# power-board.net
KiCad netlist of a schematic drawn in EAGLE
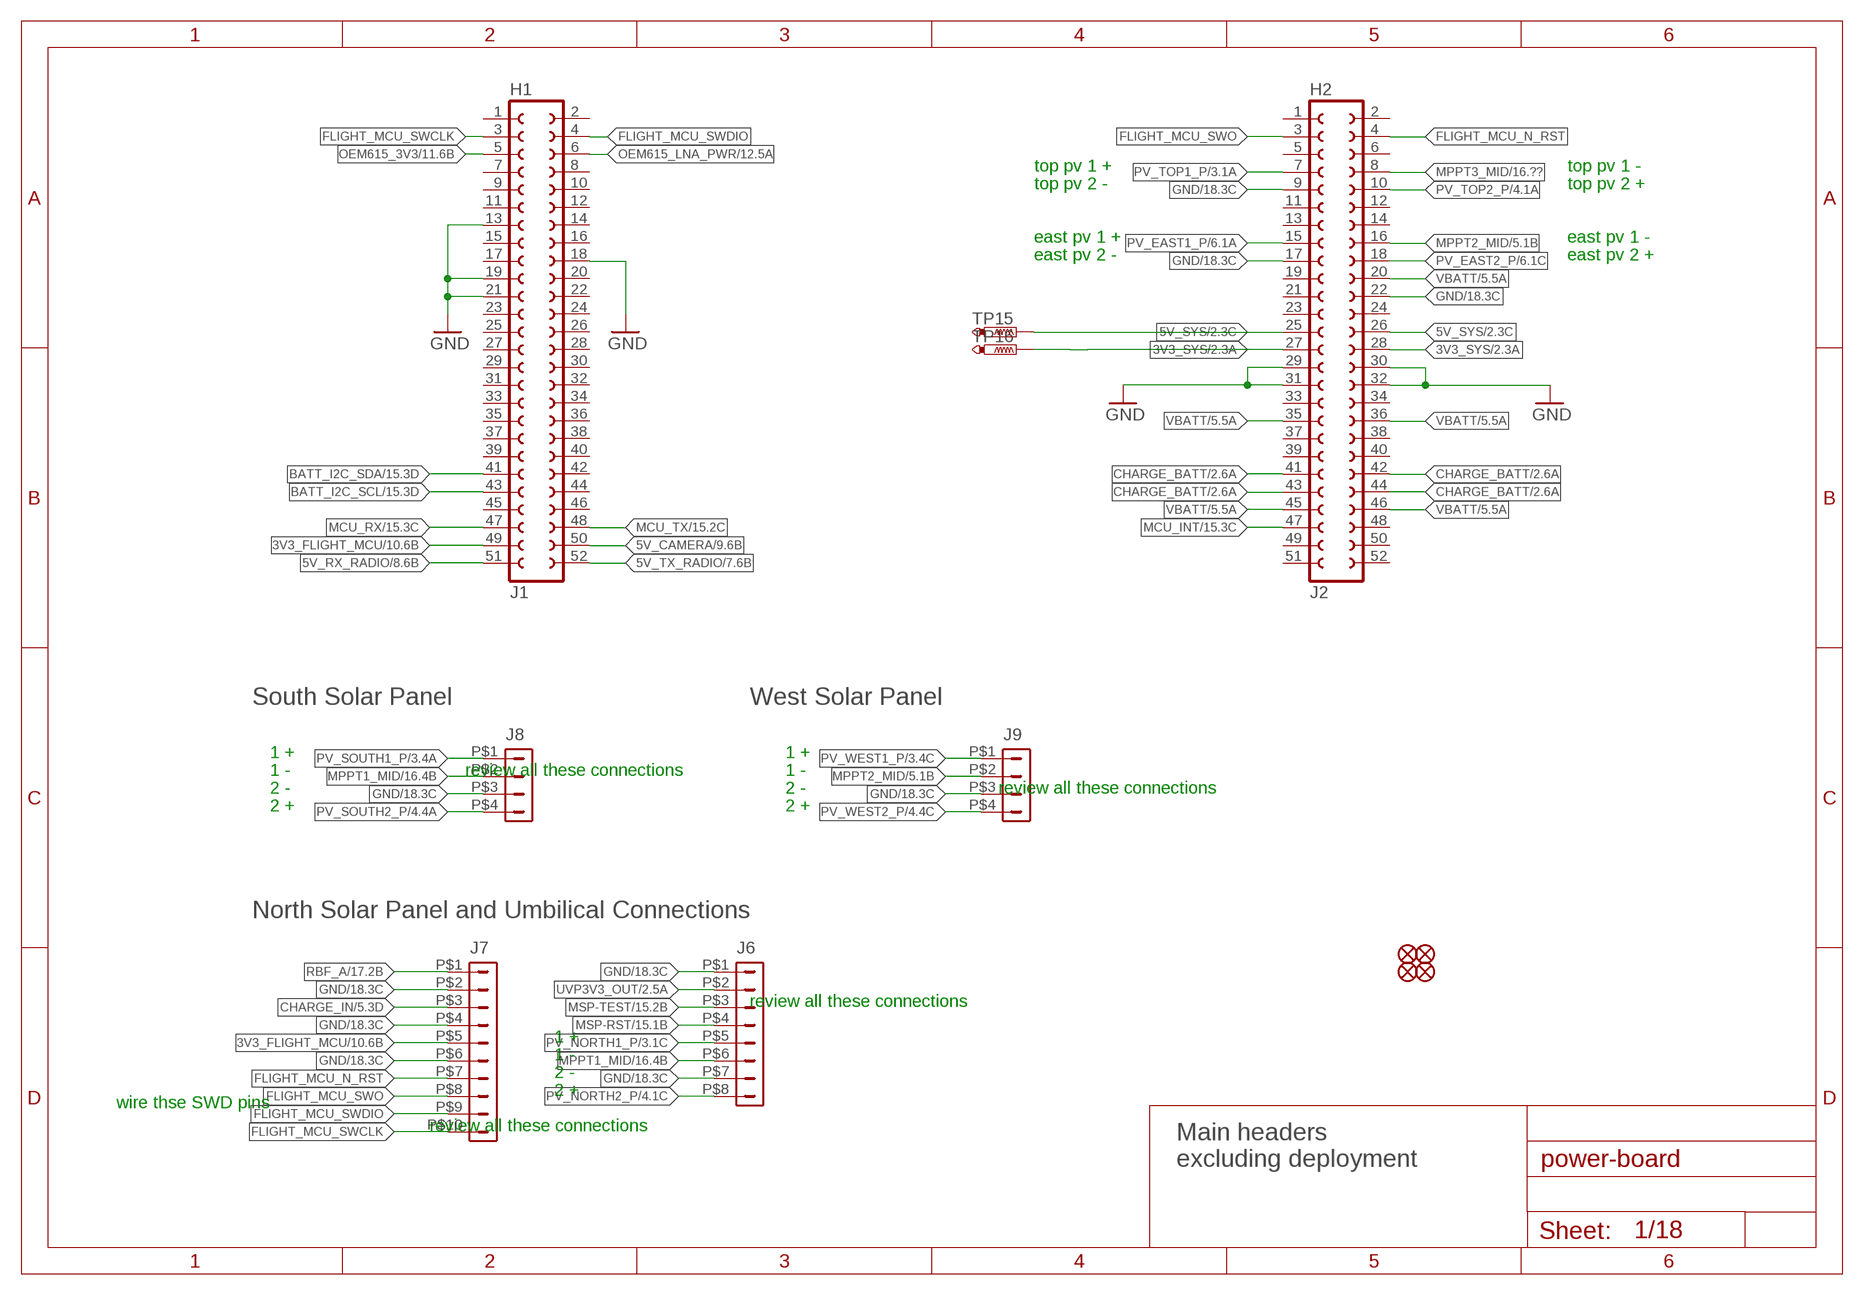
[diagram p0: schematic, sheet 1]
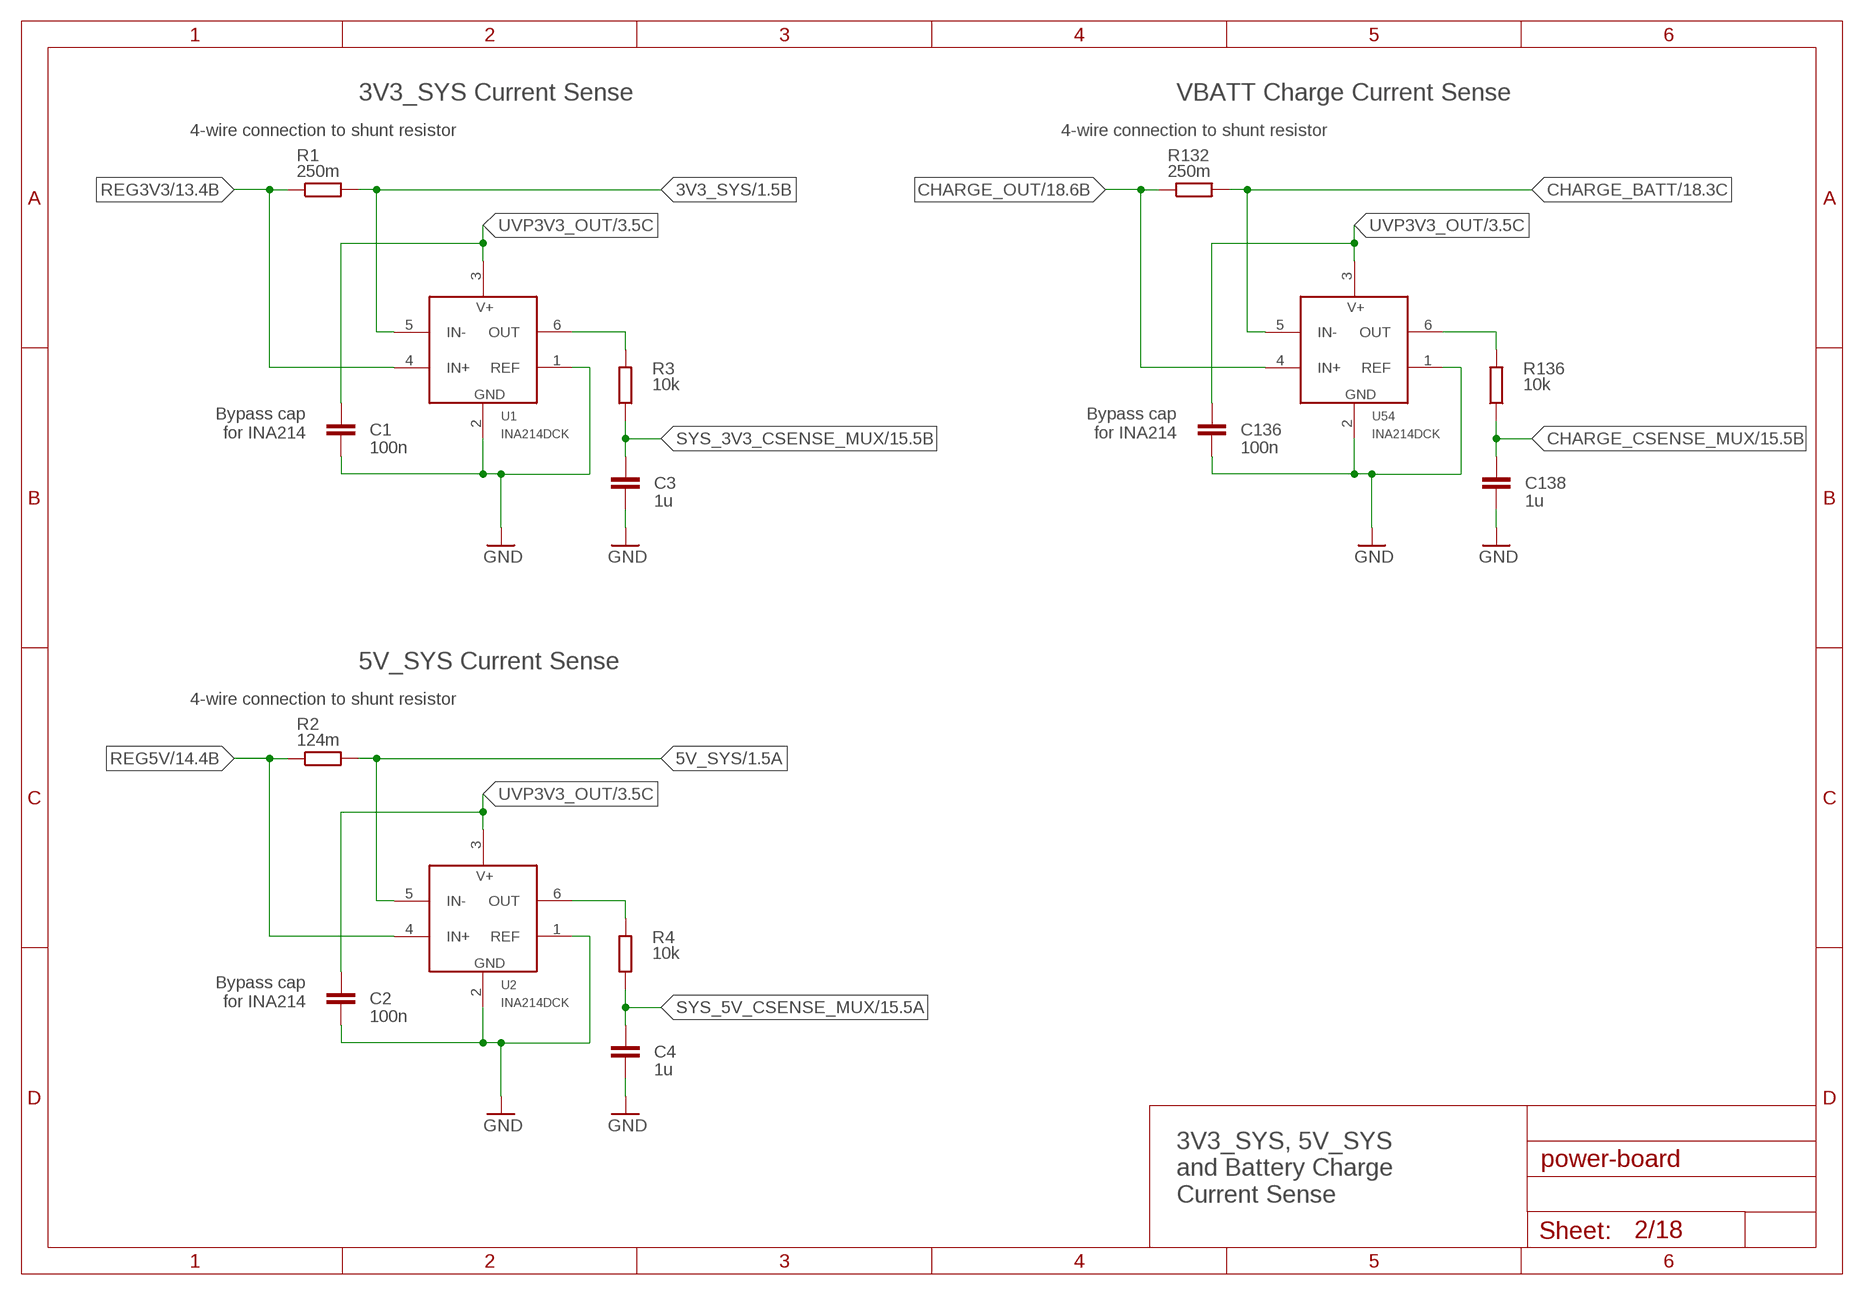
[diagram p1: schematic, sheet 2]
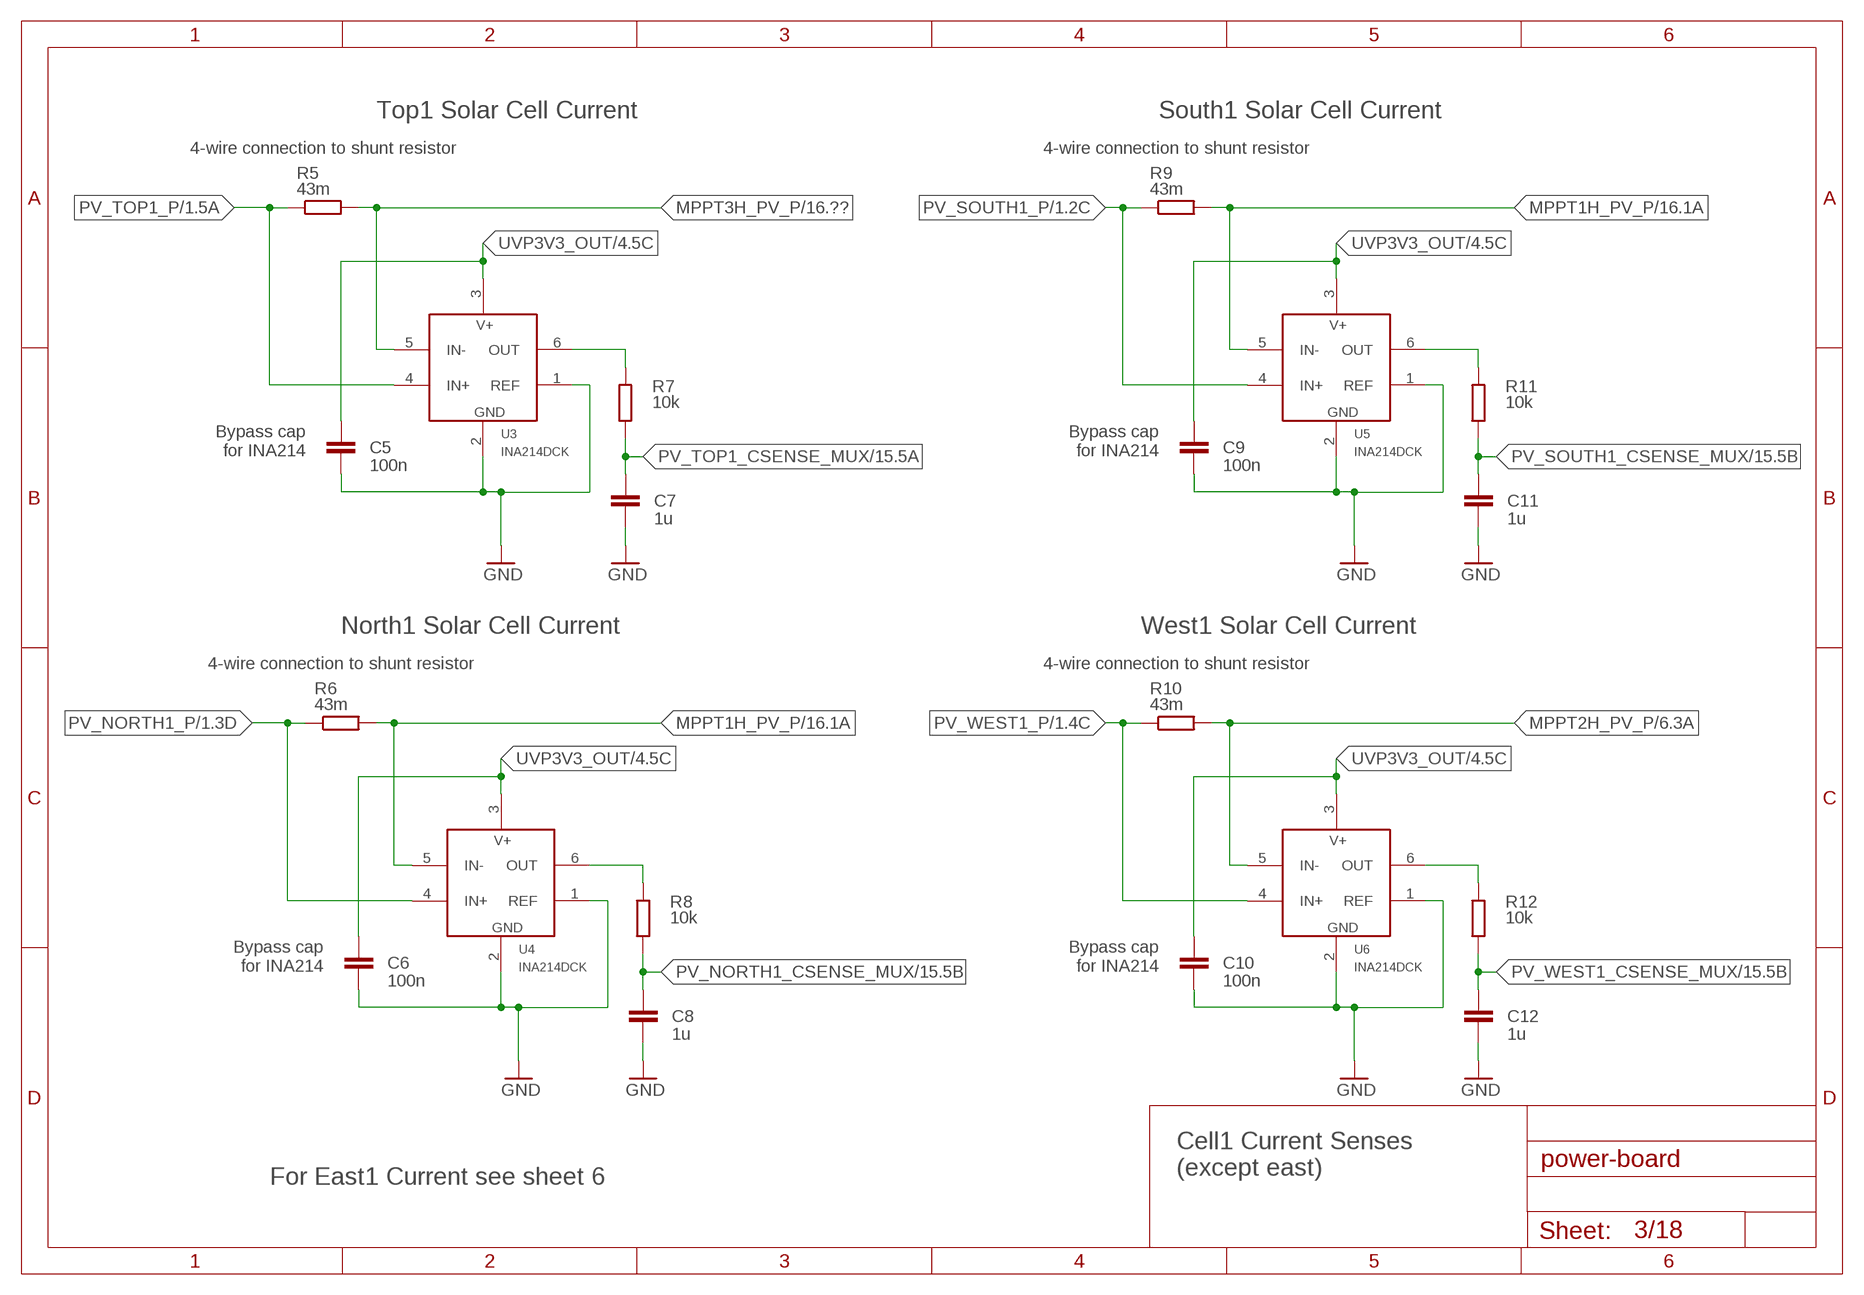
[diagram p2: schematic, sheet 3]
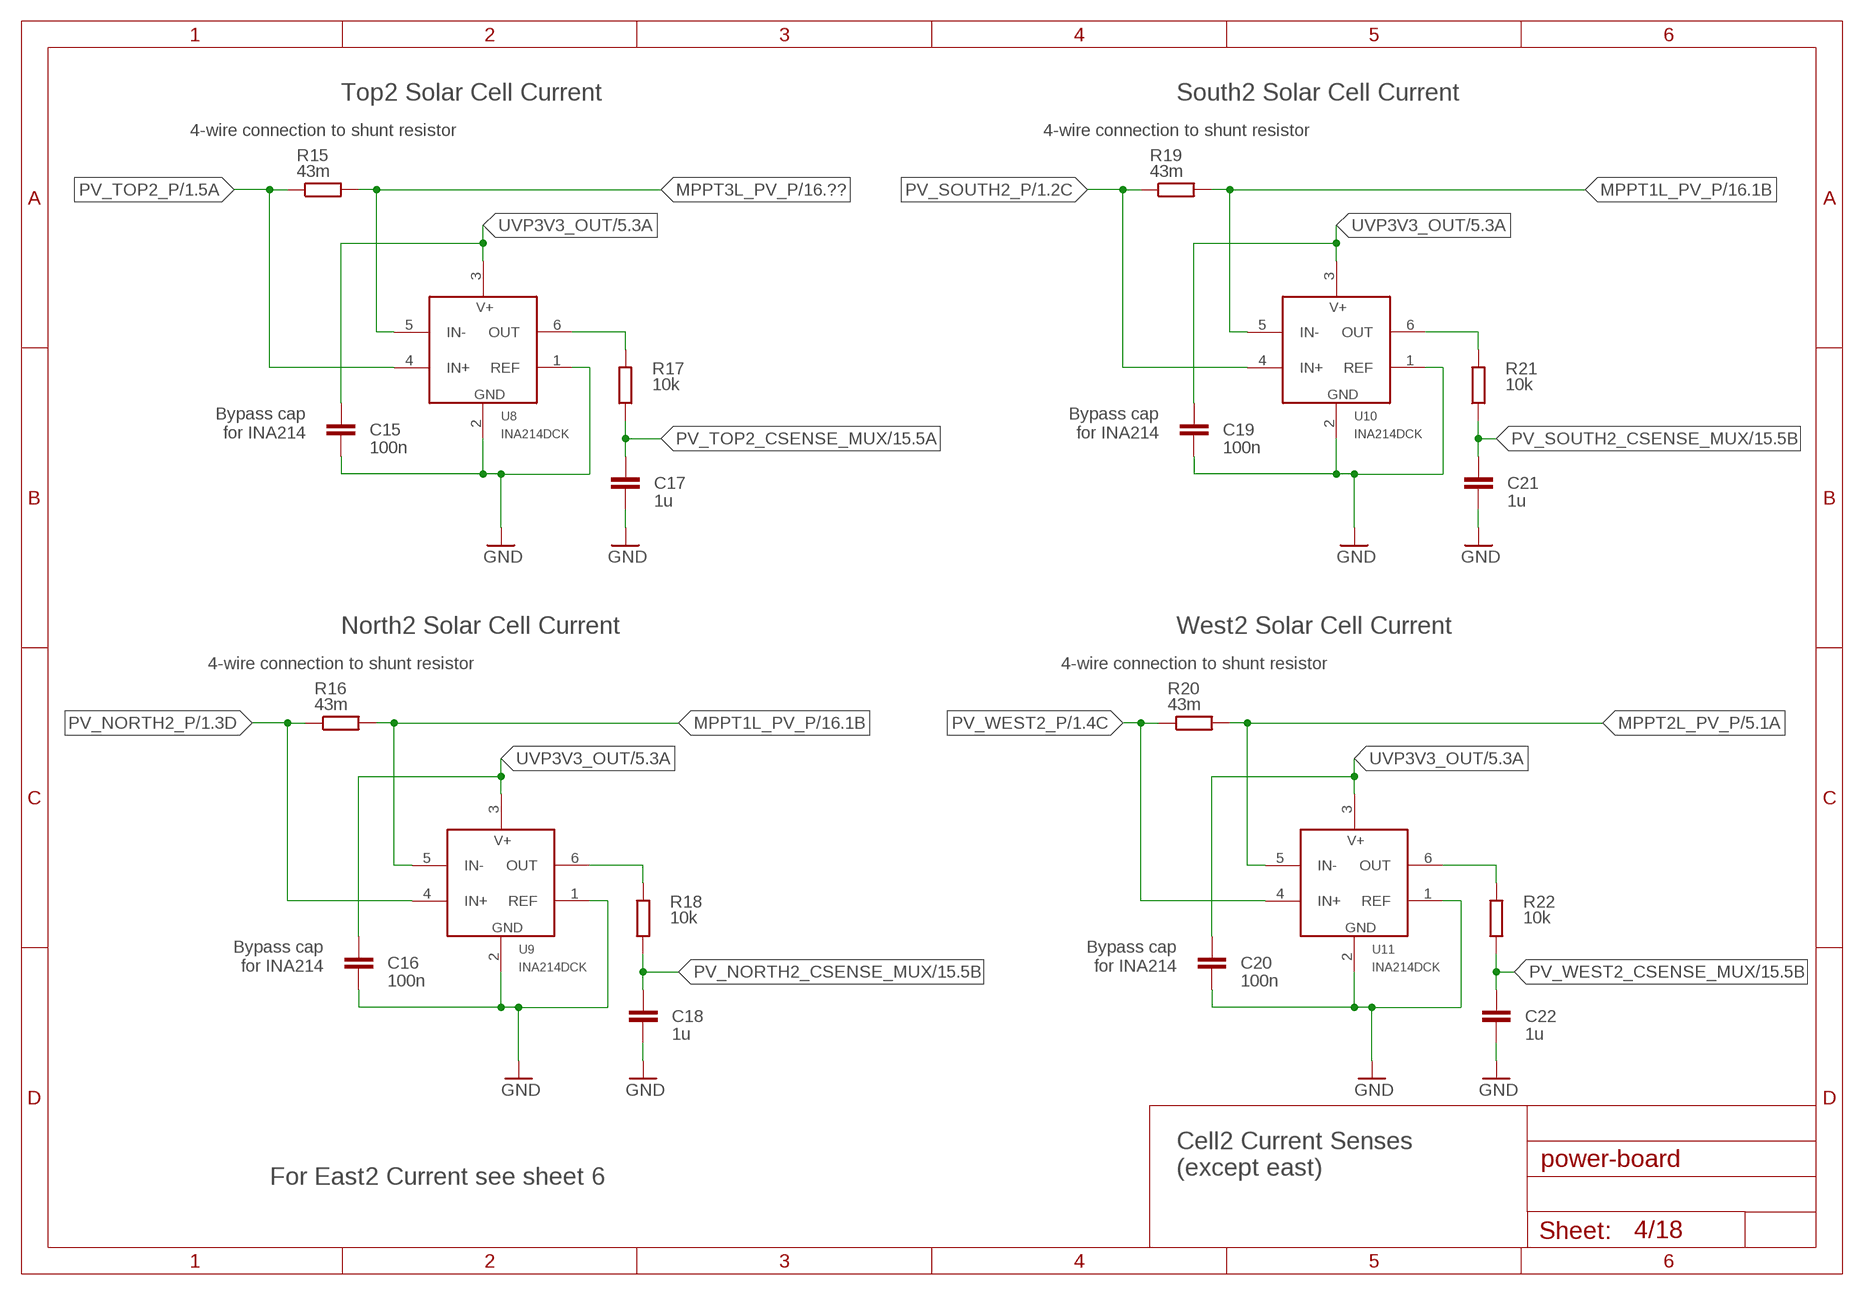
[diagram p3: schematic, sheet 4]
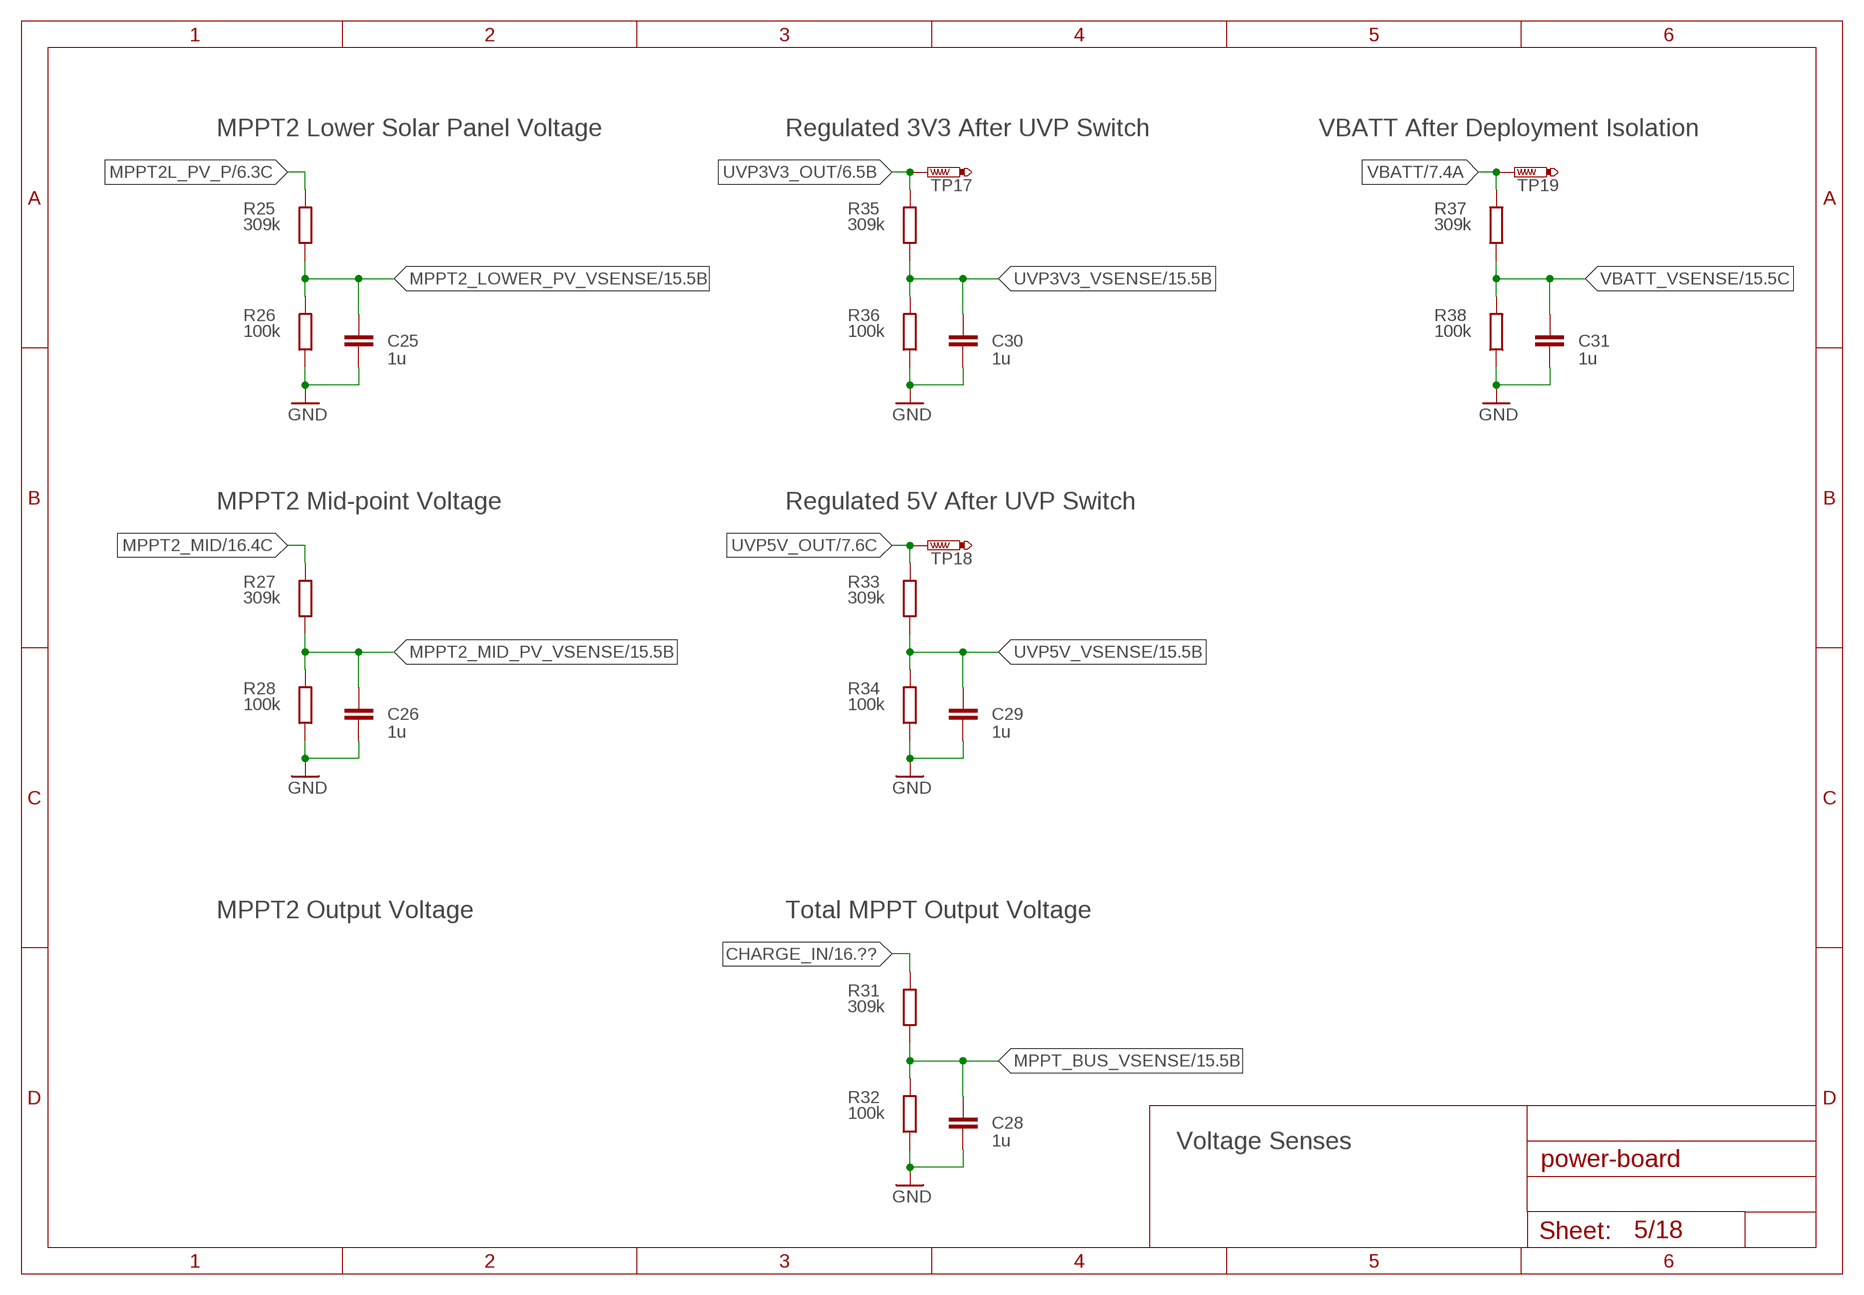
[diagram p4: schematic, sheet 5]
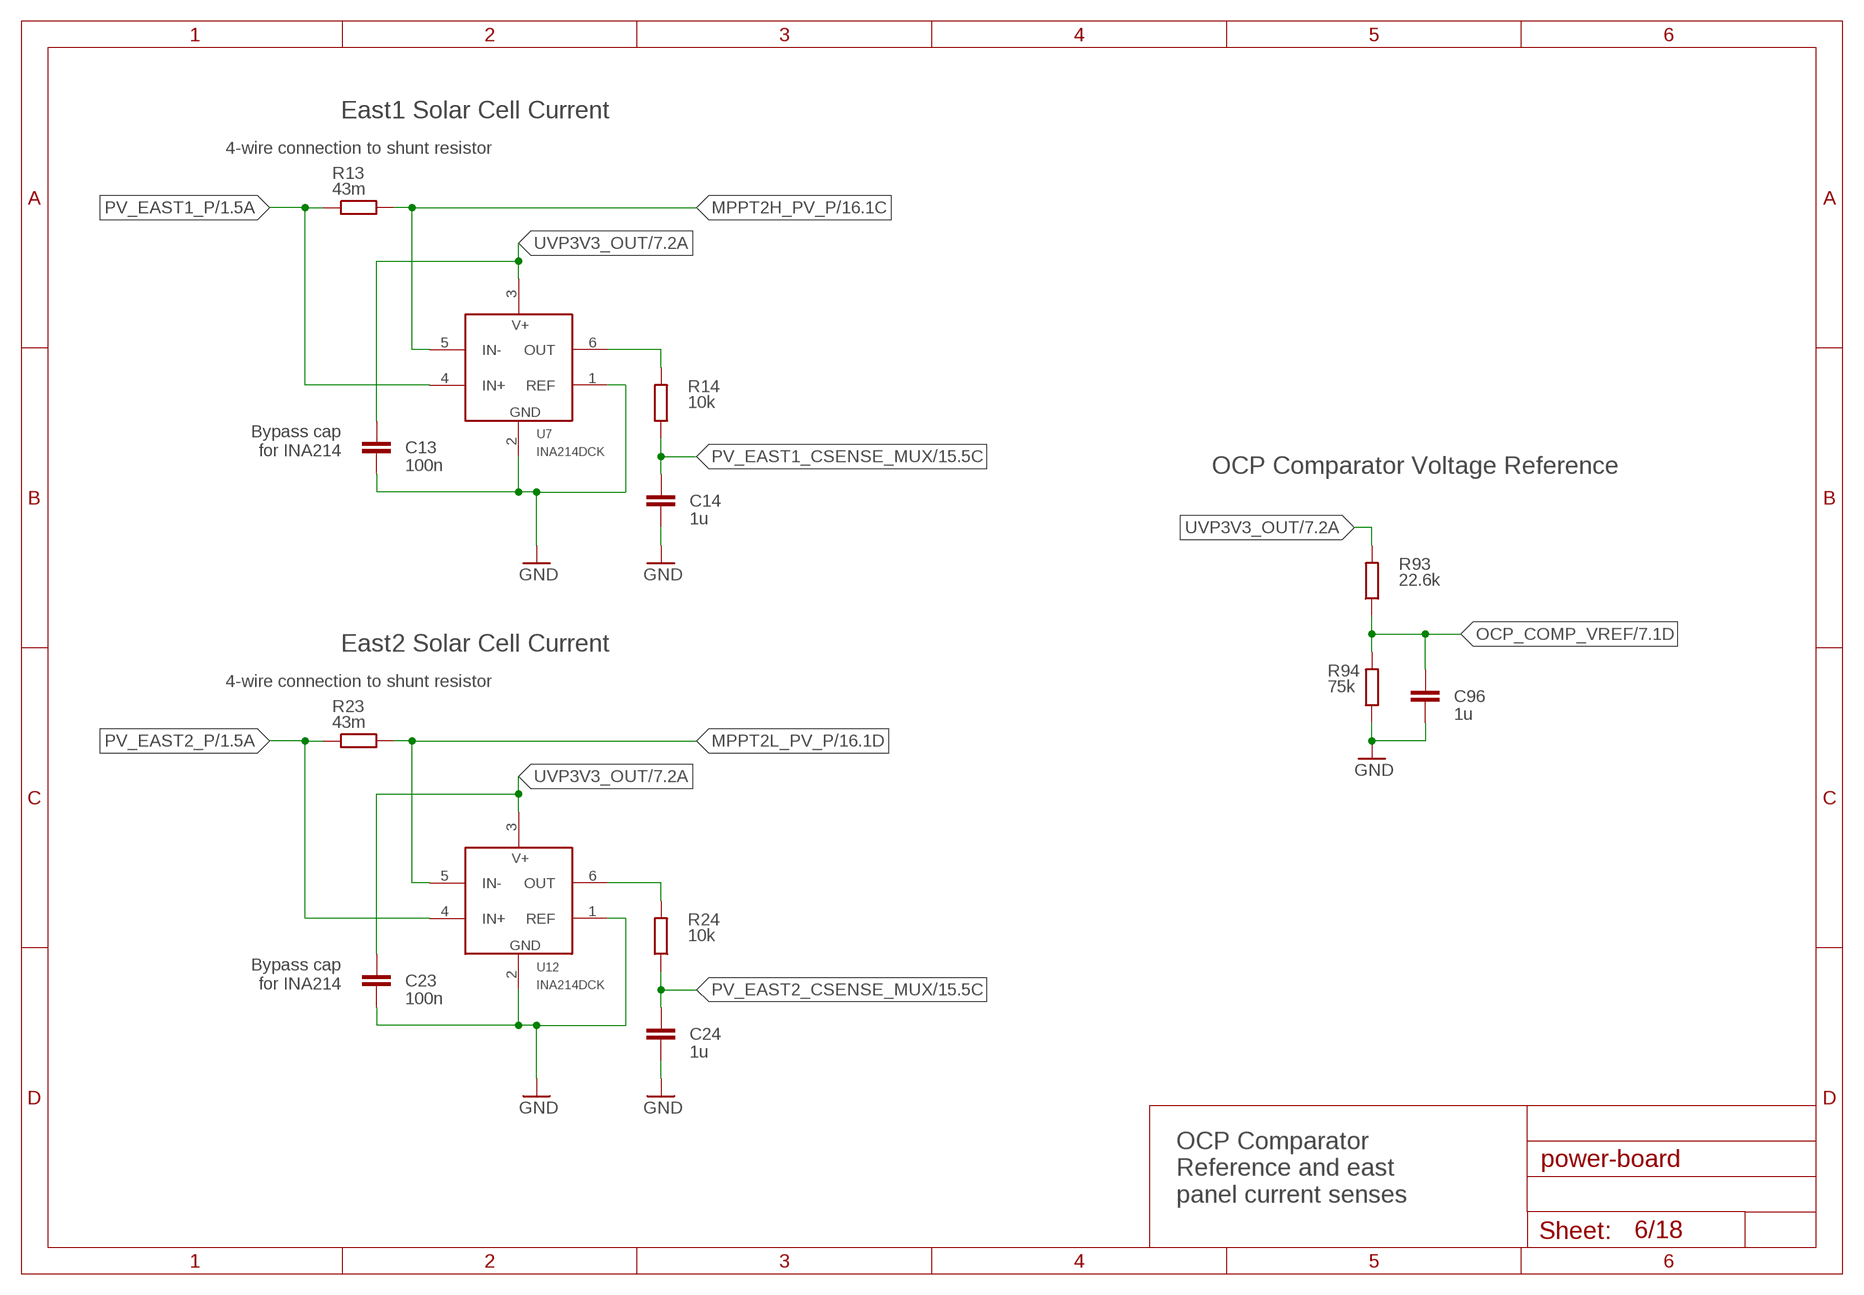
[diagram p5: schematic, sheet 6]
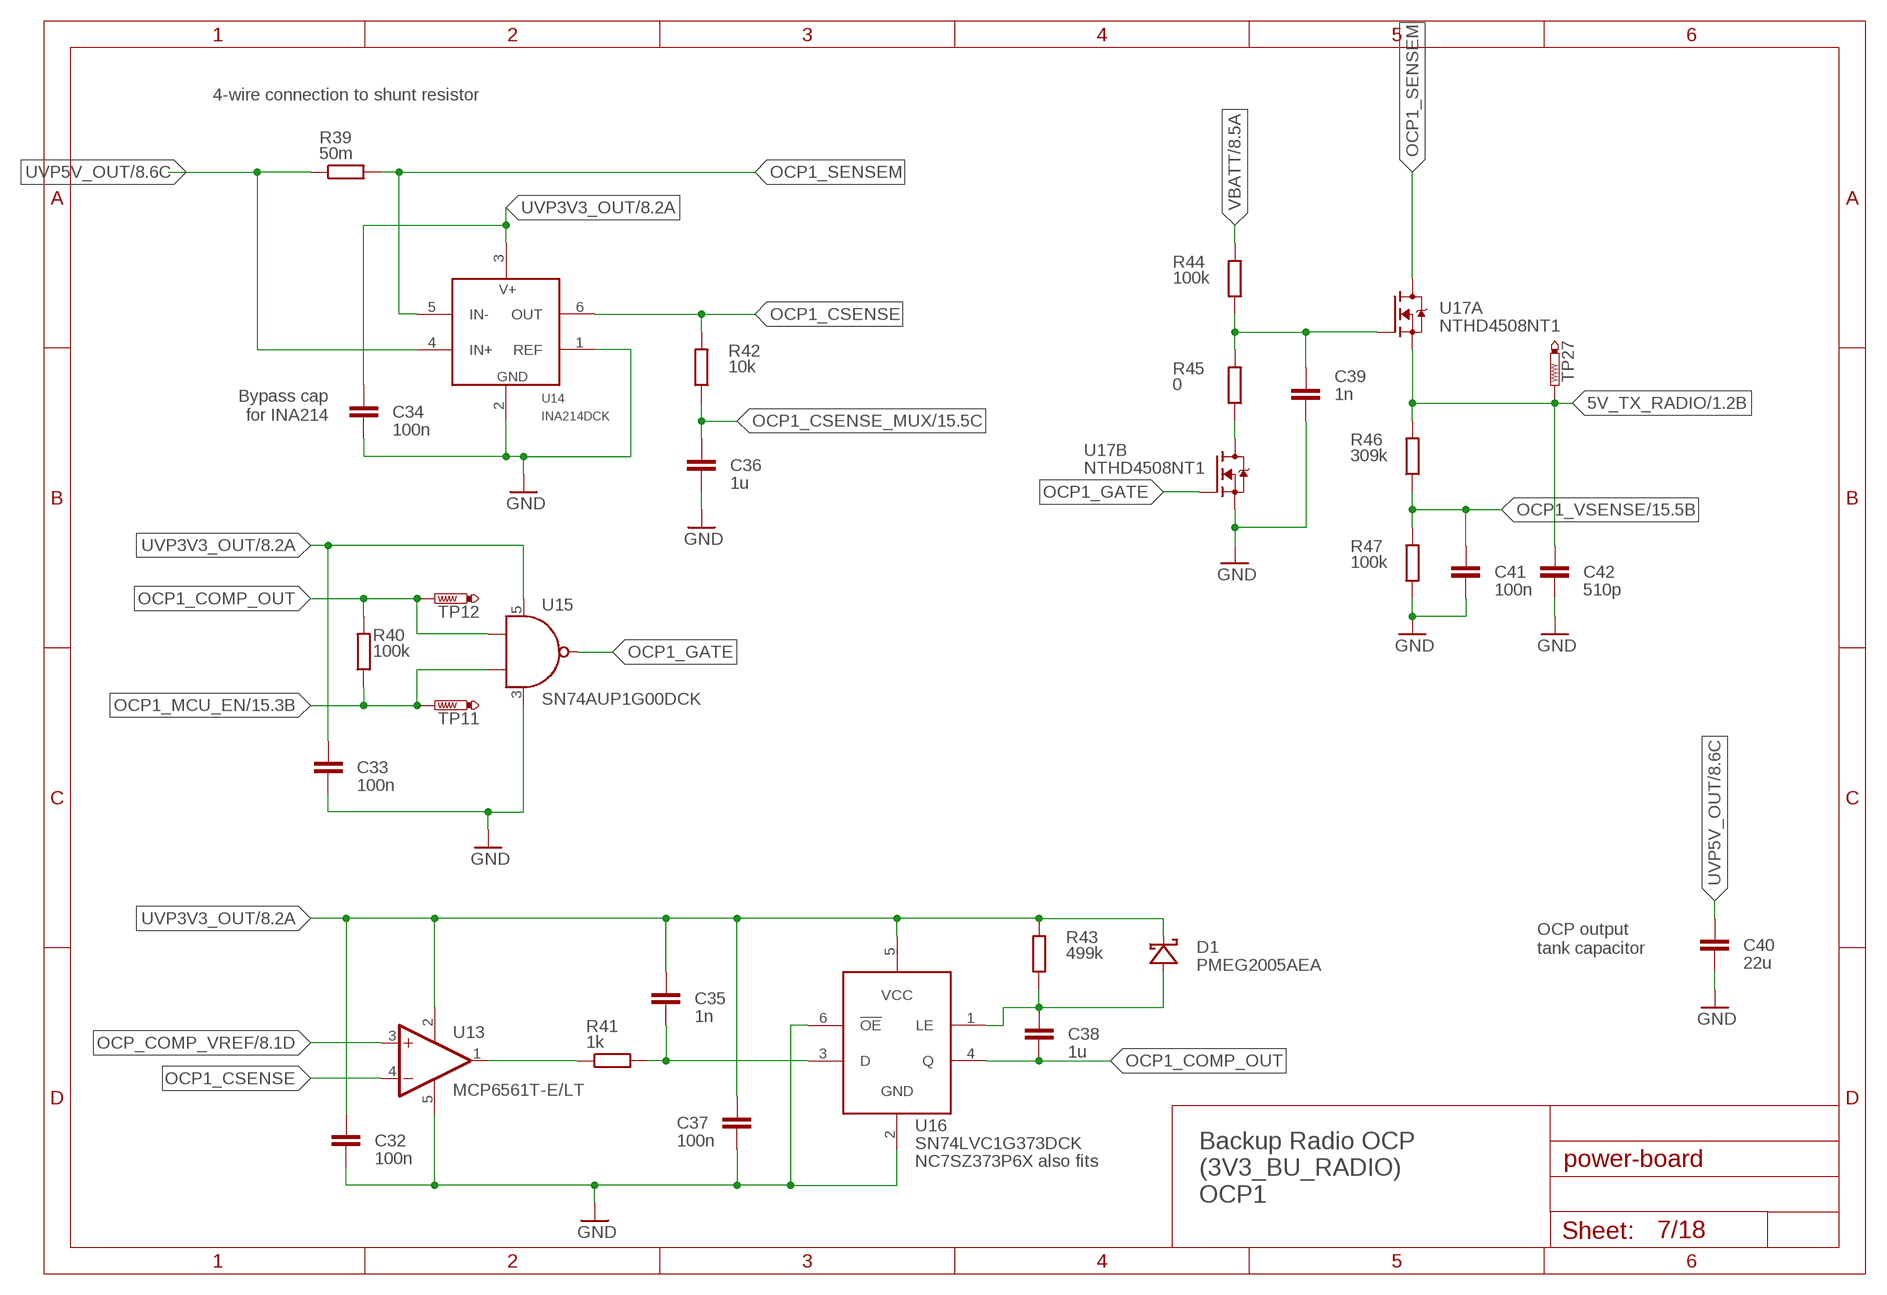
[diagram p6: schematic, sheet 7]
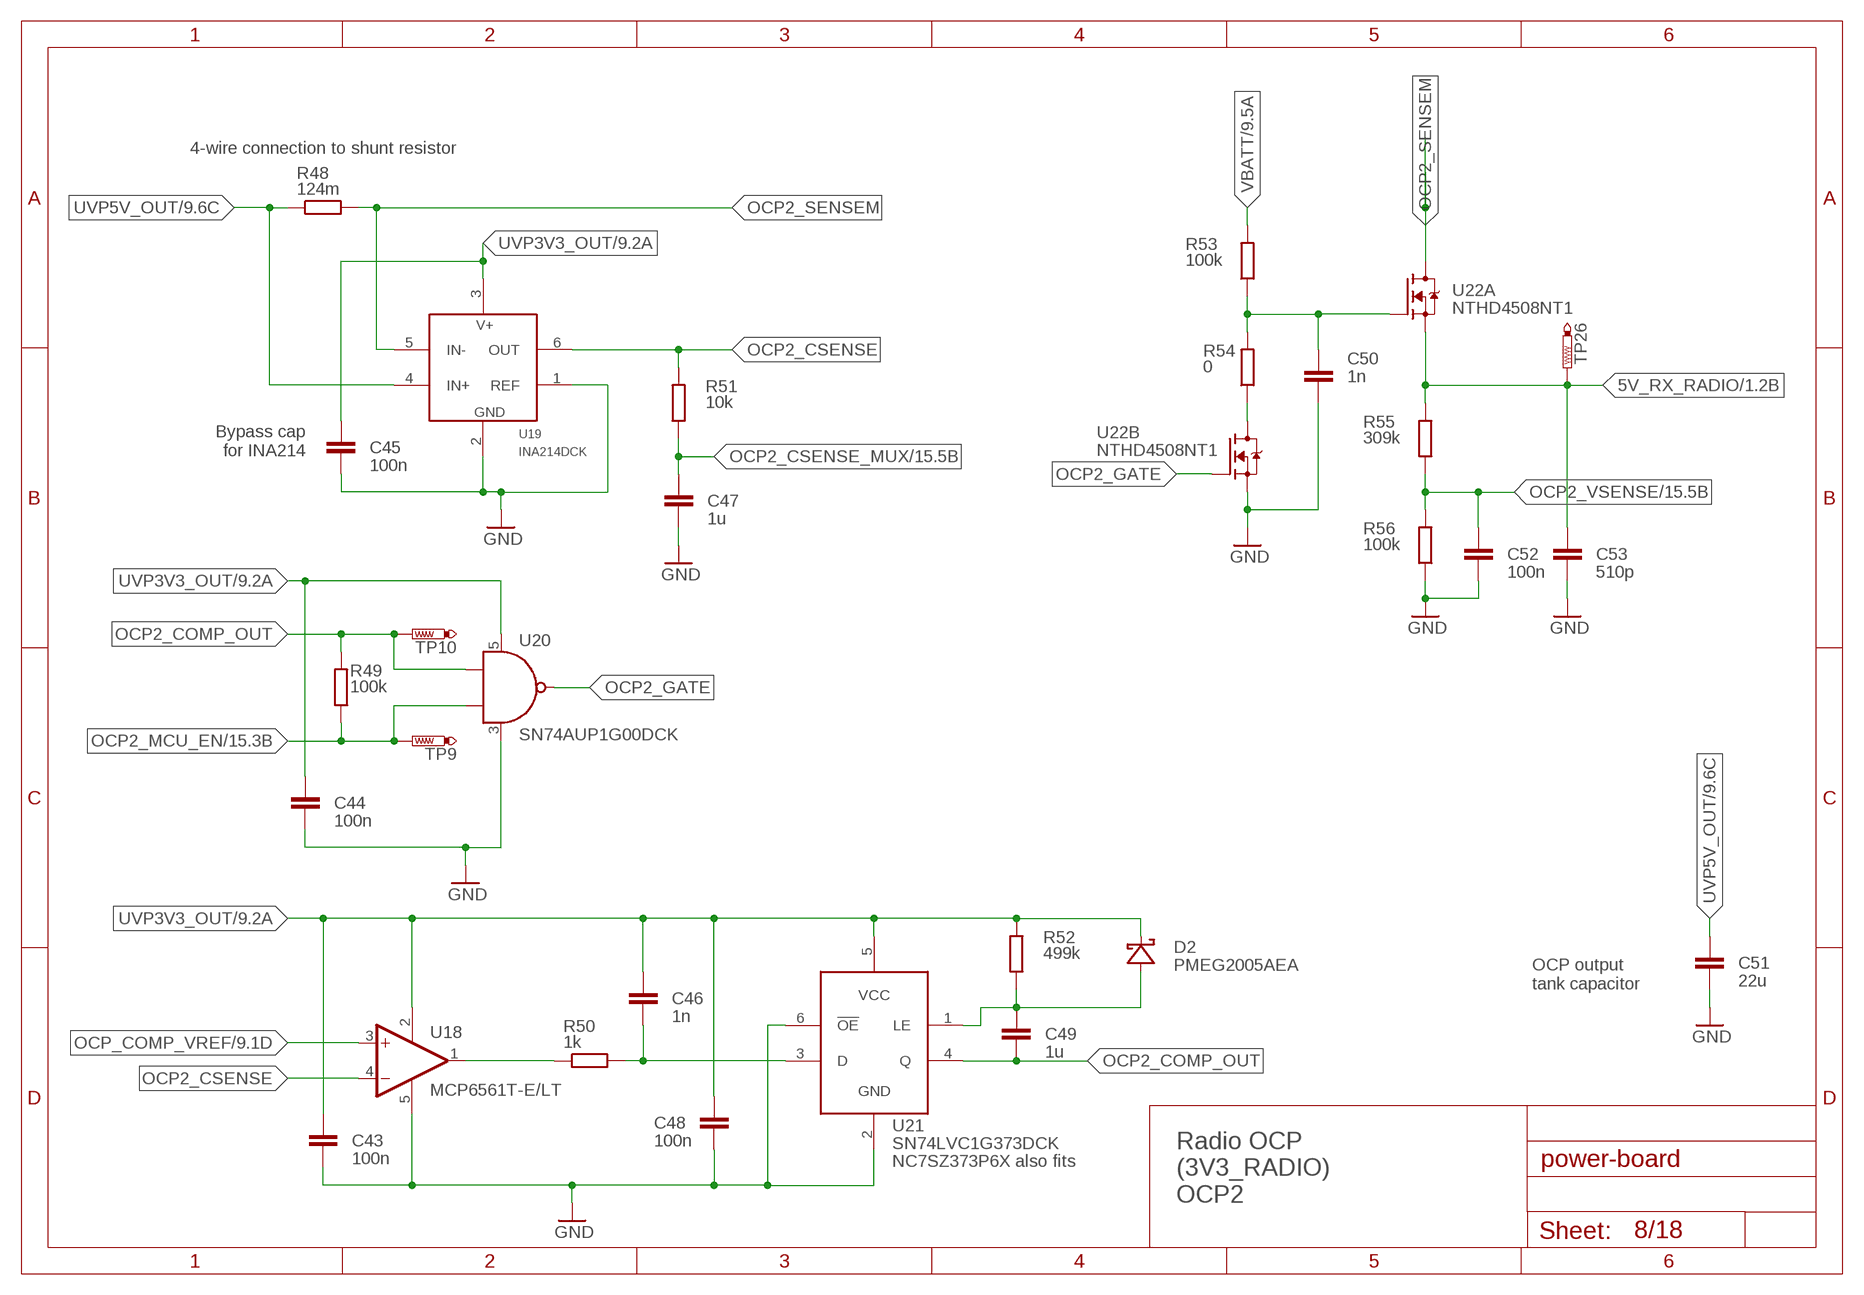
[diagram p7: schematic, sheet 8]
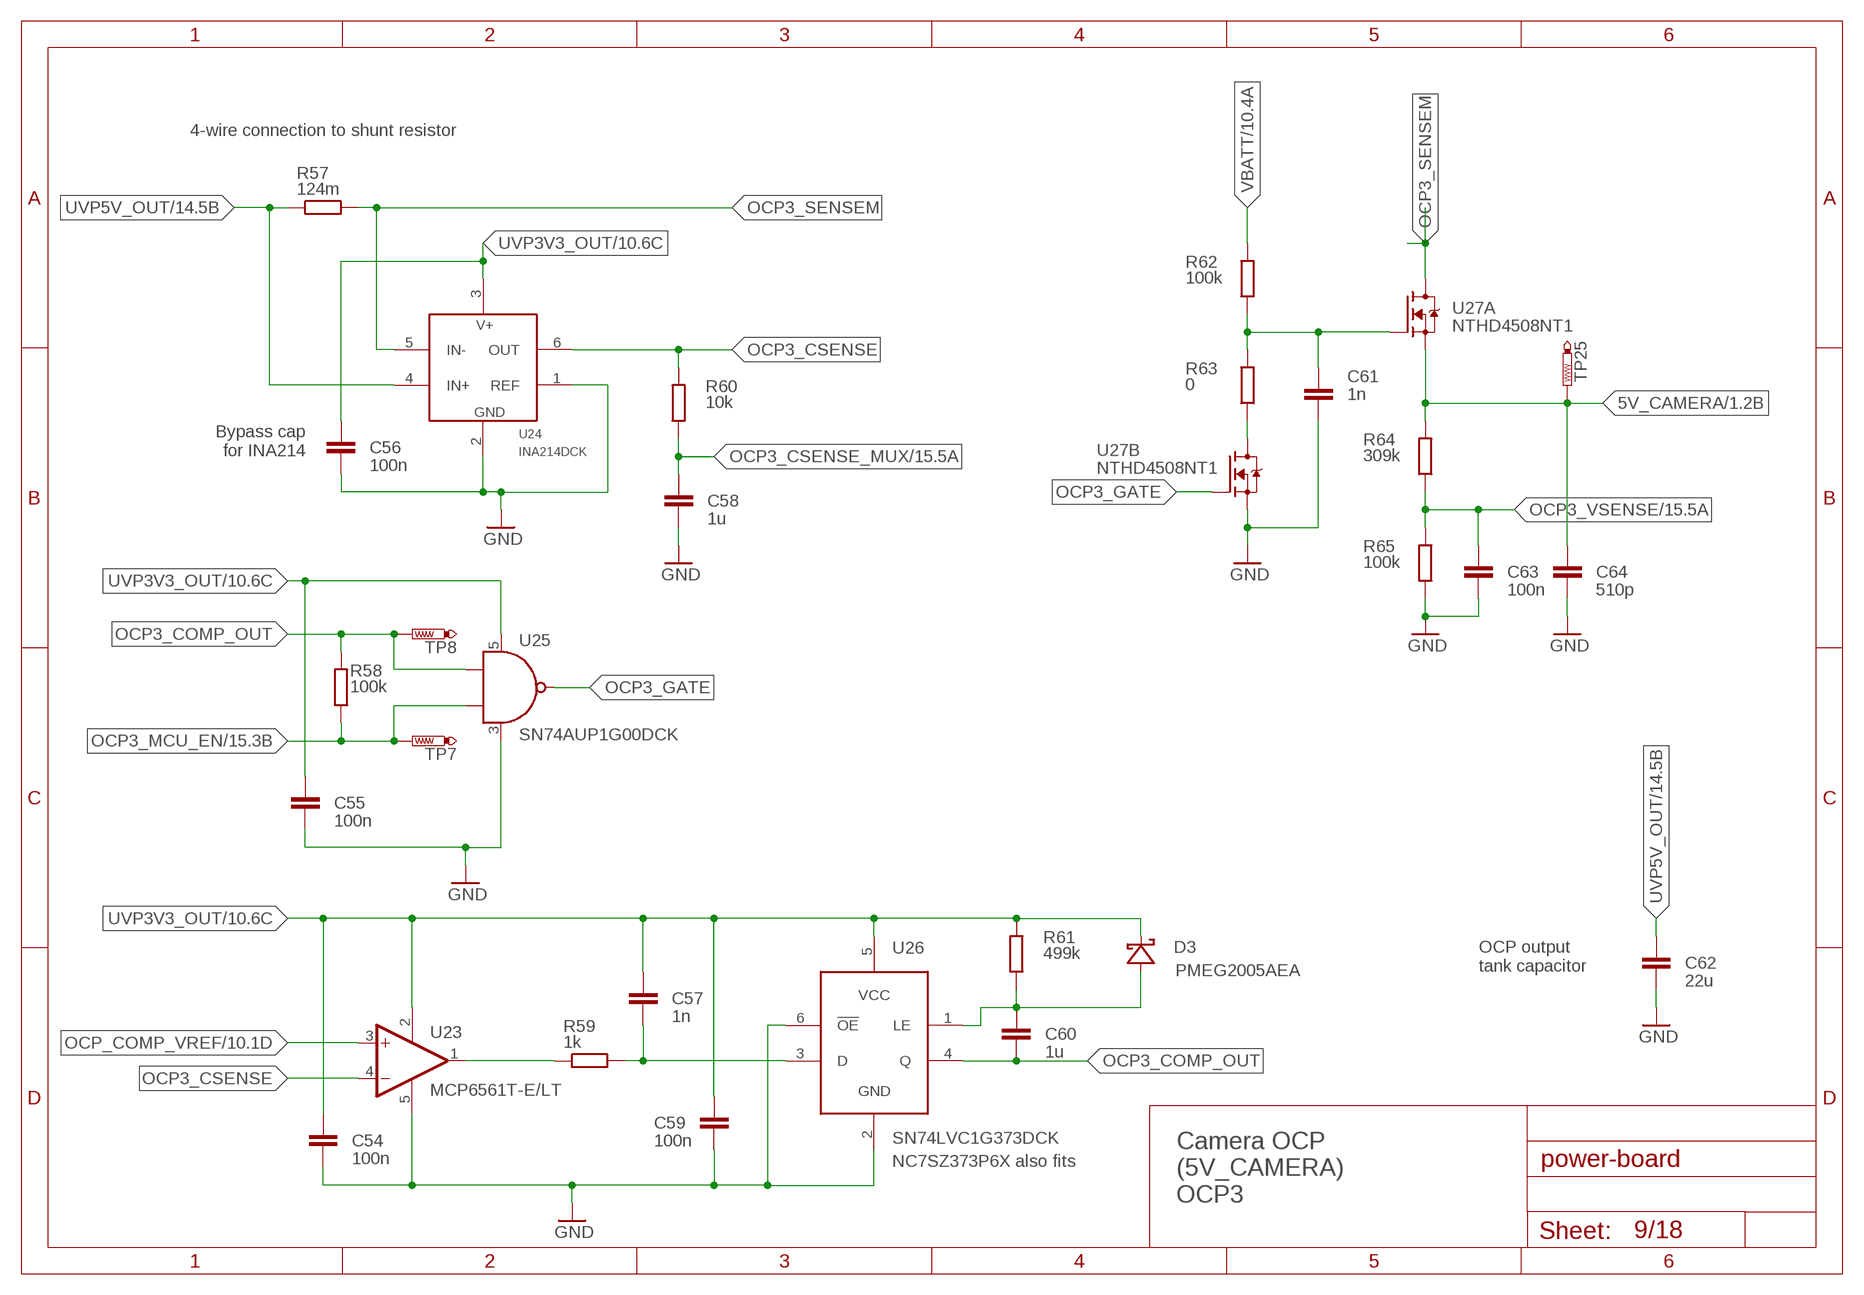
[diagram p8: schematic, sheet 9]
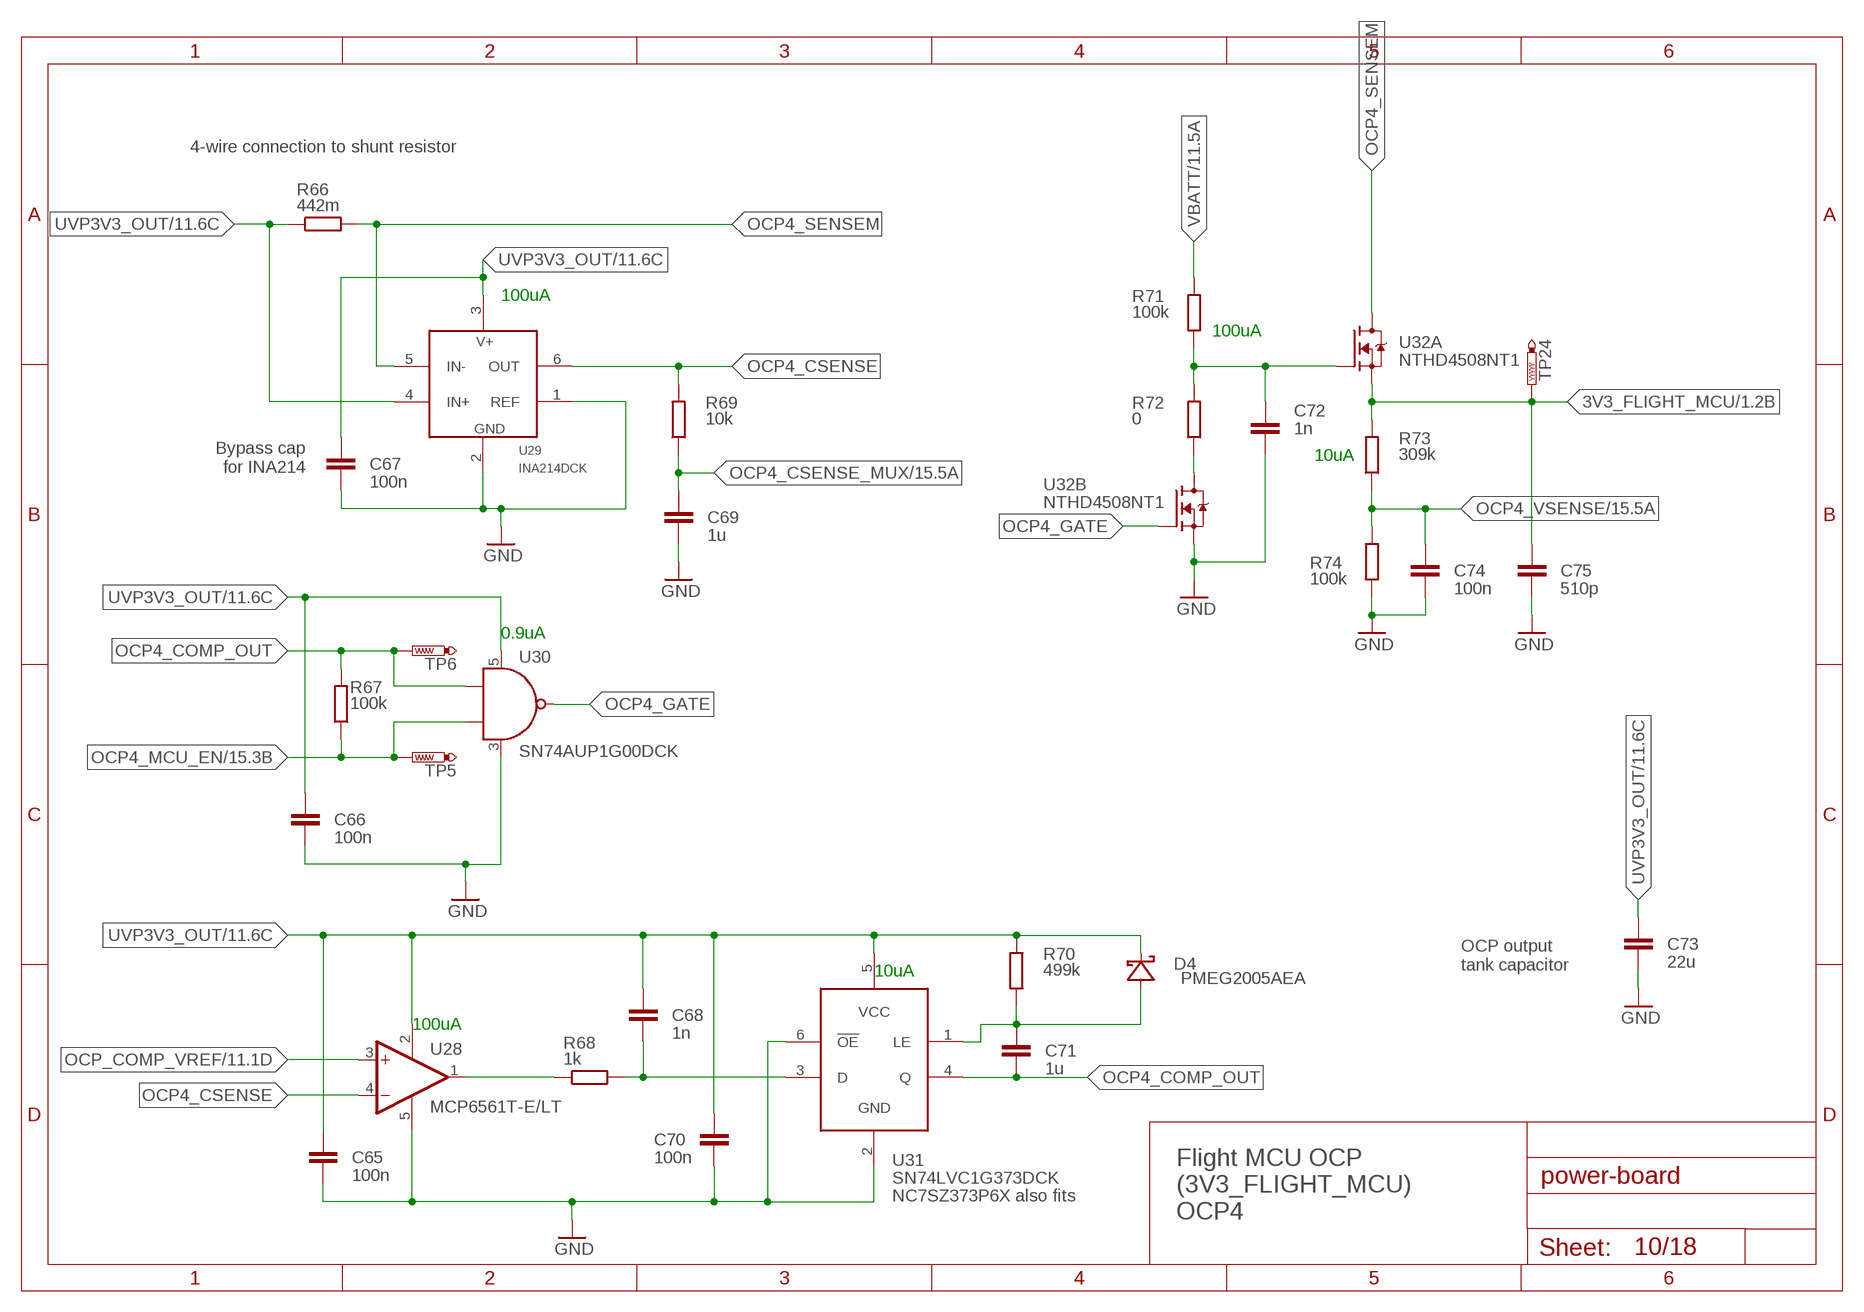
[diagram p9: schematic, sheet 10]
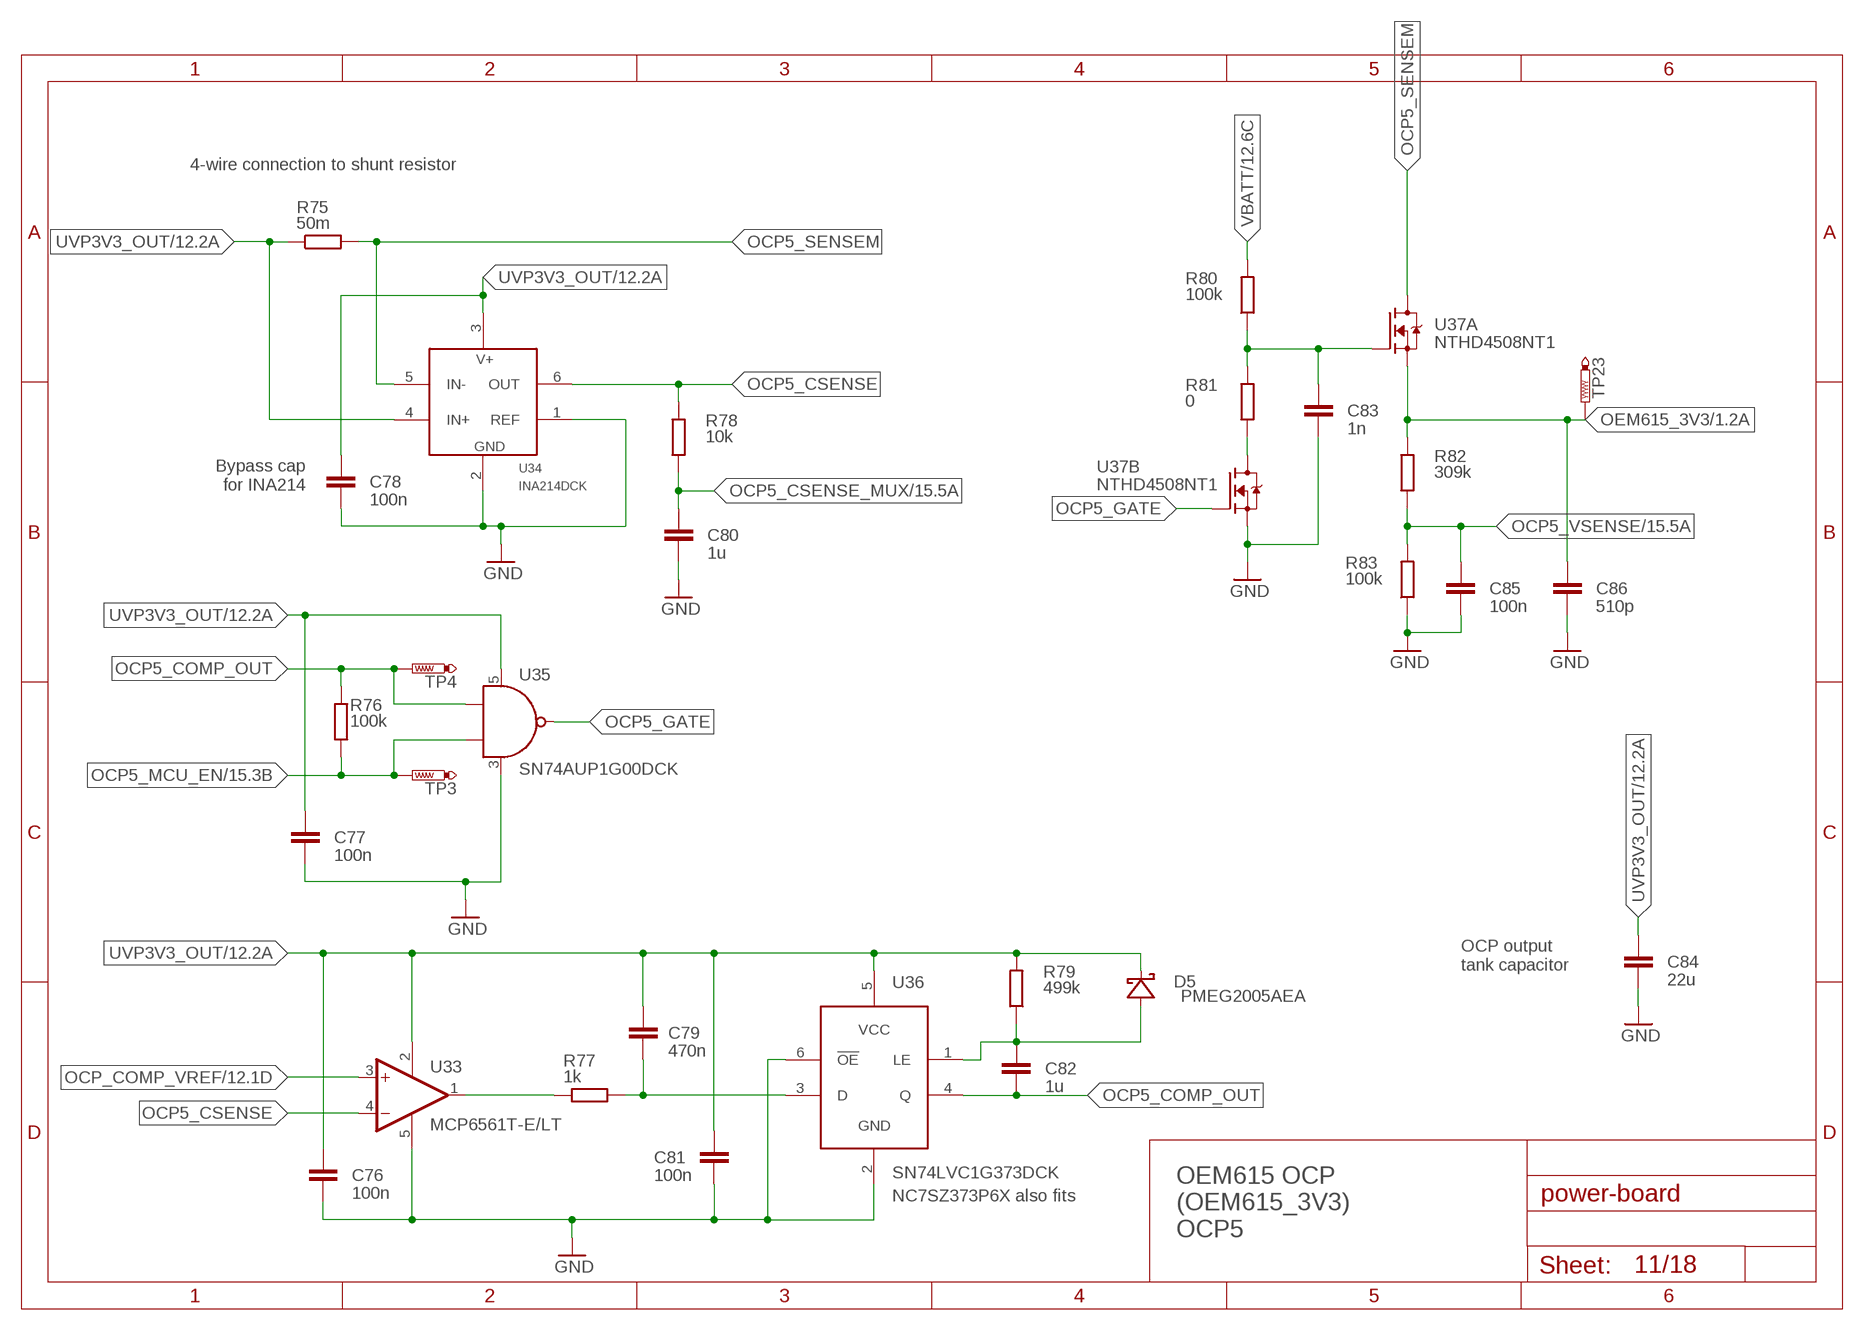
[diagram p10: schematic, sheet 11]
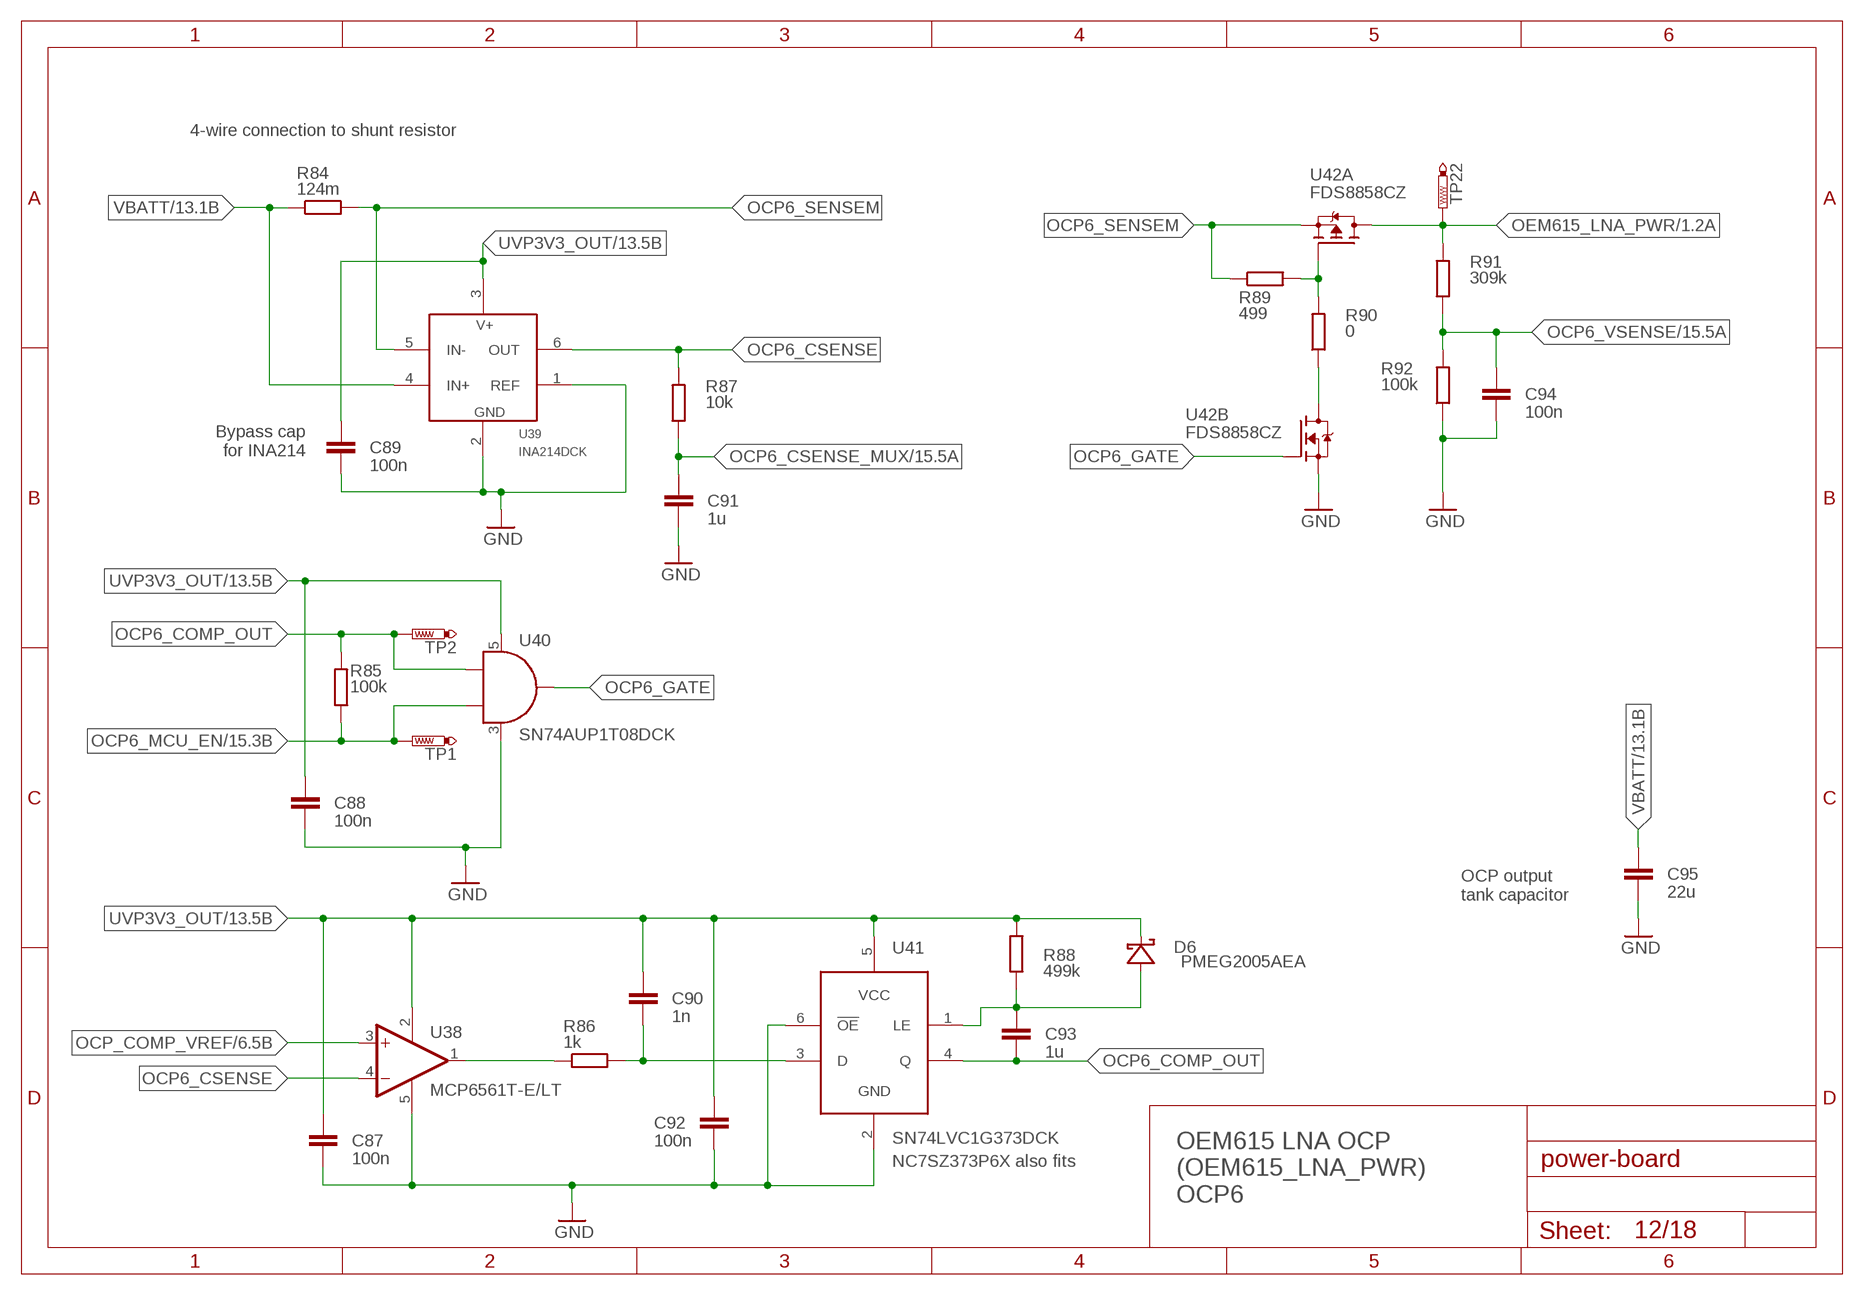
[diagram p11: schematic, sheet 12]
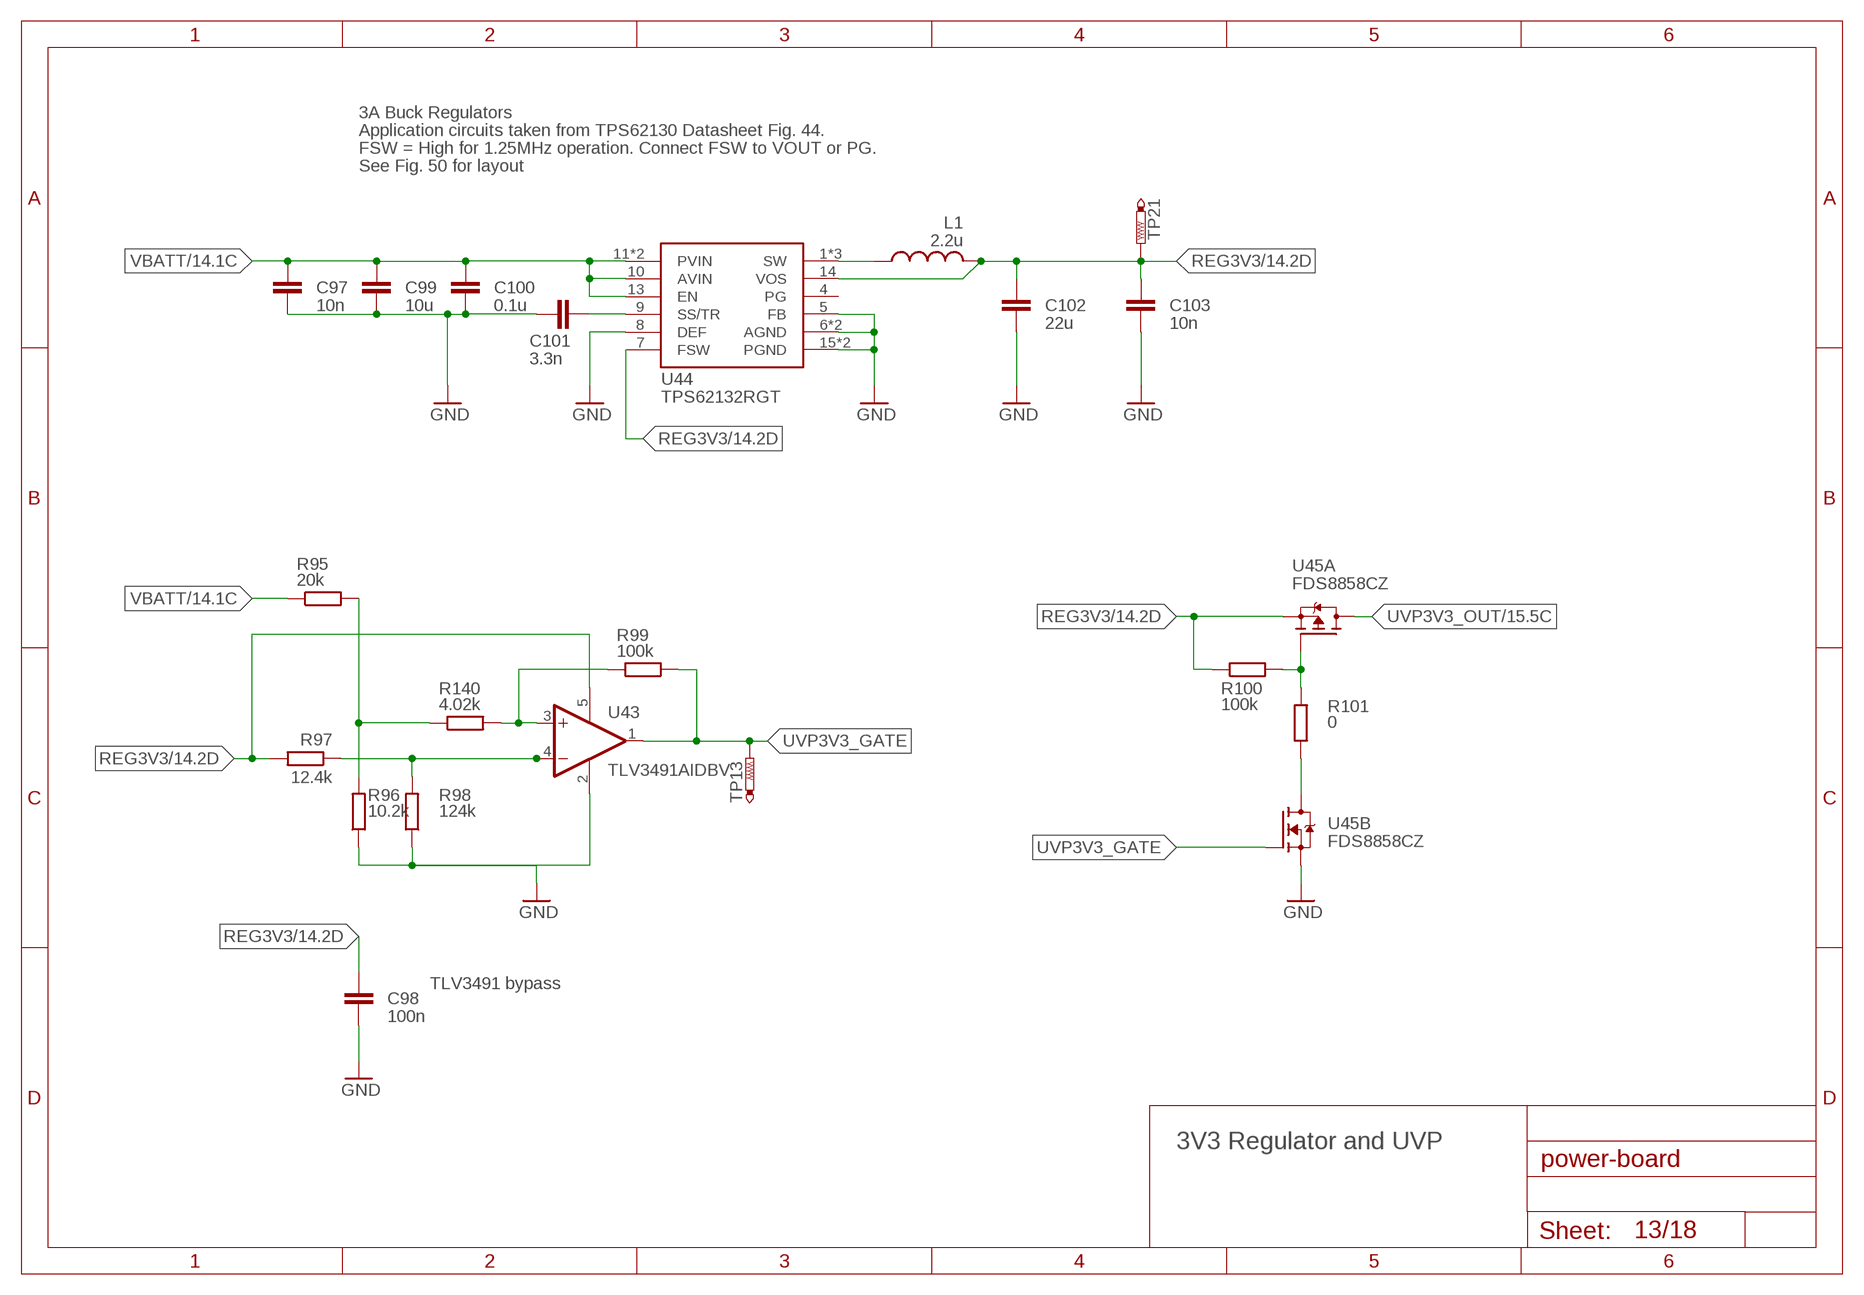
[diagram p12: schematic, sheet 13]
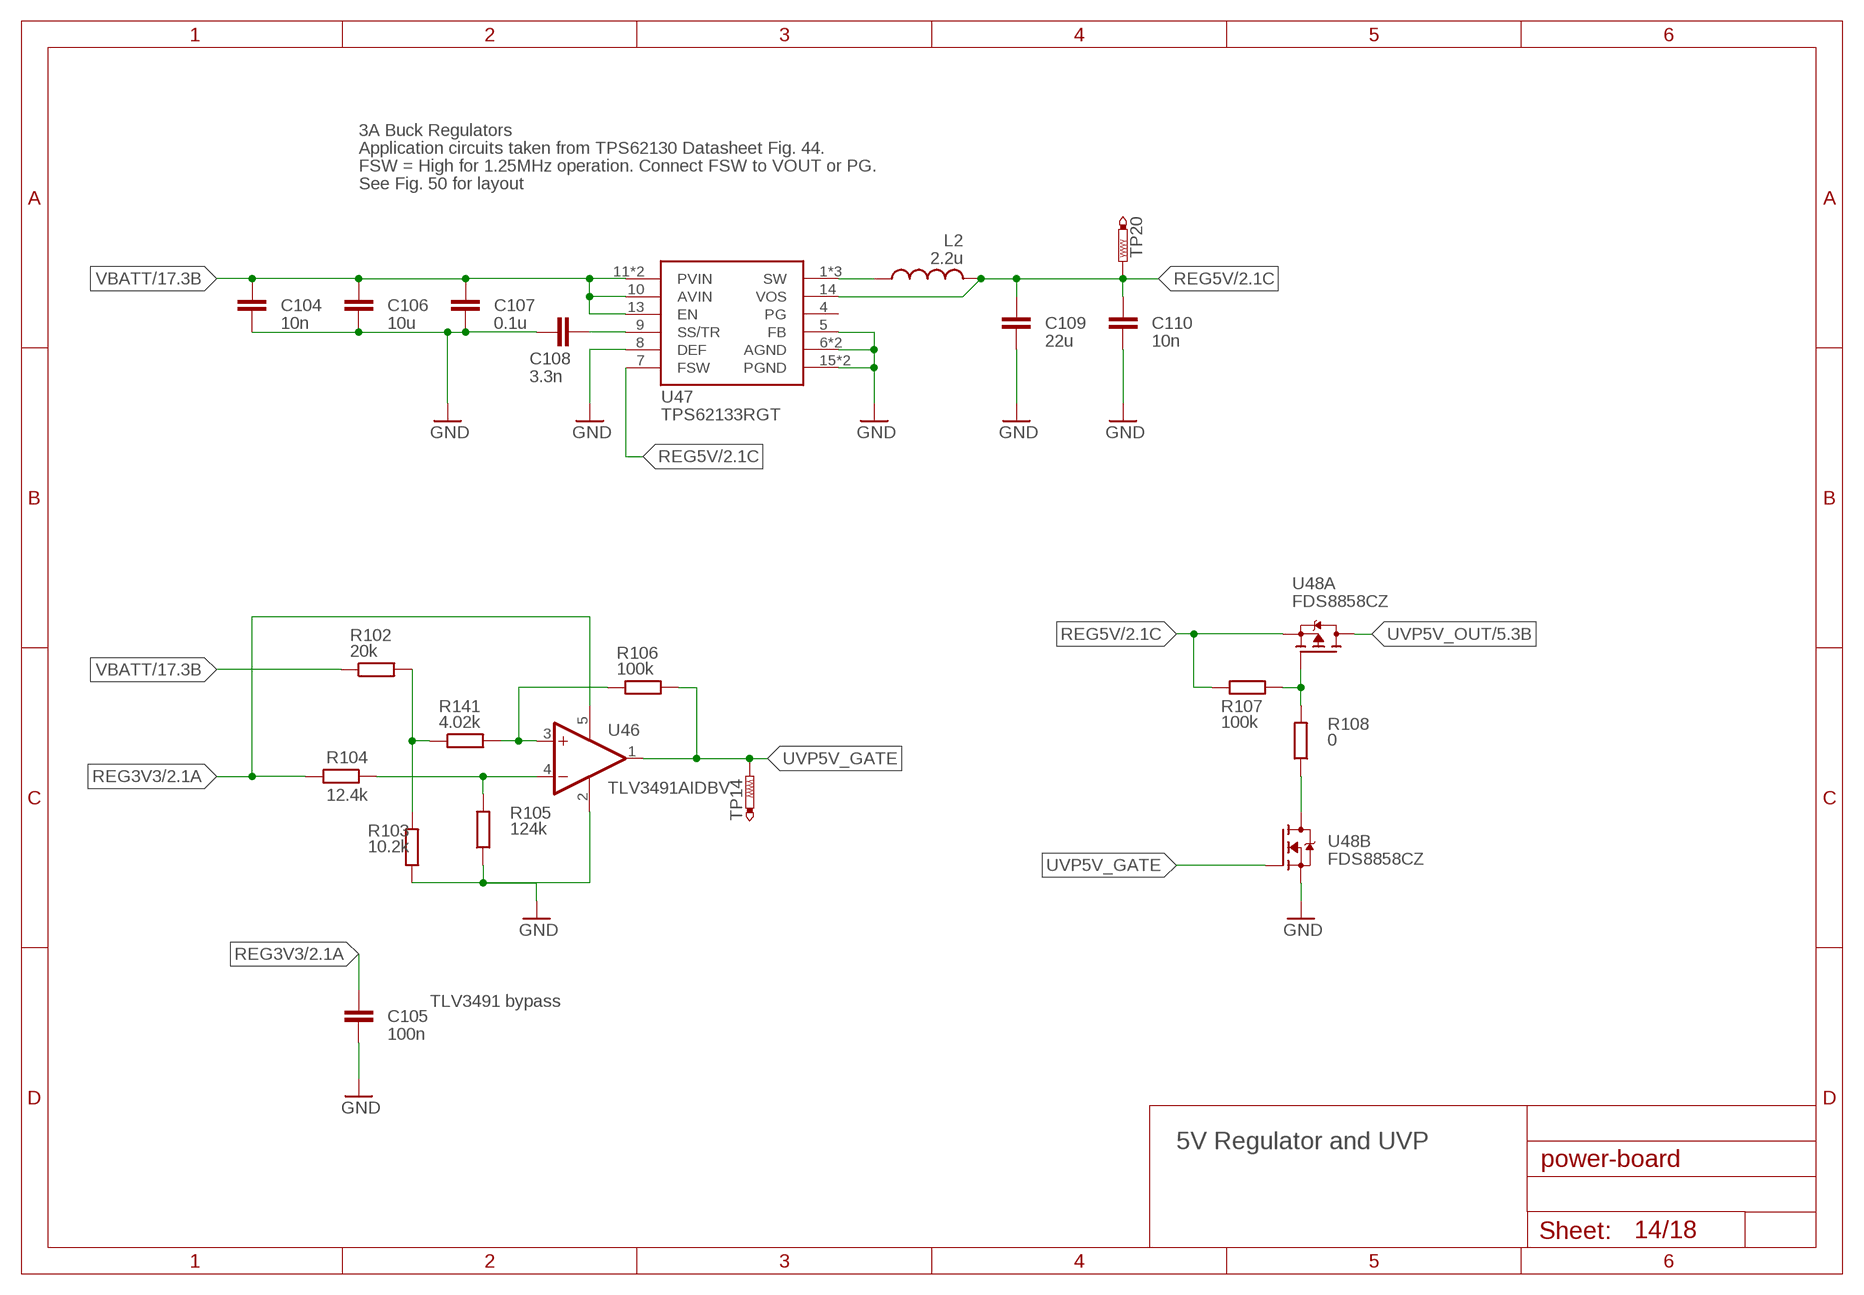
[diagram p13: schematic, sheet 14]
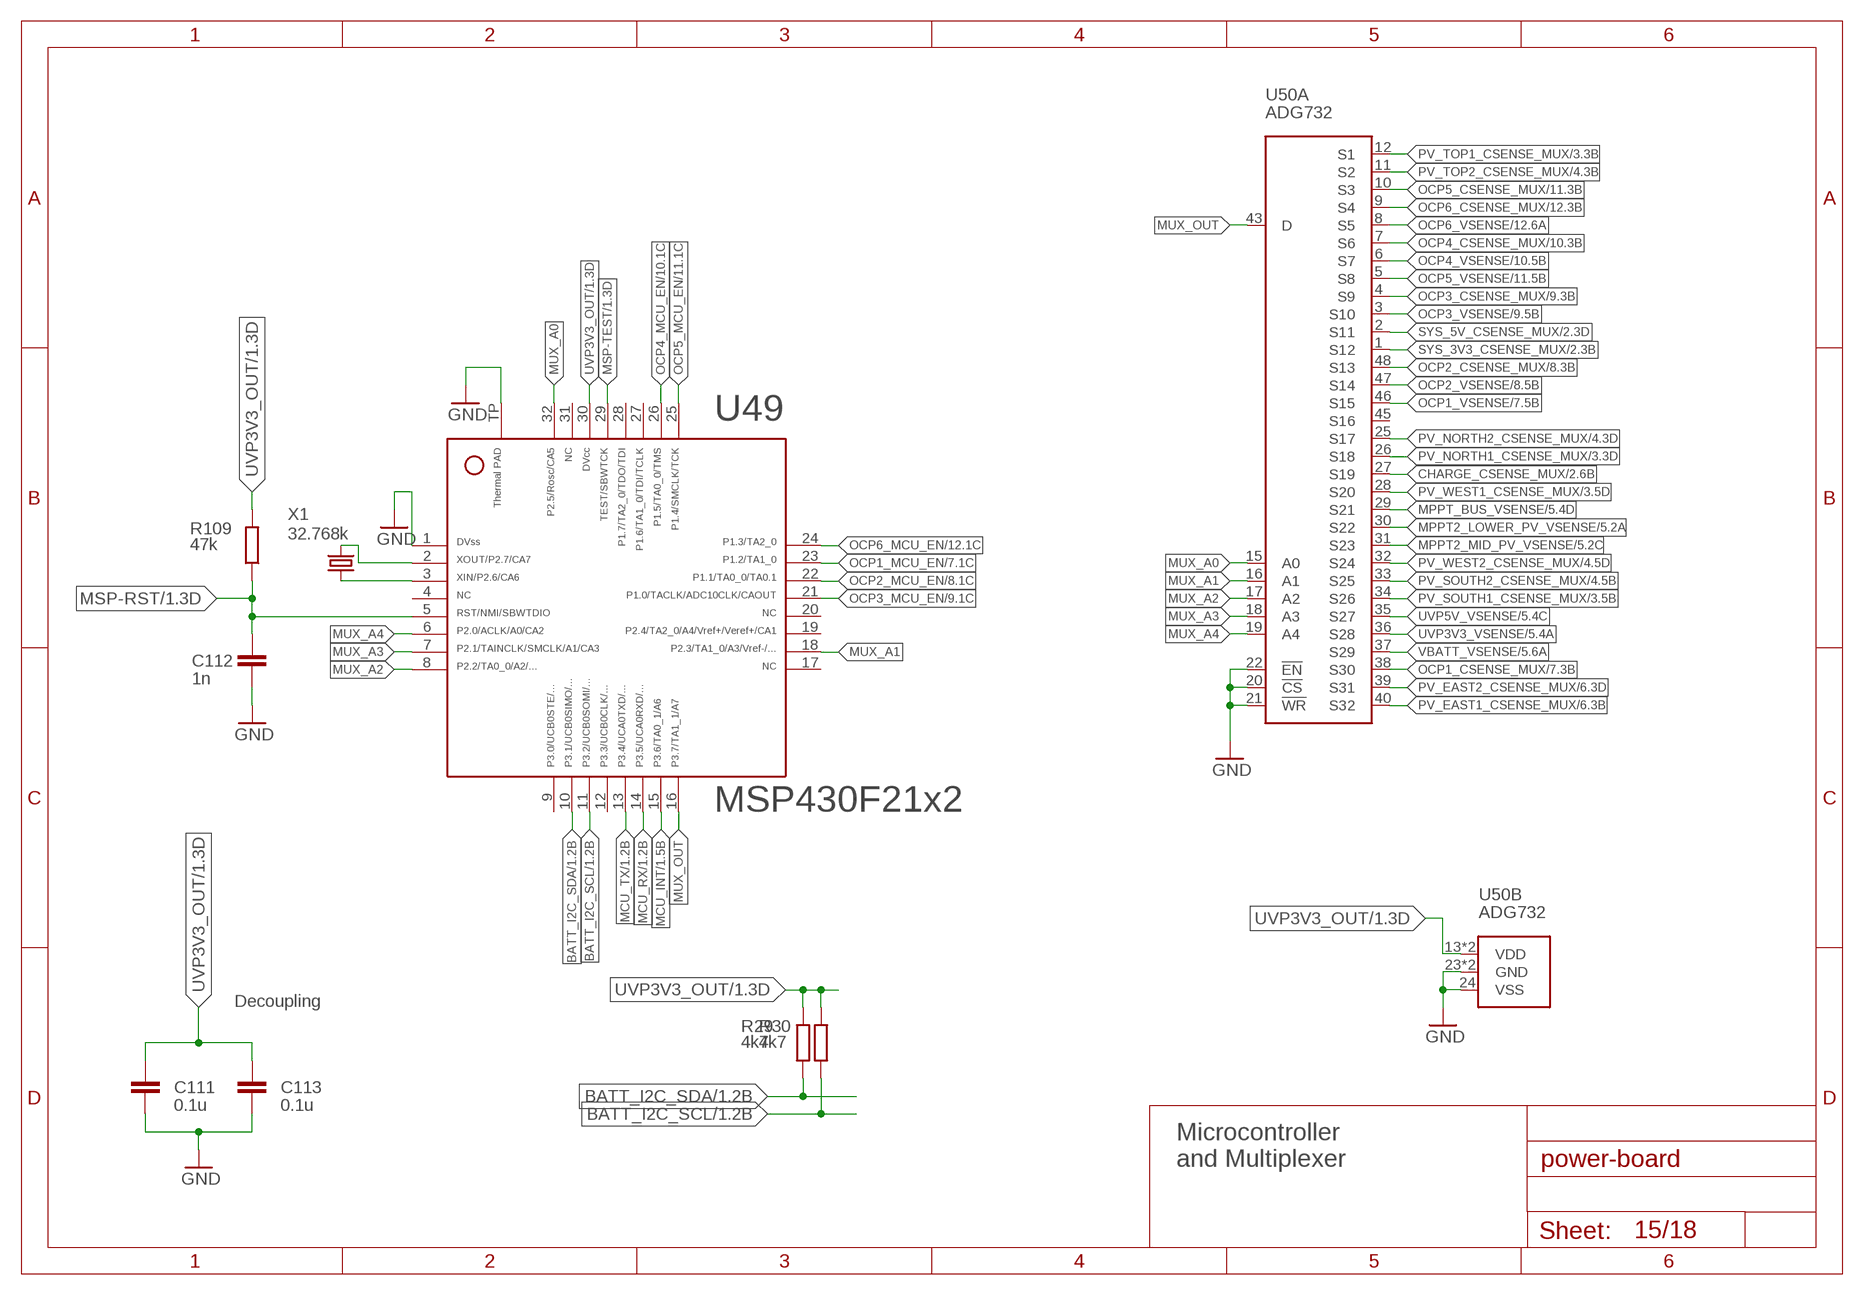
[diagram p14: schematic, sheet 15]
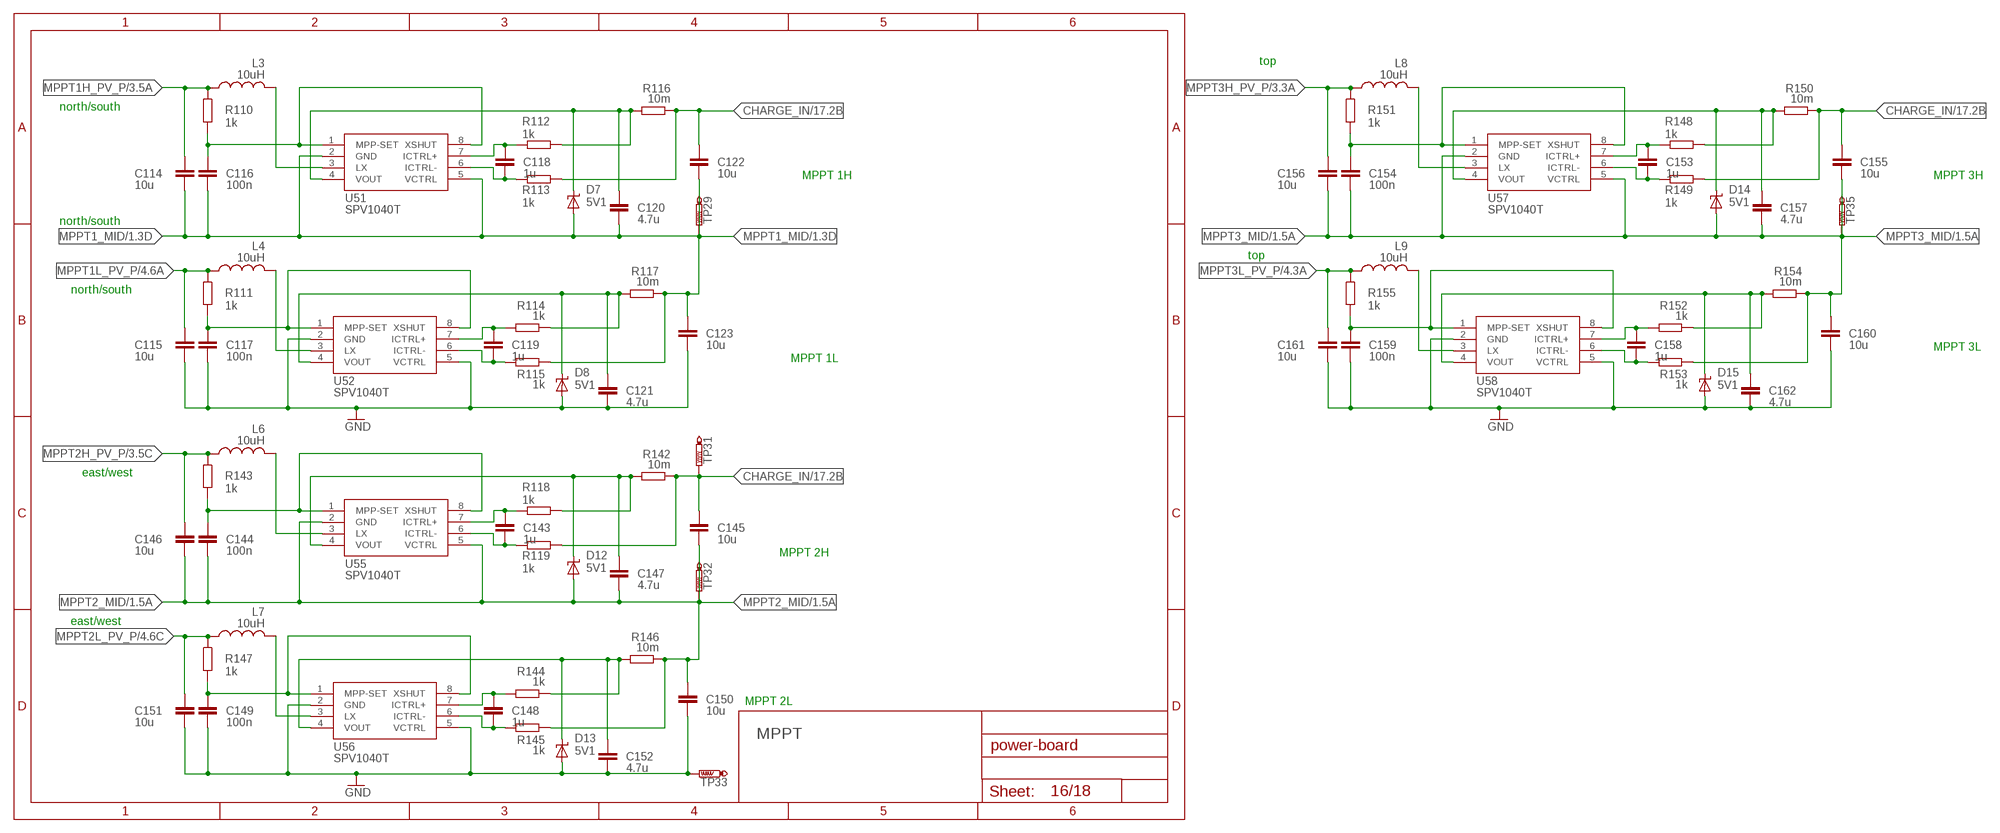
[diagram p15: schematic, sheet 16]
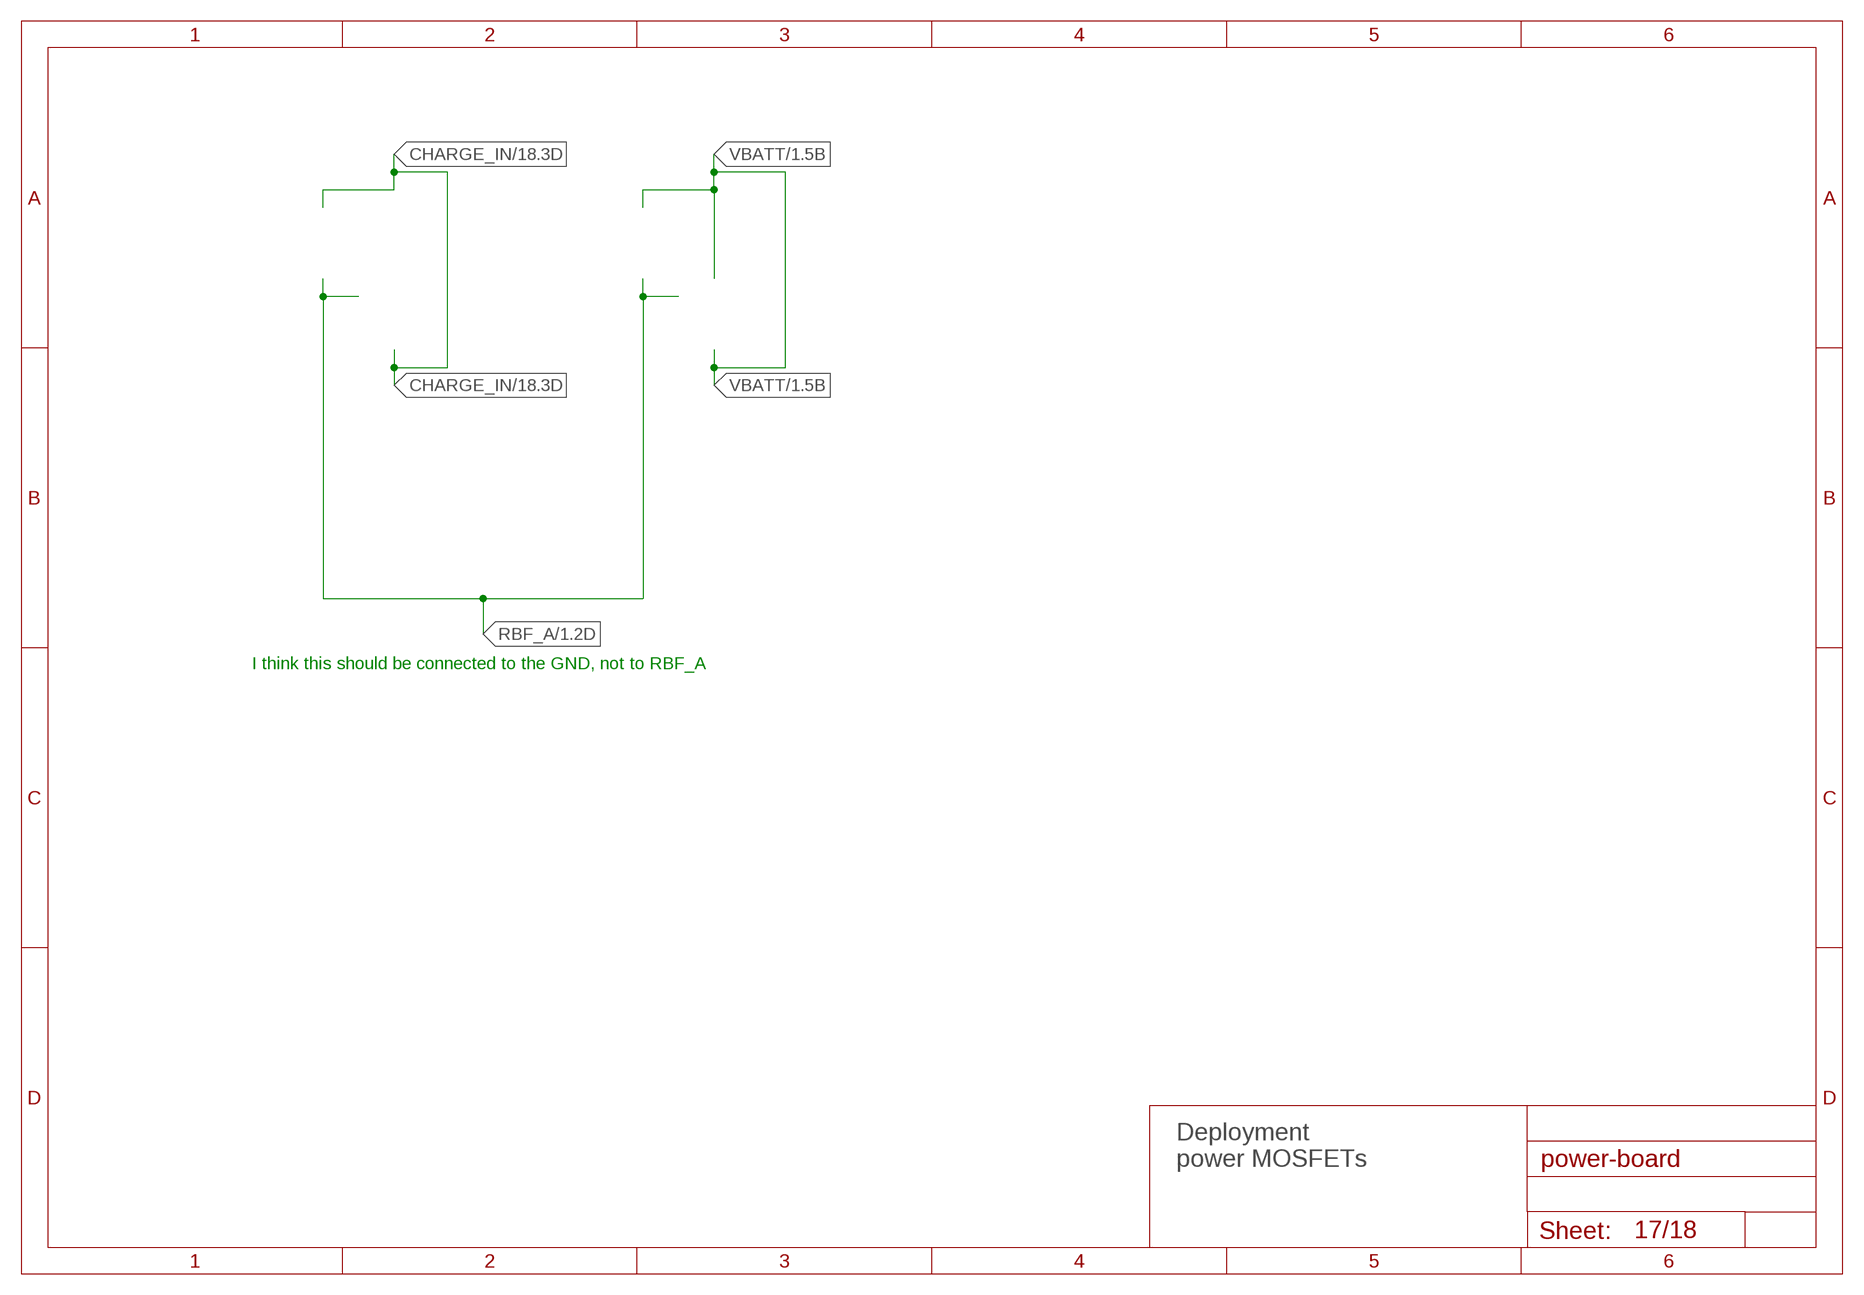
[diagram p16: schematic, sheet 17]
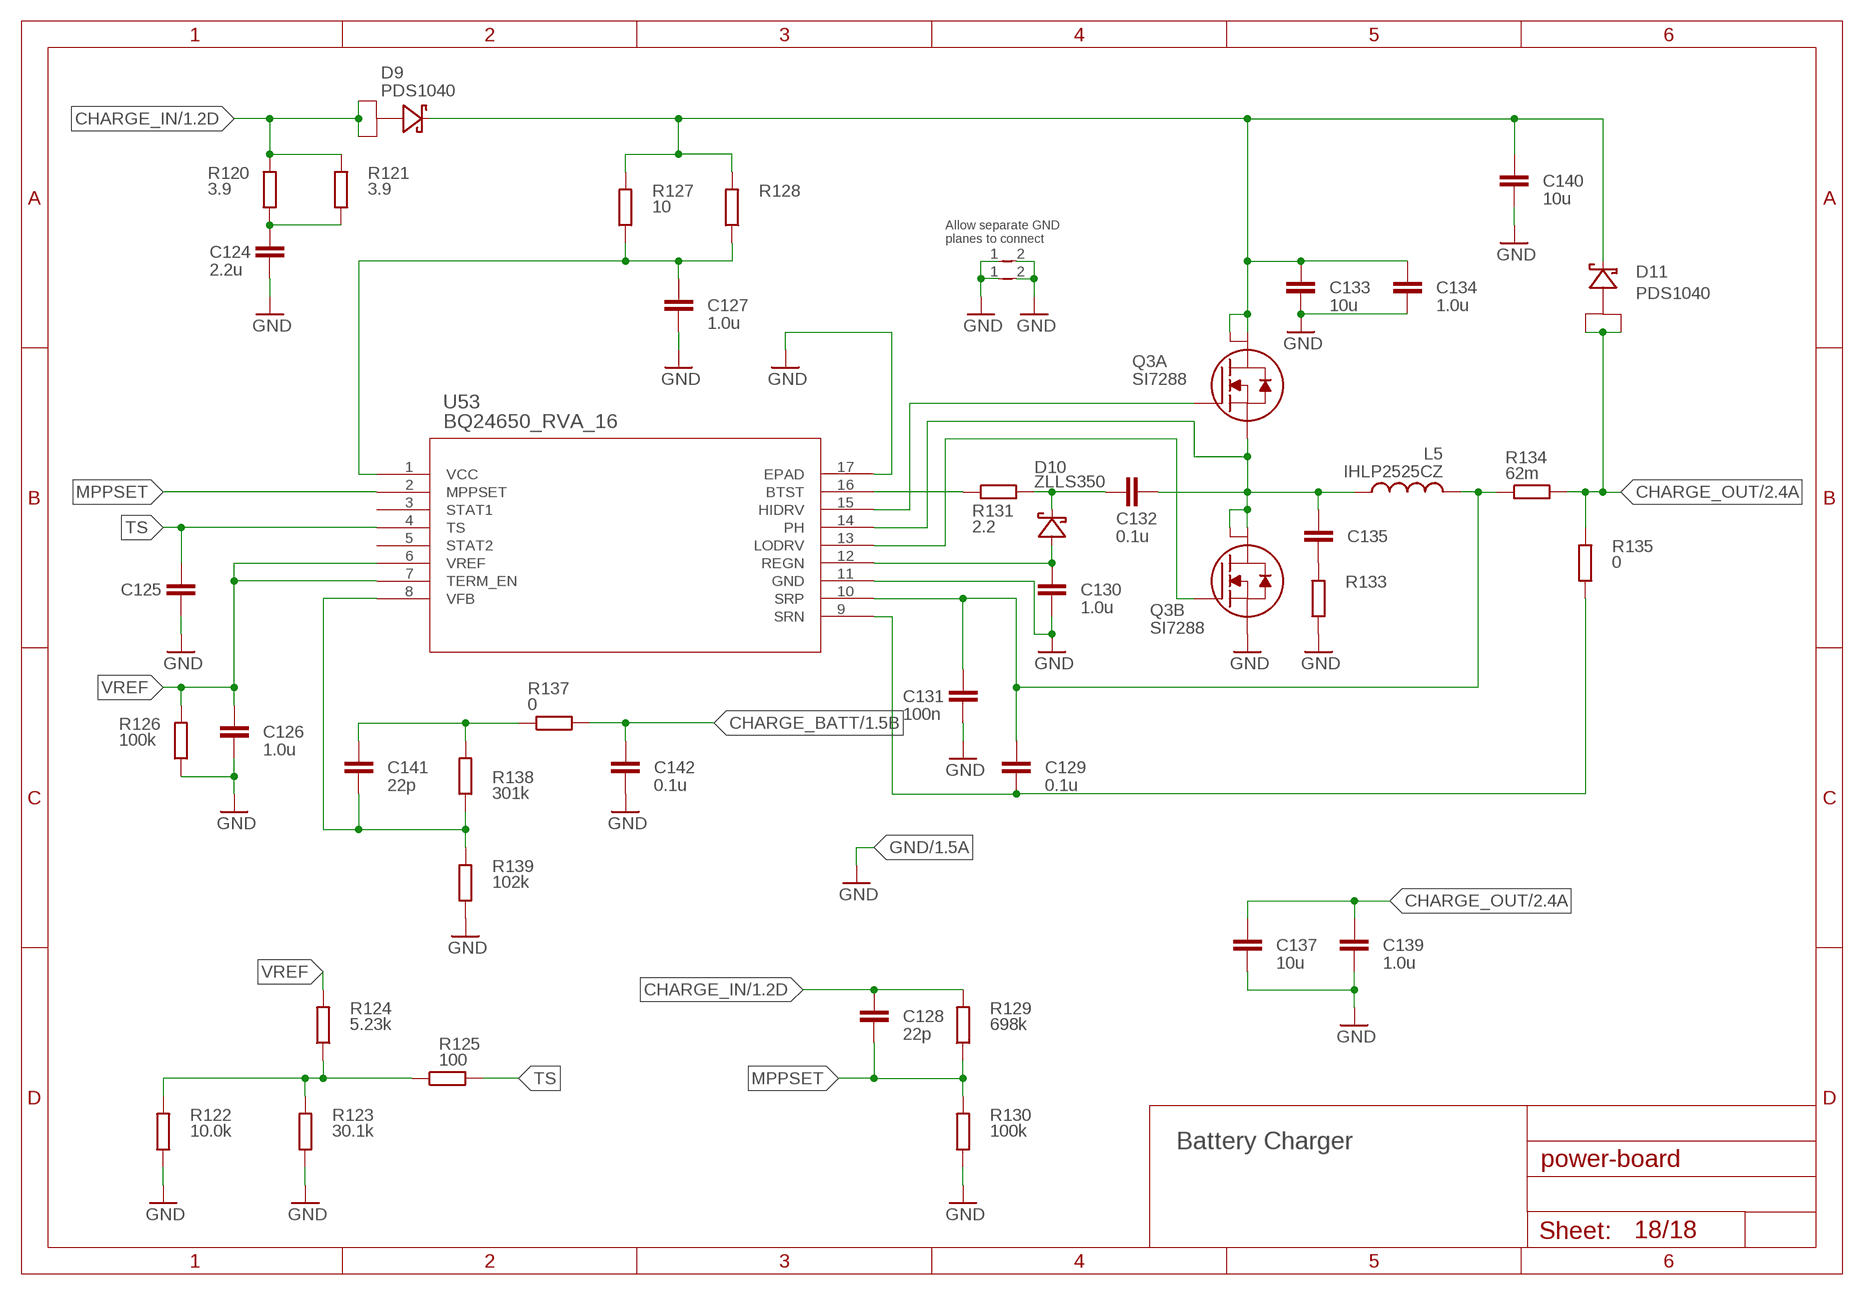
[diagram p17: schematic, sheet 18]

(export (version "E")
  (design (tool "Eeschema 10.0.6"))
  (components
    (comp (ref "C114")
      (value "10u")
      (footprint "eagle-import:C0805K")
      (libsource (lib "eagle-import") (part "C-EUC0805K"))
    )
    (comp (ref "C115")
      (value "10u")
      (footprint "eagle-import:C0805K")
      (libsource (lib "eagle-import") (part "C-EUC0805K"))
    )
    (comp (ref "C116")
      (value "100n")
      (footprint "eagle-import:C0603K")
      (libsource (lib "eagle-import") (part "C-EUC0603K"))
    )
    (comp (ref "C117")
      (value "100n")
      (footprint "eagle-import:C0603K")
      (libsource (lib "eagle-import") (part "C-EUC0603K"))
    )
    (comp (ref "C118")
      (value "1u")
      (footprint "eagle-import:C0603K")
      (libsource (lib "eagle-import") (part "C-EUC0603K"))
    )
    (comp (ref "C119")
      (value "1u")
      (footprint "eagle-import:C0603K")
      (libsource (lib "eagle-import") (part "C-EUC0603K"))
    )
    (comp (ref "C120")
      (value "4.7u")
      (footprint "eagle-import:C0805K")
      (libsource (lib "eagle-import") (part "C-EUC0805K"))
    )
    (comp (ref "C121")
      (value "4.7u")
      (footprint "eagle-import:C0805K")
      (libsource (lib "eagle-import") (part "C-EUC0805K"))
    )
    (comp (ref "C122")
      (value "10u")
      (footprint "eagle-import:C0805K")
      (libsource (lib "eagle-import") (part "C-EUC0805K"))
    )
    (comp (ref "C123")
      (value "10u")
      (footprint "eagle-import:C0805K")
      (libsource (lib "eagle-import") (part "C-EUC0805K"))
    )
    (comp (ref "C143")
      (value "1u")
      (footprint "eagle-import:C0603K")
      (libsource (lib "eagle-import") (part "C-EUC0603K"))
    )
    (comp (ref "C144")
      (value "100n")
      (footprint "eagle-import:C0603K")
      (libsource (lib "eagle-import") (part "C-EUC0603K"))
    )
    (comp (ref "C145")
      (value "10u")
      (footprint "eagle-import:C0805K")
      (libsource (lib "eagle-import") (part "C-EUC0805K"))
    )
    (comp (ref "C146")
      (value "10u")
      (footprint "eagle-import:C0805K")
      (libsource (lib "eagle-import") (part "C-EUC0805K"))
    )
    (comp (ref "C147")
      (value "4.7u")
      (footprint "eagle-import:C0805K")
      (libsource (lib "eagle-import") (part "C-EUC0805K"))
    )
    (comp (ref "C148")
      (value "1u")
      (footprint "eagle-import:C0603K")
      (libsource (lib "eagle-import") (part "C-EUC0603K"))
    )
    (comp (ref "C149")
      (value "100n")
      (footprint "eagle-import:C0603K")
      (libsource (lib "eagle-import") (part "C-EUC0603K"))
    )
    (comp (ref "C150")
      (value "10u")
      (footprint "eagle-import:C0805K")
      (libsource (lib "eagle-import") (part "C-EUC0805K"))
    )
    (comp (ref "C151")
      (value "10u")
      (footprint "eagle-import:C0805K")
      (libsource (lib "eagle-import") (part "C-EUC0805K"))
    )
    (comp (ref "C152")
      (value "4.7u")
      (footprint "eagle-import:C0805K")
      (libsource (lib "eagle-import") (part "C-EUC0805K"))
    )
    (comp (ref "C153")
      (value "1u")
      (footprint "eagle-import:C0603K")
      (libsource (lib "eagle-import") (part "C-EUC0603K"))
    )
    (comp (ref "C154")
      (value "100n")
      (footprint "eagle-import:C0603K")
      (libsource (lib "eagle-import") (part "C-EUC0603K"))
    )
    (comp (ref "C155")
      (value "10u")
      (footprint "eagle-import:C0805K")
      (libsource (lib "eagle-import") (part "C-EUC0805K"))
    )
    (comp (ref "C156")
      (value "10u")
      (footprint "eagle-import:C0805K")
      (libsource (lib "eagle-import") (part "C-EUC0805K"))
    )
    (comp (ref "C157")
      (value "4.7u")
      (footprint "eagle-import:C0805K")
      (libsource (lib "eagle-import") (part "C-EUC0805K"))
    )
    (comp (ref "C158")
      (value "1u")
      (footprint "eagle-import:C0603K")
      (libsource (lib "eagle-import") (part "C-EUC0603K"))
    )
    (comp (ref "C159")
      (value "100n")
      (footprint "eagle-import:C0603K")
      (libsource (lib "eagle-import") (part "C-EUC0603K"))
    )
    (comp (ref "C160")
      (value "10u")
      (footprint "eagle-import:C0805K")
      (libsource (lib "eagle-import") (part "C-EUC0805K"))
    )
    (comp (ref "C161")
      (value "10u")
      (footprint "eagle-import:C0805K")
      (libsource (lib "eagle-import") (part "C-EUC0805K"))
    )
    (comp (ref "C162")
      (value "4.7u")
      (footprint "eagle-import:C0805K")
      (libsource (lib "eagle-import") (part "C-EUC0805K"))
    )
    (comp (ref "D7")
      (value "5V1")
      (footprint "eagle-import:SMBJ")
      (libsource (lib "eagle-import") (part "SUPPRESSOR-SMBJ"))
    )
    (comp (ref "D8")
      (value "5V1")
      (footprint "eagle-import:SMBJ")
      (libsource (lib "eagle-import") (part "SUPPRESSOR-SMBJ"))
    )
    (comp (ref "D12")
      (value "5V1")
      (footprint "eagle-import:SMBJ")
      (libsource (lib "eagle-import") (part "SUPPRESSOR-SMBJ"))
    )
    (comp (ref "D13")
      (value "5V1")
      (footprint "eagle-import:SMBJ")
      (libsource (lib "eagle-import") (part "SUPPRESSOR-SMBJ"))
    )
    (comp (ref "D14")
      (value "5V1")
      (footprint "eagle-import:SMBJ")
      (libsource (lib "eagle-import") (part "SUPPRESSOR-SMBJ"))
    )
    (comp (ref "D15")
      (value "5V1")
      (footprint "eagle-import:SMBJ")
      (libsource (lib "eagle-import") (part "SUPPRESSOR-SMBJ"))
    )
    (comp (ref "L3")
      (value "10uH")
      (footprint "eagle-import:MSS7341")
      (libsource (lib "eagle-import") (part "MSS7341"))
    )
    (comp (ref "L4")
      (value "10uH")
      (footprint "eagle-import:MSS7341")
      (libsource (lib "eagle-import") (part "MSS7341"))
    )
    (comp (ref "L6")
      (value "10uH")
      (footprint "eagle-import:MSS7341")
      (libsource (lib "eagle-import") (part "MSS7341"))
    )
    (comp (ref "L7")
      (value "10uH")
      (footprint "eagle-import:MSS7341")
      (libsource (lib "eagle-import") (part "MSS7341"))
    )
    (comp (ref "L8")
      (value "10uH")
      (footprint "eagle-import:MSS7341")
      (libsource (lib "eagle-import") (part "MSS7341"))
    )
    (comp (ref "L9")
      (value "10uH")
      (footprint "eagle-import:MSS7341")
      (libsource (lib "eagle-import") (part "MSS7341"))
    )
    (comp (ref "R110")
      (value "1k")
      (footprint "eagle-import:R0603")
      (libsource (lib "eagle-import") (part "R-EU_R0603"))
    )
    (comp (ref "R111")
      (value "1k")
      (footprint "eagle-import:R0603")
      (libsource (lib "eagle-import") (part "R-EU_R0603"))
    )
    (comp (ref "R112")
      (value "1k")
      (footprint "eagle-import:R0603")
      (libsource (lib "eagle-import") (part "R-EU_R0603"))
    )
    (comp (ref "R113")
      (value "1k")
      (footprint "eagle-import:R0603")
      (libsource (lib "eagle-import") (part "R-EU_R0603"))
    )
    (comp (ref "R114")
      (value "1k")
      (footprint "eagle-import:R0603")
      (libsource (lib "eagle-import") (part "R-EU_R0603"))
    )
    (comp (ref "R115")
      (value "1k")
      (footprint "eagle-import:R0603")
      (libsource (lib "eagle-import") (part "R-EU_R0603"))
    )
    (comp (ref "R116")
      (value "10m")
      (footprint "eagle-import:R1206")
      (libsource (lib "eagle-import") (part "R-EU_R1206"))
    )
    (comp (ref "R117")
      (value "10m")
      (footprint "eagle-import:R1206")
      (libsource (lib "eagle-import") (part "R-EU_R1206"))
    )
    (comp (ref "R118")
      (value "1k")
      (footprint "eagle-import:R0603")
      (libsource (lib "eagle-import") (part "R-EU_R0603"))
    )
    (comp (ref "R119")
      (value "1k")
      (footprint "eagle-import:R0603")
      (libsource (lib "eagle-import") (part "R-EU_R0603"))
    )
    (comp (ref "R142")
      (value "10m")
      (footprint "eagle-import:R1206")
      (libsource (lib "eagle-import") (part "R-EU_R1206"))
    )
    (comp (ref "R143")
      (value "1k")
      (footprint "eagle-import:R0603")
      (libsource (lib "eagle-import") (part "R-EU_R0603"))
    )
    (comp (ref "R144")
      (value "1k")
      (footprint "eagle-import:R0603")
      (libsource (lib "eagle-import") (part "R-EU_R0603"))
    )
    (comp (ref "R145")
      (value "1k")
      (footprint "eagle-import:R0603")
      (libsource (lib "eagle-import") (part "R-EU_R0603"))
    )
    (comp (ref "R146")
      (value "10m")
      (footprint "eagle-import:R1206")
      (libsource (lib "eagle-import") (part "R-EU_R1206"))
    )
    (comp (ref "R147")
      (value "1k")
      (footprint "eagle-import:R0603")
      (libsource (lib "eagle-import") (part "R-EU_R0603"))
    )
    (comp (ref "R148")
      (value "1k")
      (footprint "eagle-import:R0603")
      (libsource (lib "eagle-import") (part "R-EU_R0603"))
    )
    (comp (ref "R149")
      (value "1k")
      (footprint "eagle-import:R0603")
      (libsource (lib "eagle-import") (part "R-EU_R0603"))
    )
    (comp (ref "R150")
      (value "10m")
      (footprint "eagle-import:R1206")
      (libsource (lib "eagle-import") (part "R-EU_R1206"))
    )
    (comp (ref "R151")
      (value "1k")
      (footprint "eagle-import:R0603")
      (libsource (lib "eagle-import") (part "R-EU_R0603"))
    )
    (comp (ref "R152")
      (value "1k")
      (footprint "eagle-import:R0603")
      (libsource (lib "eagle-import") (part "R-EU_R0603"))
    )
    (comp (ref "R153")
      (value "1k")
      (footprint "eagle-import:R0603")
      (libsource (lib "eagle-import") (part "R-EU_R0603"))
    )
    (comp (ref "R154")
      (value "10m")
      (footprint "eagle-import:R1206")
      (libsource (lib "eagle-import") (part "R-EU_R1206"))
    )
    (comp (ref "R155")
      (value "1k")
      (footprint "eagle-import:R0603")
      (libsource (lib "eagle-import") (part "R-EU_R0603"))
    )
    (comp (ref "TP29")
      (value "PTR1TP09R")
      (footprint "eagle-import:TP09R")
      (libsource (lib "eagle-import") (part "PTR1TP09R"))
    )
    (comp (ref "TP31")
      (value "PTR1TP09R")
      (footprint "eagle-import:TP09R")
      (libsource (lib "eagle-import") (part "PTR1TP09R"))
    )
    (comp (ref "TP32")
      (value "PTR1TP09R")
      (footprint "eagle-import:TP09R")
      (libsource (lib "eagle-import") (part "PTR1TP09R"))
    )
    (comp (ref "TP33")
      (value "PTR1TP09R")
      (footprint "eagle-import:TP09R")
      (libsource (lib "eagle-import") (part "PTR1TP09R"))
    )
    (comp (ref "TP35")
      (value "PTR1TP09R")
      (footprint "eagle-import:TP09R")
      (libsource (lib "eagle-import") (part "PTR1TP09R"))
    )
    (comp (ref "U51")
      (value "SPV1040T")
      (footprint "eagle-import:TSSOP8")
      (libsource (lib "eagle-import") (part "SPV1040T"))
    )
    (comp (ref "U52")
      (value "SPV1040T")
      (footprint "eagle-import:TSSOP8")
      (libsource (lib "eagle-import") (part "SPV1040T"))
    )
    (comp (ref "U55")
      (value "SPV1040T")
      (footprint "eagle-import:TSSOP8")
      (libsource (lib "eagle-import") (part "SPV1040T"))
    )
    (comp (ref "U56")
      (value "SPV1040T")
      (footprint "eagle-import:TSSOP8")
      (libsource (lib "eagle-import") (part "SPV1040T"))
    )
    (comp (ref "U57")
      (value "SPV1040T")
      (footprint "eagle-import:TSSOP8")
      (libsource (lib "eagle-import") (part "SPV1040T"))
    )
    (comp (ref "U58")
      (value "SPV1040T")
      (footprint "eagle-import:TSSOP8")
      (libsource (lib "eagle-import") (part "SPV1040T"))
    )
    (comp (ref "C54")
      (value "100n")
      (footprint "eagle-import:C0603")
      (libsource (lib "eagle-import") (part "C-EUC0603"))
    )
    (comp (ref "C55")
      (value "100n")
      (footprint "eagle-import:C0603")
      (libsource (lib "eagle-import") (part "C-EUC0603"))
    )
    (comp (ref "C56")
      (value "100n")
      (footprint "eagle-import:C0603")
      (libsource (lib "eagle-import") (part "C-EUC0603"))
    )
    (comp (ref "C57")
      (value "1n")
      (footprint "eagle-import:C0603")
      (libsource (lib "eagle-import") (part "C-EUC0603"))
    )
    (comp (ref "C58")
      (value "1u")
      (footprint "eagle-import:C0603")
      (libsource (lib "eagle-import") (part "C-EUC0603"))
    )
    (comp (ref "C59")
      (value "100n")
      (footprint "eagle-import:C0603")
      (libsource (lib "eagle-import") (part "C-EUC0603"))
    )
    (comp (ref "C60")
      (value "1u")
      (footprint "eagle-import:C0603")
      (libsource (lib "eagle-import") (part "C-EUC0603"))
    )
    (comp (ref "C61")
      (value "1n")
      (footprint "eagle-import:C0603")
      (libsource (lib "eagle-import") (part "C-EUC0603"))
    )
    (comp (ref "C62")
      (value "22u")
      (footprint "eagle-import:C1210")
      (libsource (lib "eagle-import") (part "C-EUC1210"))
    )
    (comp (ref "C63")
      (value "100n")
      (footprint "eagle-import:C0603")
      (libsource (lib "eagle-import") (part "C-EUC0603"))
    )
    (comp (ref "C64")
      (value "510p")
      (footprint "eagle-import:C0603")
      (libsource (lib "eagle-import") (part "C-EUC0603"))
    )
    (comp (ref "D3")
      (value "PMEG2005AEA")
      (footprint "eagle-import:SOD-323")
      (libsource (lib "eagle-import") (part "PMEG2005AEA"))
    )
    (comp (ref "R57")
      (value "124m")
      (footprint "eagle-import:R1206")
      (libsource (lib "eagle-import") (part "R-EU_R1206"))
    )
    (comp (ref "R58")
      (value "100k")
      (footprint "eagle-import:R0603")
      (libsource (lib "eagle-import") (part "R-EU_R0603"))
    )
    (comp (ref "R59")
      (value "1k")
      (footprint "eagle-import:R0603")
      (libsource (lib "eagle-import") (part "R-EU_R0603"))
    )
    (comp (ref "R60")
      (value "10k")
      (footprint "eagle-import:R0603")
      (libsource (lib "eagle-import") (part "R-EU_R0603"))
    )
    (comp (ref "R61")
      (value "499k")
      (footprint "eagle-import:R0603")
      (libsource (lib "eagle-import") (part "R-EU_R0603"))
    )
    (comp (ref "R62")
      (value "100k")
      (footprint "eagle-import:R0603")
      (libsource (lib "eagle-import") (part "R-EU_R0603"))
    )
    (comp (ref "R63")
      (value "0")
      (footprint "eagle-import:R0603")
      (libsource (lib "eagle-import") (part "R-EU_R0603"))
    )
    (comp (ref "R64")
      (value "309k")
      (footprint "eagle-import:R0603")
      (libsource (lib "eagle-import") (part "R-EU_R0603"))
    )
    (comp (ref "R65")
      (value "100k")
      (footprint "eagle-import:R0603")
      (libsource (lib "eagle-import") (part "R-EU_R0603"))
    )
    (comp (ref "TP7")
      (value "PTR1TP09R")
      (footprint "eagle-import:TP09R")
      (libsource (lib "eagle-import") (part "PTR1TP09R"))
    )
    (comp (ref "TP8")
      (value "PTR1TP09R")
      (footprint "eagle-import:TP09R")
      (libsource (lib "eagle-import") (part "PTR1TP09R"))
    )
    (comp (ref "TP25")
      (value "PTR1TP09R")
      (footprint "eagle-import:TP09R")
      (libsource (lib "eagle-import") (part "PTR1TP09R"))
    )
    (comp (ref "U23")
      (value "MCP6561T-E/LT")
      (footprint "eagle-import:SOT23-5")
      (libsource (lib "eagle-import") (part "MCP6561T-E/LT"))
    )
    (comp (ref "U24")
      (value "INA214DCK")
      (footprint "eagle-import:SC70-6")
      (libsource (lib "eagle-import") (part "INA214DCK"))
    )
    (comp (ref "U25")
      (value "SN74AUP1G00DCK")
      (footprint "eagle-import:SC70-5")
      (libsource (lib "eagle-import") (part "SN74AUP1G00DCK"))
    )
    (comp (ref "U26")
      (value "SN74LVC1G373DCK")
      (footprint "eagle-import:SC70-6")
      (libsource (lib "eagle-import") (part "SN74LVC1G373DCK"))
    )
    (comp (ref "U27")
      (value "NTHD4508NT1")
      (footprint "eagle-import:CHIPFET-1206A-S2")
      (libsource (lib "eagle-import") (part "NTHD4508NT1"))
    )
    (comp (ref "C43")
      (value "100n")
      (footprint "eagle-import:C0603")
      (libsource (lib "eagle-import") (part "C-EUC0603"))
    )
    (comp (ref "C44")
      (value "100n")
      (footprint "eagle-import:C0603")
      (libsource (lib "eagle-import") (part "C-EUC0603"))
    )
    (comp (ref "C45")
      (value "100n")
      (footprint "eagle-import:C0603")
      (libsource (lib "eagle-import") (part "C-EUC0603"))
    )
    (comp (ref "C46")
      (value "1n")
      (footprint "eagle-import:C0603")
      (libsource (lib "eagle-import") (part "C-EUC0603"))
    )
    (comp (ref "C47")
      (value "1u")
      (footprint "eagle-import:C0603")
      (libsource (lib "eagle-import") (part "C-EUC0603"))
    )
    (comp (ref "C48")
      (value "100n")
      (footprint "eagle-import:C0603")
      (libsource (lib "eagle-import") (part "C-EUC0603"))
    )
    (comp (ref "C49")
      (value "1u")
      (footprint "eagle-import:C0603")
      (libsource (lib "eagle-import") (part "C-EUC0603"))
    )
    (comp (ref "C50")
      (value "1n")
      (footprint "eagle-import:C0603")
      (libsource (lib "eagle-import") (part "C-EUC0603"))
    )
    (comp (ref "C51")
      (value "22u")
      (footprint "eagle-import:C1210")
      (libsource (lib "eagle-import") (part "C-EUC1210"))
    )
    (comp (ref "C52")
      (value "100n")
      (footprint "eagle-import:C0603")
      (libsource (lib "eagle-import") (part "C-EUC0603"))
    )
    (comp (ref "C53")
      (value "510p")
      (footprint "eagle-import:C0603")
      (libsource (lib "eagle-import") (part "C-EUC0603"))
    )
    (comp (ref "D2")
      (value "PMEG2005AEA")
      (footprint "eagle-import:SOD-323")
      (libsource (lib "eagle-import") (part "PMEG2005AEA"))
    )
    (comp (ref "R48")
      (value "124m")
      (footprint "eagle-import:R1206")
      (libsource (lib "eagle-import") (part "R-EU_R1206"))
    )
    (comp (ref "R49")
      (value "100k")
      (footprint "eagle-import:R0603")
      (libsource (lib "eagle-import") (part "R-EU_R0603"))
    )
    (comp (ref "R50")
      (value "1k")
      (footprint "eagle-import:R0603")
      (libsource (lib "eagle-import") (part "R-EU_R0603"))
    )
    (comp (ref "R51")
      (value "10k")
      (footprint "eagle-import:R0603")
      (libsource (lib "eagle-import") (part "R-EU_R0603"))
    )
    (comp (ref "R52")
      (value "499k")
      (footprint "eagle-import:R0603")
      (libsource (lib "eagle-import") (part "R-EU_R0603"))
    )
    (comp (ref "R53")
      (value "100k")
      (footprint "eagle-import:R0603")
      (libsource (lib "eagle-import") (part "R-EU_R0603"))
    )
    (comp (ref "R54")
      (value "0")
      (footprint "eagle-import:R0603")
      (libsource (lib "eagle-import") (part "R-EU_R0603"))
    )
    (comp (ref "R55")
      (value "309k")
      (footprint "eagle-import:R0603")
      (libsource (lib "eagle-import") (part "R-EU_R0603"))
    )
    (comp (ref "R56")
      (value "100k")
      (footprint "eagle-import:R0603")
      (libsource (lib "eagle-import") (part "R-EU_R0603"))
    )
    (comp (ref "TP9")
      (value "PTR1TP09R")
      (footprint "eagle-import:TP09R")
      (libsource (lib "eagle-import") (part "PTR1TP09R"))
    )
    (comp (ref "TP10")
      (value "PTR1TP09R")
      (footprint "eagle-import:TP09R")
      (libsource (lib "eagle-import") (part "PTR1TP09R"))
    )
    (comp (ref "TP26")
      (value "PTR1TP09R")
      (footprint "eagle-import:TP09R")
      (libsource (lib "eagle-import") (part "PTR1TP09R"))
    )
    (comp (ref "U18")
      (value "MCP6561T-E/LT")
      (footprint "eagle-import:SOT23-5")
      (libsource (lib "eagle-import") (part "MCP6561T-E/LT"))
    )
    (comp (ref "U19")
      (value "INA214DCK")
      (footprint "eagle-import:SC70-6")
      (libsource (lib "eagle-import") (part "INA214DCK"))
    )
    (comp (ref "U20")
      (value "SN74AUP1G00DCK")
      (footprint "eagle-import:SC70-5")
      (libsource (lib "eagle-import") (part "SN74AUP1G00DCK"))
    )
    (comp (ref "U21")
      (value "SN74LVC1G373DCK")
      (footprint "eagle-import:SC70-6")
      (libsource (lib "eagle-import") (part "SN74LVC1G373DCK"))
    )
    (comp (ref "U22")
      (value "NTHD4508NT1")
      (footprint "eagle-import:CHIPFET-1206A-S2")
      (libsource (lib "eagle-import") (part "NTHD4508NT1"))
    )
    (comp (ref "C32")
      (value "100n")
      (footprint "eagle-import:C0603")
      (libsource (lib "eagle-import") (part "C-EUC0603"))
    )
    (comp (ref "C33")
      (value "100n")
      (footprint "eagle-import:C0603")
      (libsource (lib "eagle-import") (part "C-EUC0603"))
    )
    (comp (ref "C34")
      (value "100n")
      (footprint "eagle-import:C0603")
      (libsource (lib "eagle-import") (part "C-EUC0603"))
    )
    (comp (ref "C35")
      (value "1n")
      (footprint "eagle-import:C0603")
      (libsource (lib "eagle-import") (part "C-EUC0603"))
    )
    (comp (ref "C36")
      (value "1u")
      (footprint "eagle-import:C0603")
      (libsource (lib "eagle-import") (part "C-EUC0603"))
    )
    (comp (ref "C37")
      (value "100n")
      (footprint "eagle-import:C0603")
      (libsource (lib "eagle-import") (part "C-EUC0603"))
    )
    (comp (ref "C38")
      (value "1u")
      (footprint "eagle-import:C0603")
      (libsource (lib "eagle-import") (part "C-EUC0603"))
    )
    (comp (ref "C39")
      (value "1n")
      (footprint "eagle-import:C0603")
      (libsource (lib "eagle-import") (part "C-EUC0603"))
    )
    (comp (ref "C40")
      (value "22u")
      (footprint "eagle-import:C1210")
      (libsource (lib "eagle-import") (part "C-EUC1210"))
    )
    (comp (ref "C41")
      (value "100n")
      (footprint "eagle-import:C0603")
      (libsource (lib "eagle-import") (part "C-EUC0603"))
    )
    (comp (ref "C42")
      (value "510p")
      (footprint "eagle-import:C0603")
      (libsource (lib "eagle-import") (part "C-EUC0603"))
    )
    (comp (ref "D1")
      (value "PMEG2005AEA")
      (footprint "eagle-import:SOD-323")
      (libsource (lib "eagle-import") (part "PMEG2005AEA"))
    )
    (comp (ref "R39")
      (value "50m")
      (footprint "eagle-import:R1206")
      (libsource (lib "eagle-import") (part "R-EU_R1206"))
    )
    (comp (ref "R40")
      (value "100k")
      (footprint "eagle-import:R0603")
      (libsource (lib "eagle-import") (part "R-EU_R0603"))
    )
    (comp (ref "R41")
      (value "1k")
      (footprint "eagle-import:R0603")
      (libsource (lib "eagle-import") (part "R-EU_R0603"))
    )
    (comp (ref "R42")
      (value "10k")
      (footprint "eagle-import:R0603")
      (libsource (lib "eagle-import") (part "R-EU_R0603"))
    )
    (comp (ref "R43")
      (value "499k")
      (footprint "eagle-import:R0603")
      (libsource (lib "eagle-import") (part "R-EU_R0603"))
    )
    (comp (ref "R44")
      (value "100k")
      (footprint "eagle-import:R0603")
      (libsource (lib "eagle-import") (part "R-EU_R0603"))
    )
    (comp (ref "R45")
      (value "0")
      (footprint "eagle-import:R0603")
      (libsource (lib "eagle-import") (part "R-EU_R0603"))
    )
    (comp (ref "R46")
      (value "309k")
      (footprint "eagle-import:R0603")
      (libsource (lib "eagle-import") (part "R-EU_R0603"))
    )
    (comp (ref "R47")
      (value "100k")
      (footprint "eagle-import:R0603")
      (libsource (lib "eagle-import") (part "R-EU_R0603"))
    )
    (comp (ref "TP11")
      (value "PTR1TP09R")
      (footprint "eagle-import:TP09R")
      (libsource (lib "eagle-import") (part "PTR1TP09R"))
    )
    (comp (ref "TP12")
      (value "PTR1TP09R")
      (footprint "eagle-import:TP09R")
      (libsource (lib "eagle-import") (part "PTR1TP09R"))
    )
    (comp (ref "TP27")
      (value "PTR1TP09R")
      (footprint "eagle-import:TP09R")
      (libsource (lib "eagle-import") (part "PTR1TP09R"))
    )
    (comp (ref "U13")
      (value "MCP6561T-E/LT")
      (footprint "eagle-import:SOT23-5")
      (libsource (lib "eagle-import") (part "MCP6561T-E/LT"))
    )
    (comp (ref "U14")
      (value "INA214DCK")
      (footprint "eagle-import:SC70-6")
      (libsource (lib "eagle-import") (part "INA214DCK"))
    )
    (comp (ref "U15")
      (value "SN74AUP1G00DCK")
      (footprint "eagle-import:SC70-5")
      (libsource (lib "eagle-import") (part "SN74AUP1G00DCK"))
    )
    (comp (ref "U16")
      (value "SN74LVC1G373DCK")
      (footprint "eagle-import:SC70-6")
      (libsource (lib "eagle-import") (part "SN74LVC1G373DCK"))
    )
    (comp (ref "U17")
      (value "NTHD4508NT1")
      (footprint "eagle-import:CHIPFET-1206A-S2")
      (libsource (lib "eagle-import") (part "NTHD4508NT1"))
    )
    (comp (ref "C124")
      (value "2.2u")
      (footprint "eagle-import:C1210")
      (libsource (lib "eagle-import") (part "C-EUC1210"))
    )
    (comp (ref "C125")
      (value "C0603")
      (footprint "eagle-import:P0603")
      (libsource (lib "eagle-import") (part "C0603"))
    )
    (comp (ref "C126")
      (value "1.0u")
      (footprint "eagle-import:P0805")
      (libsource (lib "eagle-import") (part "C0805"))
    )
    (comp (ref "C127")
      (value "1.0u")
      (footprint "eagle-import:P0805")
      (libsource (lib "eagle-import") (part "C0805"))
    )
    (comp (ref "C128")
      (value "22p")
      (footprint "eagle-import:P0603")
      (libsource (lib "eagle-import") (part "C0603"))
    )
    (comp (ref "C129")
      (value "0.1u")
      (footprint "eagle-import:P0603")
      (libsource (lib "eagle-import") (part "C0603"))
    )
    (comp (ref "C130")
      (value "1.0u")
      (footprint "eagle-import:P0805")
      (libsource (lib "eagle-import") (part "C0805"))
    )
    (comp (ref "C131")
      (value "100n")
      (footprint "eagle-import:P0603")
      (libsource (lib "eagle-import") (part "C0603"))
    )
    (comp (ref "C132")
      (value "0.1u")
      (footprint "eagle-import:P0603")
      (libsource (lib "eagle-import") (part "C0603"))
    )
    (comp (ref "C133")
      (value "10u")
      (footprint "eagle-import:C1210")
      (libsource (lib "eagle-import") (part "C-EUC1210"))
    )
    (comp (ref "C134")
      (value "1.0u")
      (footprint "eagle-import:C0805")
      (libsource (lib "eagle-import") (part "C-EUC0805"))
    )
    (comp (ref "C135")
      (value "C-EUC0603")
      (footprint "eagle-import:C0603")
      (libsource (lib "eagle-import") (part "C-EUC0603"))
    )
    (comp (ref "C137")
      (value "10u")
      (footprint "eagle-import:P1210")
      (libsource (lib "eagle-import") (part "C1210"))
    )
    (comp (ref "C139")
      (value "1.0u")
      (footprint "eagle-import:P0805")
      (libsource (lib "eagle-import") (part "C0805"))
    )
    (comp (ref "C140")
      (value "10u")
      (footprint "eagle-import:C1210")
      (libsource (lib "eagle-import") (part "C-EUC1210"))
    )
    (comp (ref "C141")
      (value "22p")
      (footprint "eagle-import:P0603")
      (libsource (lib "eagle-import") (part "C0603"))
    )
    (comp (ref "C142")
      (value "0.1u")
      (footprint "eagle-import:P0603")
      (libsource (lib "eagle-import") (part "C0603"))
    )
    (comp (ref "D9")
      (value "PDS1040")
      (footprint "eagle-import:POWERDI5")
      (libsource (lib "eagle-import") (part "PDS1040"))
    )
    (comp (ref "D10")
      (value "ZLLS350")
      (footprint "eagle-import:SOD-523")
      (libsource (lib "eagle-import") (part "ZLLS350"))
    )
    (comp (ref "D11")
      (value "PDS1040")
      (footprint "eagle-import:POWERDI5")
      (libsource (lib "eagle-import") (part "PDS1040"))
    )
    (comp (ref "L5")
      (value "IHLP2525CZ")
      (footprint "eagle-import:IHLP2525CZ")
      (libsource (lib "eagle-import") (part "IHLP2525CZ"))
    )
    (comp (ref "Q3")
      (value "SI7288")
      (footprint "eagle-import:SO8-POWERPAK_DUAL")
      (libsource (lib "eagle-import") (part "SI7288"))
    )
    (comp (ref "R120")
      (value "3.9")
      (footprint "eagle-import:R0603")
      (libsource (lib "eagle-import") (part "R-EU_R0603"))
    )
    (comp (ref "R121")
      (value "3.9")
      (footprint "eagle-import:R0603")
      (libsource (lib "eagle-import") (part "R-EU_R0603"))
    )
    (comp (ref "R122")
      (value "10.0k")
      (footprint "eagle-import:P0603")
      (libsource (lib "eagle-import") (part "R0603"))
    )
    (comp (ref "R123")
      (value "30.1k")
      (footprint "eagle-import:P0603")
      (libsource (lib "eagle-import") (part "R0603"))
    )
    (comp (ref "R124")
      (value "5.23k")
      (footprint "eagle-import:P0603")
      (libsource (lib "eagle-import") (part "R0603"))
    )
    (comp (ref "R125")
      (value "100")
      (footprint "eagle-import:P0603")
      (libsource (lib "eagle-import") (part "R0603"))
    )
    (comp (ref "R126")
      (value "100k")
      (footprint "eagle-import:P0603")
      (libsource (lib "eagle-import") (part "R0603"))
    )
    (comp (ref "R127")
      (value "10")
      (footprint "eagle-import:P0805")
      (libsource (lib "eagle-import") (part "R0805"))
    )
    (comp (ref "R128")
      (value "R0805")
      (footprint "eagle-import:P0805")
      (libsource (lib "eagle-import") (part "R0805"))
    )
    (comp (ref "R129")
      (value "698k")
      (footprint "eagle-import:P0603")
      (libsource (lib "eagle-import") (part "R0603"))
    )
    (comp (ref "R130")
      (value "100k")
      (footprint "eagle-import:P0603")
      (libsource (lib "eagle-import") (part "R0603"))
    )
    (comp (ref "R131")
      (value "2.2")
      (footprint "eagle-import:P0603")
      (libsource (lib "eagle-import") (part "R0603"))
    )
    (comp (ref "R133")
      (value "R0805")
      (footprint "eagle-import:P0805")
      (libsource (lib "eagle-import") (part "R0805"))
    )
    (comp (ref "R134")
      (value "62m")
      (footprint "eagle-import:R1206")
      (libsource (lib "eagle-import") (part "R-EU_R1206"))
    )
    (comp (ref "R135")
      (value "0")
      (footprint "eagle-import:P0603")
      (libsource (lib "eagle-import") (part "R0603"))
    )
    (comp (ref "R137")
      (value "0")
      (footprint "eagle-import:P0603")
      (libsource (lib "eagle-import") (part "R0603"))
    )
    (comp (ref "R138")
      (value "301k")
      (footprint "eagle-import:P0603")
      (libsource (lib "eagle-import") (part "R0603"))
    )
    (comp (ref "R139")
      (value "102k")
      (footprint "eagle-import:P0603")
      (libsource (lib "eagle-import") (part "R0603"))
    )
    (comp (ref "SH1")
      (value "SHORT")
      (footprint "eagle-import:SHORT")
      (libsource (lib "eagle-import") (part "SHORT"))
    )
    (comp (ref "SH2")
      (value "SHORT")
      (footprint "eagle-import:SHORT")
      (libsource (lib "eagle-import") (part "SHORT"))
    )
    (comp (ref "U53")
      (value "BQ24650_RVA_16")
      (footprint "eagle-import:RVA16_2P14X2P14")
      (fields
        (field (name "GENERIC_PART_NUMBER") "BQ24650")
        (field (name "MANUFACTURER") "Texas Instruments")
      )
      (libsource (lib "eagle-import") (part "BQ24650_RVA_16"))
    )
    (comp (ref "C104")
      (value "10n")
      (footprint "eagle-import:C0603")
      (libsource (lib "eagle-import") (part "C-EUC0603"))
    )
    (comp (ref "C105")
      (value "100n")
      (footprint "eagle-import:C0603")
      (libsource (lib "eagle-import") (part "C-EUC0603"))
    )
    (comp (ref "C106")
      (value "10u")
      (footprint "eagle-import:C1206")
      (libsource (lib "eagle-import") (part "C-EUC1206"))
    )
    (comp (ref "C107")
      (value "0.1u")
      (footprint "eagle-import:C0603")
      (libsource (lib "eagle-import") (part "C-EUC0603"))
    )
    (comp (ref "C108")
      (value "3.3n")
      (footprint "eagle-import:C0603")
      (libsource (lib "eagle-import") (part "C-EUC0603"))
    )
    (comp (ref "C109")
      (value "22u")
      (footprint "eagle-import:C1210")
      (libsource (lib "eagle-import") (part "C-EUC1210"))
    )
    (comp (ref "C110")
      (value "10n")
      (footprint "eagle-import:C0603")
      (libsource (lib "eagle-import") (part "C-EUC0603"))
    )
    (comp (ref "L2")
      (value "2.2u")
      (footprint "eagle-import:VISHAY-INDUCTOR")
      (libsource (lib "eagle-import") (part "VISHAY-INDUCTOR"))
    )
    (comp (ref "R102")
      (value "20k")
      (footprint "eagle-import:R0603")
      (libsource (lib "eagle-import") (part "R-EU_R0603"))
    )
    (comp (ref "R103")
      (value "10.2k")
      (footprint "eagle-import:R0603")
      (libsource (lib "eagle-import") (part "R-EU_R0603"))
    )
    (comp (ref "R104")
      (value "12.4k")
      (footprint "eagle-import:R0603")
      (libsource (lib "eagle-import") (part "R-EU_R0603"))
    )
    (comp (ref "R105")
      (value "124k")
      (footprint "eagle-import:R0603")
      (libsource (lib "eagle-import") (part "R-EU_R0603"))
    )
    (comp (ref "R106")
      (value "100k")
      (footprint "eagle-import:R0603")
      (libsource (lib "eagle-import") (part "R-EU_R0603"))
    )
    (comp (ref "R107")
      (value "100k")
      (footprint "eagle-import:R0603")
      (libsource (lib "eagle-import") (part "R-EU_R0603"))
    )
    (comp (ref "R108")
      (value "0")
      (footprint "eagle-import:R0603")
      (libsource (lib "eagle-import") (part "R-EU_R0603"))
    )
    (comp (ref "R141")
      (value "4.02k")
      (footprint "eagle-import:R0603")
      (libsource (lib "eagle-import") (part "R-EU_R0603"))
    )
    (comp (ref "TP14")
      (value "PTR1TP09R")
      (footprint "eagle-import:TP09R")
      (libsource (lib "eagle-import") (part "PTR1TP09R"))
    )
    (comp (ref "TP20")
      (value "PTR1TP09R")
      (footprint "eagle-import:TP09R")
      (libsource (lib "eagle-import") (part "PTR1TP09R"))
    )
    (comp (ref "U46")
      (value "TLV3491AIDBV")
      (footprint "eagle-import:SOT23-5")
      (libsource (lib "eagle-import") (part "TLV3491AIDBV"))
    )
    (comp (ref "U47")
      (value "TPS62133RGT")
      (footprint "eagle-import:RGT.16")
      (libsource (lib "eagle-import") (part "TPS62133RGT"))
    )
    (comp (ref "U48")
      (value "FDS8858CZ")
      (footprint "eagle-import:SO8")
      (libsource (lib "eagle-import") (part "FDS8858CZ"))
    )
    (comp (ref "FID1")
      (value "FIDUCIAL1X2-STOP")
      (footprint "eagle-import:FIDUCIAL-1X2-STOP")
      (libsource (lib "eagle-import") (part "FIDUCIAL1X2-STOP"))
    )
    (comp (ref "FID2")
      (value "FIDUCIAL1X2-STOP")
      (footprint "eagle-import:FIDUCIAL-1X2-STOP")
      (libsource (lib "eagle-import") (part "FIDUCIAL1X2-STOP"))
    )
    (comp (ref "FID3")
      (value "FIDUCIAL1X2-STOP")
      (footprint "eagle-import:FIDUCIAL-1X2-STOP")
      (libsource (lib "eagle-import") (part "FIDUCIAL1X2-STOP"))
    )
    (comp (ref "FID4")
      (value "FIDUCIAL1X2-STOP")
      (footprint "eagle-import:FIDUCIAL-1X2-STOP")
      (libsource (lib "eagle-import") (part "FIDUCIAL1X2-STOP"))
    )
    (comp (ref "J1")
      (value "H1")
      (footprint "eagle-import:FE26-2")
      (libsource (lib "eagle-import") (part "FE26-2"))
    )
    (comp (ref "J2")
      (value "H2")
      (footprint "eagle-import:FE26-2")
      (libsource (lib "eagle-import") (part "FE26-2"))
    )
    (comp (ref "J6")
      (value "DF13-8P-1.25DS")
      (footprint "eagle-import:DF13-8P-1.25DS")
      (libsource (lib "eagle-import") (part "DF13-8P-1.25DS"))
    )
    (comp (ref "J7")
      (value "DF13-10P-1.25DS")
      (footprint "eagle-import:DF13-10P-1.25DS")
      (libsource (lib "eagle-import") (part "DF13-10P-1.25DS"))
    )
    (comp (ref "J8")
      (value "DF13-4P-1.25DS")
      (footprint "eagle-import:DF13-4P-1.25DS")
      (libsource (lib "eagle-import") (part "DF13-4P-1.25DS"))
    )
    (comp (ref "J9")
      (value "DF13-4P-1.25DS")
      (footprint "eagle-import:DF13-4P-1.25DS")
      (libsource (lib "eagle-import") (part "DF13-4P-1.25DS"))
    )
    (comp (ref "TP15")
      (value "PTR1TP09R")
      (footprint "eagle-import:TP09R")
      (libsource (lib "eagle-import") (part "PTR1TP09R"))
    )
    (comp (ref "TP16")
      (value "PTR1TP09R")
      (footprint "eagle-import:TP09R")
      (libsource (lib "eagle-import") (part "PTR1TP09R"))
    )
    (comp (ref "C65")
      (value "100n")
      (footprint "eagle-import:C0603")
      (libsource (lib "eagle-import") (part "C-EUC0603"))
    )
    (comp (ref "C66")
      (value "100n")
      (footprint "eagle-import:C0603")
      (libsource (lib "eagle-import") (part "C-EUC0603"))
    )
    (comp (ref "C67")
      (value "100n")
      (footprint "eagle-import:C0603")
      (libsource (lib "eagle-import") (part "C-EUC0603"))
    )
    (comp (ref "C68")
      (value "1n")
      (footprint "eagle-import:C0603")
      (libsource (lib "eagle-import") (part "C-EUC0603"))
    )
    (comp (ref "C69")
      (value "1u")
      (footprint "eagle-import:C0603")
      (libsource (lib "eagle-import") (part "C-EUC0603"))
    )
    (comp (ref "C70")
      (value "100n")
      (footprint "eagle-import:C0603")
      (libsource (lib "eagle-import") (part "C-EUC0603"))
    )
    (comp (ref "C71")
      (value "1u")
      (footprint "eagle-import:C0603")
      (libsource (lib "eagle-import") (part "C-EUC0603"))
    )
    (comp (ref "C72")
      (value "1n")
      (footprint "eagle-import:C0603")
      (libsource (lib "eagle-import") (part "C-EUC0603"))
    )
    (comp (ref "C73")
      (value "22u")
      (footprint "eagle-import:C1210")
      (libsource (lib "eagle-import") (part "C-EUC1210"))
    )
    (comp (ref "C74")
      (value "100n")
      (footprint "eagle-import:C0603")
      (libsource (lib "eagle-import") (part "C-EUC0603"))
    )
    (comp (ref "C75")
      (value "510p")
      (footprint "eagle-import:C0603")
      (libsource (lib "eagle-import") (part "C-EUC0603"))
    )
    (comp (ref "D4")
      (value "PMEG2005AEA")
      (footprint "eagle-import:SOD-323")
      (libsource (lib "eagle-import") (part "PMEG2005AEA"))
    )
    (comp (ref "R66")
      (value "442m")
      (footprint "eagle-import:R1206")
      (libsource (lib "eagle-import") (part "R-EU_R1206"))
    )
    (comp (ref "R67")
      (value "100k")
      (footprint "eagle-import:R0603")
      (libsource (lib "eagle-import") (part "R-EU_R0603"))
    )
    (comp (ref "R68")
      (value "1k")
      (footprint "eagle-import:R0603")
      (libsource (lib "eagle-import") (part "R-EU_R0603"))
    )
    (comp (ref "R69")
      (value "10k")
      (footprint "eagle-import:R0603")
      (libsource (lib "eagle-import") (part "R-EU_R0603"))
    )
    (comp (ref "R70")
      (value "499k")
      (footprint "eagle-import:R0603")
      (libsource (lib "eagle-import") (part "R-EU_R0603"))
    )
    (comp (ref "R71")
      (value "100k")
      (footprint "eagle-import:R0603")
      (libsource (lib "eagle-import") (part "R-EU_R0603"))
    )
    (comp (ref "R72")
      (value "0")
      (footprint "eagle-import:R0603")
      (libsource (lib "eagle-import") (part "R-EU_R0603"))
    )
    (comp (ref "R73")
      (value "309k")
      (footprint "eagle-import:R0603")
      (libsource (lib "eagle-import") (part "R-EU_R0603"))
    )
    (comp (ref "R74")
      (value "100k")
      (footprint "eagle-import:R0603")
      (libsource (lib "eagle-import") (part "R-EU_R0603"))
    )
    (comp (ref "TP5")
      (value "PTR1TP09R")
      (footprint "eagle-import:TP09R")
      (libsource (lib "eagle-import") (part "PTR1TP09R"))
    )
    (comp (ref "TP6")
      (value "PTR1TP09R")
      (footprint "eagle-import:TP09R")
      (libsource (lib "eagle-import") (part "PTR1TP09R"))
    )
    (comp (ref "TP24")
      (value "PTR1TP09R")
      (footprint "eagle-import:TP09R")
      (libsource (lib "eagle-import") (part "PTR1TP09R"))
    )
    (comp (ref "U28")
      (value "MCP6561T-E/LT")
      (footprint "eagle-import:SOT23-5")
      (libsource (lib "eagle-import") (part "MCP6561T-E/LT"))
    )
    (comp (ref "U29")
      (value "INA214DCK")
      (footprint "eagle-import:SC70-6")
      (libsource (lib "eagle-import") (part "INA214DCK"))
    )
    (comp (ref "U30")
      (value "SN74AUP1G00DCK")
      (footprint "eagle-import:SC70-5")
      (libsource (lib "eagle-import") (part "SN74AUP1G00DCK"))
    )
    (comp (ref "U31")
      (value "SN74LVC1G373DCK")
      (footprint "eagle-import:SC70-6")
      (libsource (lib "eagle-import") (part "SN74LVC1G373DCK"))
    )
    (comp (ref "U32")
      (value "NTHD4508NT1")
      (footprint "eagle-import:CHIPFET-1206A-S2")
      (libsource (lib "eagle-import") (part "NTHD4508NT1"))
    )
    (comp (ref "C76")
      (value "100n")
      (footprint "eagle-import:C0603")
      (libsource (lib "eagle-import") (part "C-EUC0603"))
    )
    (comp (ref "C77")
      (value "100n")
      (footprint "eagle-import:C0603")
      (libsource (lib "eagle-import") (part "C-EUC0603"))
    )
    (comp (ref "C78")
      (value "100n")
      (footprint "eagle-import:C0603")
      (libsource (lib "eagle-import") (part "C-EUC0603"))
    )
    (comp (ref "C79")
      (value "470n")
      (footprint "eagle-import:C0603")
      (libsource (lib "eagle-import") (part "C-EUC0603"))
    )
    (comp (ref "C80")
      (value "1u")
      (footprint "eagle-import:C0603")
      (libsource (lib "eagle-import") (part "C-EUC0603"))
    )
    (comp (ref "C81")
      (value "100n")
      (footprint "eagle-import:C0603")
      (libsource (lib "eagle-import") (part "C-EUC0603"))
    )
    (comp (ref "C82")
      (value "1u")
      (footprint "eagle-import:C0603")
      (libsource (lib "eagle-import") (part "C-EUC0603"))
    )
    (comp (ref "C83")
      (value "1n")
      (footprint "eagle-import:C0603")
      (libsource (lib "eagle-import") (part "C-EUC0603"))
    )
    (comp (ref "C84")
      (value "22u")
      (footprint "eagle-import:C1210")
      (libsource (lib "eagle-import") (part "C-EUC1210"))
    )
    (comp (ref "C85")
      (value "100n")
      (footprint "eagle-import:C0603")
      (libsource (lib "eagle-import") (part "C-EUC0603"))
    )
    (comp (ref "C86")
      (value "510p")
      (footprint "eagle-import:C0603")
      (libsource (lib "eagle-import") (part "C-EUC0603"))
    )
    (comp (ref "D5")
      (value "PMEG2005AEA")
      (footprint "eagle-import:SOD-323")
      (libsource (lib "eagle-import") (part "PMEG2005AEA"))
    )
    (comp (ref "R75")
      (value "50m")
      (footprint "eagle-import:R1206")
      (libsource (lib "eagle-import") (part "R-EU_R1206"))
    )
    (comp (ref "R76")
      (value "100k")
      (footprint "eagle-import:R0603")
      (libsource (lib "eagle-import") (part "R-EU_R0603"))
    )
    (comp (ref "R77")
      (value "1k")
      (footprint "eagle-import:R0603")
      (libsource (lib "eagle-import") (part "R-EU_R0603"))
    )
    (comp (ref "R78")
      (value "10k")
      (footprint "eagle-import:R0603")
      (libsource (lib "eagle-import") (part "R-EU_R0603"))
    )
    (comp (ref "R79")
      (value "499k")
      (footprint "eagle-import:R0603")
      (libsource (lib "eagle-import") (part "R-EU_R0603"))
    )
    (comp (ref "R80")
      (value "100k")
      (footprint "eagle-import:R0603")
      (libsource (lib "eagle-import") (part "R-EU_R0603"))
    )
    (comp (ref "R81")
      (value "0")
      (footprint "eagle-import:R0603")
      (libsource (lib "eagle-import") (part "R-EU_R0603"))
    )
    (comp (ref "R82")
      (value "309k")
      (footprint "eagle-import:R0603")
      (libsource (lib "eagle-import") (part "R-EU_R0603"))
    )
    (comp (ref "R83")
      (value "100k")
      (footprint "eagle-import:R0603")
      (libsource (lib "eagle-import") (part "R-EU_R0603"))
    )
    (comp (ref "TP3")
      (value "PTR1TP09R")
      (footprint "eagle-import:TP09R")
      (libsource (lib "eagle-import") (part "PTR1TP09R"))
    )
    (comp (ref "TP4")
      (value "PTR1TP09R")
      (footprint "eagle-import:TP09R")
      (libsource (lib "eagle-import") (part "PTR1TP09R"))
    )
    (comp (ref "TP23")
      (value "PTR1TP09R")
      (footprint "eagle-import:TP09R")
      (libsource (lib "eagle-import") (part "PTR1TP09R"))
    )
    (comp (ref "U33")
      (value "MCP6561T-E/LT")
      (footprint "eagle-import:SOT23-5")
      (libsource (lib "eagle-import") (part "MCP6561T-E/LT"))
    )
    (comp (ref "U34")
      (value "INA214DCK")
      (footprint "eagle-import:SC70-6")
      (libsource (lib "eagle-import") (part "INA214DCK"))
    )
    (comp (ref "U35")
      (value "SN74AUP1G00DCK")
      (footprint "eagle-import:SC70-5")
      (libsource (lib "eagle-import") (part "SN74AUP1G00DCK"))
    )
    (comp (ref "U36")
      (value "SN74LVC1G373DCK")
      (footprint "eagle-import:SC70-6")
      (libsource (lib "eagle-import") (part "SN74LVC1G373DCK"))
    )
    (comp (ref "U37")
      (value "NTHD4508NT1")
      (footprint "eagle-import:CHIPFET-1206A-S2")
      (libsource (lib "eagle-import") (part "NTHD4508NT1"))
    )
    (comp (ref "C15")
      (value "100n")
      (footprint "eagle-import:C0603")
      (libsource (lib "eagle-import") (part "C-EUC0603"))
    )
    (comp (ref "C16")
      (value "100n")
      (footprint "eagle-import:C0603")
      (libsource (lib "eagle-import") (part "C-EUC0603"))
    )
    (comp (ref "C17")
      (value "1u")
      (footprint "eagle-import:C0603")
      (libsource (lib "eagle-import") (part "C-EUC0603"))
    )
    (comp (ref "C18")
      (value "1u")
      (footprint "eagle-import:C0603")
      (libsource (lib "eagle-import") (part "C-EUC0603"))
    )
    (comp (ref "C19")
      (value "100n")
      (footprint "eagle-import:C0603")
      (libsource (lib "eagle-import") (part "C-EUC0603"))
    )
    (comp (ref "C20")
      (value "100n")
      (footprint "eagle-import:C0603")
      (libsource (lib "eagle-import") (part "C-EUC0603"))
    )
    (comp (ref "C21")
      (value "1u")
      (footprint "eagle-import:C0603")
      (libsource (lib "eagle-import") (part "C-EUC0603"))
    )
    (comp (ref "C22")
      (value "1u")
      (footprint "eagle-import:C0603")
      (libsource (lib "eagle-import") (part "C-EUC0603"))
    )
    (comp (ref "R15")
      (value "43m")
      (footprint "eagle-import:R1206")
      (libsource (lib "eagle-import") (part "R-EU_R1206"))
    )
    (comp (ref "R16")
      (value "43m")
      (footprint "eagle-import:R1206")
      (libsource (lib "eagle-import") (part "R-EU_R1206"))
    )
    (comp (ref "R17")
      (value "10k")
      (footprint "eagle-import:R0603")
      (libsource (lib "eagle-import") (part "R-EU_R0603"))
    )
    (comp (ref "R18")
      (value "10k")
      (footprint "eagle-import:R0603")
      (libsource (lib "eagle-import") (part "R-EU_R0603"))
    )
    (comp (ref "R19")
      (value "43m")
      (footprint "eagle-import:R1206")
      (libsource (lib "eagle-import") (part "R-EU_R1206"))
    )
    (comp (ref "R20")
      (value "43m")
      (footprint "eagle-import:R1206")
      (libsource (lib "eagle-import") (part "R-EU_R1206"))
    )
    (comp (ref "R21")
      (value "10k")
      (footprint "eagle-import:R0603")
      (libsource (lib "eagle-import") (part "R-EU_R0603"))
    )
    (comp (ref "R22")
      (value "10k")
      (footprint "eagle-import:R0603")
      (libsource (lib "eagle-import") (part "R-EU_R0603"))
    )
    (comp (ref "U8")
      (value "INA214DCK")
      (footprint "eagle-import:SC70-6")
      (libsource (lib "eagle-import") (part "INA214DCK"))
    )
    (comp (ref "U9")
      (value "INA214DCK")
      (footprint "eagle-import:SC70-6")
      (libsource (lib "eagle-import") (part "INA214DCK"))
    )
    (comp (ref "U10")
      (value "INA214DCK")
      (footprint "eagle-import:SC70-6")
      (libsource (lib "eagle-import") (part "INA214DCK"))
    )
    (comp (ref "U11")
      (value "INA214DCK")
      (footprint "eagle-import:SC70-6")
      (libsource (lib "eagle-import") (part "INA214DCK"))
    )
    (comp (ref "C87")
      (value "100n")
      (footprint "eagle-import:C0603")
      (libsource (lib "eagle-import") (part "C-EUC0603"))
    )
    (comp (ref "C88")
      (value "100n")
      (footprint "eagle-import:C0603")
      (libsource (lib "eagle-import") (part "C-EUC0603"))
    )
    (comp (ref "C89")
      (value "100n")
      (footprint "eagle-import:C0603")
      (libsource (lib "eagle-import") (part "C-EUC0603"))
    )
    (comp (ref "C90")
      (value "1n")
      (footprint "eagle-import:C0603")
      (libsource (lib "eagle-import") (part "C-EUC0603"))
    )
    (comp (ref "C91")
      (value "1u")
      (footprint "eagle-import:C0603")
      (libsource (lib "eagle-import") (part "C-EUC0603"))
    )
    (comp (ref "C92")
      (value "100n")
      (footprint "eagle-import:C0603")
      (libsource (lib "eagle-import") (part "C-EUC0603"))
    )
    (comp (ref "C93")
      (value "1u")
      (footprint "eagle-import:C0603")
      (libsource (lib "eagle-import") (part "C-EUC0603"))
    )
    (comp (ref "C94")
      (value "100n")
      (footprint "eagle-import:C0603")
      (libsource (lib "eagle-import") (part "C-EUC0603"))
    )
    (comp (ref "C95")
      (value "22u")
      (footprint "eagle-import:C1210")
      (libsource (lib "eagle-import") (part "C-EUC1210"))
    )
    (comp (ref "D6")
      (value "PMEG2005AEA")
      (footprint "eagle-import:SOD-323")
      (libsource (lib "eagle-import") (part "PMEG2005AEA"))
    )
    (comp (ref "R84")
      (value "124m")
      (footprint "eagle-import:R1206")
      (libsource (lib "eagle-import") (part "R-EU_R1206"))
    )
    (comp (ref "R85")
      (value "100k")
      (footprint "eagle-import:R0603")
      (libsource (lib "eagle-import") (part "R-EU_R0603"))
    )
    (comp (ref "R86")
      (value "1k")
      (footprint "eagle-import:R0603")
      (libsource (lib "eagle-import") (part "R-EU_R0603"))
    )
    (comp (ref "R87")
      (value "10k")
      (footprint "eagle-import:R0603")
      (libsource (lib "eagle-import") (part "R-EU_R0603"))
    )
    (comp (ref "R88")
      (value "499k")
      (footprint "eagle-import:R0603")
      (libsource (lib "eagle-import") (part "R-EU_R0603"))
    )
    (comp (ref "R89")
      (value "499")
      (footprint "eagle-import:R0603")
      (libsource (lib "eagle-import") (part "R-EU_R0603"))
    )
    (comp (ref "R90")
      (value "0")
      (footprint "eagle-import:R0603")
      (libsource (lib "eagle-import") (part "R-EU_R0603"))
    )
    (comp (ref "R91")
      (value "309k")
      (footprint "eagle-import:R0603")
      (libsource (lib "eagle-import") (part "R-EU_R0603"))
    )
    (comp (ref "R92")
      (value "100k")
      (footprint "eagle-import:R0603")
      (libsource (lib "eagle-import") (part "R-EU_R0603"))
    )
    (comp (ref "TP1")
      (value "PTR1TP09R")
      (footprint "eagle-import:TP09R")
      (libsource (lib "eagle-import") (part "PTR1TP09R"))
    )
    (comp (ref "TP2")
      (value "PTR1TP09R")
      (footprint "eagle-import:TP09R")
      (libsource (lib "eagle-import") (part "PTR1TP09R"))
    )
    (comp (ref "TP22")
      (value "PTR1TP09R")
      (footprint "eagle-import:TP09R")
      (libsource (lib "eagle-import") (part "PTR1TP09R"))
    )
    (comp (ref "U38")
      (value "MCP6561T-E/LT")
      (footprint "eagle-import:SOT23-5")
      (libsource (lib "eagle-import") (part "MCP6561T-E/LT"))
    )
    (comp (ref "U39")
      (value "INA214DCK")
      (footprint "eagle-import:SC70-6")
      (libsource (lib "eagle-import") (part "INA214DCK"))
    )
    (comp (ref "U40")
      (value "SN74AUP1T08DCK")
      (footprint "eagle-import:SC70-5")
      (libsource (lib "eagle-import") (part "SN74AUP1T08DCK"))
    )
    (comp (ref "U41")
      (value "SN74LVC1G373DCK")
      (footprint "eagle-import:SC70-6")
      (libsource (lib "eagle-import") (part "SN74LVC1G373DCK"))
    )
    (comp (ref "U42")
      (value "FDS8858CZ")
      (footprint "eagle-import:SO8")
      (libsource (lib "eagle-import") (part "FDS8858CZ"))
    )
    (comp (ref "C111")
      (value "0.1u")
      (footprint "eagle-import:C0603K")
      (libsource (lib "eagle-import") (part "C-EUC0603K"))
    )
    (comp (ref "C112")
      (value "1n")
      (footprint "eagle-import:C0603K")
      (libsource (lib "eagle-import") (part "C-EUC0603K"))
    )
    (comp (ref "C113")
      (value "0.1u")
      (footprint "eagle-import:C0603K")
      (libsource (lib "eagle-import") (part "C-EUC0603K"))
    )
    (comp (ref "R29")
      (value "4k7")
      (footprint "eagle-import:R0603")
      (libsource (lib "eagle-import") (part "R-EU_R0603"))
    )
    (comp (ref "R30")
      (value "4k7")
      (footprint "eagle-import:R0603")
      (libsource (lib "eagle-import") (part "R-EU_R0603"))
    )
    (comp (ref "R109")
      (value "47k")
      (footprint "eagle-import:R0603")
      (libsource (lib "eagle-import") (part "R-EU_R0603"))
    )
    (comp (ref "U49")
      (value "MSP430F2132")
      (footprint "eagle-import:RHB32")
      (libsource (lib "eagle-import") (part "F21X2---RHB32"))
    )
    (comp (ref "U50")
      (value "ADG732")
      (footprint "eagle-import:LFCSP48")
      (libsource (lib "eagle-import") (part "ADG732"))
    )
    (comp (ref "X1")
      (value "32.768k")
      (footprint "eagle-import:CC7V-T1A")
      (libsource (lib "eagle-import") (part "XTAL-CC7V-T1A"))
    )
    (comp (ref "C1")
      (value "100n")
      (footprint "eagle-import:C0603")
      (libsource (lib "eagle-import") (part "C-EUC0603"))
    )
    (comp (ref "C2")
      (value "100n")
      (footprint "eagle-import:C0603")
      (libsource (lib "eagle-import") (part "C-EUC0603"))
    )
    (comp (ref "C3")
      (value "1u")
      (footprint "eagle-import:C0603")
      (libsource (lib "eagle-import") (part "C-EUC0603"))
    )
    (comp (ref "C4")
      (value "1u")
      (footprint "eagle-import:C0603")
      (libsource (lib "eagle-import") (part "C-EUC0603"))
    )
    (comp (ref "C136")
      (value "100n")
      (footprint "eagle-import:C0603")
      (libsource (lib "eagle-import") (part "C-EUC0603"))
    )
    (comp (ref "C138")
      (value "1u")
      (footprint "eagle-import:C0603")
      (libsource (lib "eagle-import") (part "C-EUC0603"))
    )
    (comp (ref "R1")
      (value "250m")
      (footprint "eagle-import:R1206")
      (libsource (lib "eagle-import") (part "R-EU_R1206"))
    )
    (comp (ref "R2")
      (value "124m")
      (footprint "eagle-import:R1206")
      (libsource (lib "eagle-import") (part "R-EU_R1206"))
    )
    (comp (ref "R3")
      (value "10k")
      (footprint "eagle-import:R0603")
      (libsource (lib "eagle-import") (part "R-EU_R0603"))
    )
    (comp (ref "R4")
      (value "10k")
      (footprint "eagle-import:R0603")
      (libsource (lib "eagle-import") (part "R-EU_R0603"))
    )
    (comp (ref "R132")
      (value "250m")
      (footprint "eagle-import:R1206")
      (libsource (lib "eagle-import") (part "R-EU_R1206"))
    )
    (comp (ref "R136")
      (value "10k")
      (footprint "eagle-import:R0603")
      (libsource (lib "eagle-import") (part "R-EU_R0603"))
    )
    (comp (ref "U1")
      (value "INA214DCK")
      (footprint "eagle-import:SC70-6")
      (libsource (lib "eagle-import") (part "INA214DCK"))
    )
    (comp (ref "U2")
      (value "INA214DCK")
      (footprint "eagle-import:SC70-6")
      (libsource (lib "eagle-import") (part "INA214DCK"))
    )
    (comp (ref "U54")
      (value "INA214DCK")
      (footprint "eagle-import:SC70-6")
      (libsource (lib "eagle-import") (part "INA214DCK"))
    )
    (comp (ref "C13")
      (value "100n")
      (footprint "eagle-import:C0603")
      (libsource (lib "eagle-import") (part "C-EUC0603"))
    )
    (comp (ref "C14")
      (value "1u")
      (footprint "eagle-import:C0603")
      (libsource (lib "eagle-import") (part "C-EUC0603"))
    )
    (comp (ref "C23")
      (value "100n")
      (footprint "eagle-import:C0603")
      (libsource (lib "eagle-import") (part "C-EUC0603"))
    )
    (comp (ref "C24")
      (value "1u")
      (footprint "eagle-import:C0603")
      (libsource (lib "eagle-import") (part "C-EUC0603"))
    )
    (comp (ref "C96")
      (value "1u")
      (footprint "eagle-import:C0603")
      (libsource (lib "eagle-import") (part "C-EUC0603"))
    )
    (comp (ref "R13")
      (value "43m")
      (footprint "eagle-import:R1206")
      (libsource (lib "eagle-import") (part "R-EU_R1206"))
    )
    (comp (ref "R14")
      (value "10k")
      (footprint "eagle-import:R0603")
      (libsource (lib "eagle-import") (part "R-EU_R0603"))
    )
    (comp (ref "R23")
      (value "43m")
      (footprint "eagle-import:R1206")
      (libsource (lib "eagle-import") (part "R-EU_R1206"))
    )
    (comp (ref "R24")
      (value "10k")
      (footprint "eagle-import:R0603")
      (libsource (lib "eagle-import") (part "R-EU_R0603"))
    )
    (comp (ref "R93")
      (value "22.6k")
      (footprint "eagle-import:R0603")
      (libsource (lib "eagle-import") (part "R-EU_R0603"))
    )
    (comp (ref "R94")
      (value "75k")
      (footprint "eagle-import:R0603")
      (libsource (lib "eagle-import") (part "R-EU_R0603"))
    )
    (comp (ref "U7")
      (value "INA214DCK")
      (footprint "eagle-import:SC70-6")
      (libsource (lib "eagle-import") (part "INA214DCK"))
    )
    (comp (ref "U12")
      (value "INA214DCK")
      (footprint "eagle-import:SC70-6")
      (libsource (lib "eagle-import") (part "INA214DCK"))
    )
    (comp (ref "C5")
      (value "100n")
      (footprint "eagle-import:C0603")
      (libsource (lib "eagle-import") (part "C-EUC0603"))
    )
    (comp (ref "C6")
      (value "100n")
      (footprint "eagle-import:C0603")
      (libsource (lib "eagle-import") (part "C-EUC0603"))
    )
    (comp (ref "C7")
      (value "1u")
      (footprint "eagle-import:C0603")
      (libsource (lib "eagle-import") (part "C-EUC0603"))
    )
    (comp (ref "C8")
      (value "1u")
      (footprint "eagle-import:C0603")
      (libsource (lib "eagle-import") (part "C-EUC0603"))
    )
    (comp (ref "C9")
      (value "100n")
      (footprint "eagle-import:C0603")
      (libsource (lib "eagle-import") (part "C-EUC0603"))
    )
    (comp (ref "C10")
      (value "100n")
      (footprint "eagle-import:C0603")
      (libsource (lib "eagle-import") (part "C-EUC0603"))
    )
    (comp (ref "C11")
      (value "1u")
      (footprint "eagle-import:C0603")
      (libsource (lib "eagle-import") (part "C-EUC0603"))
    )
    (comp (ref "C12")
      (value "1u")
      (footprint "eagle-import:C0603")
      (libsource (lib "eagle-import") (part "C-EUC0603"))
    )
    (comp (ref "R5")
      (value "43m")
      (footprint "eagle-import:R1206")
      (libsource (lib "eagle-import") (part "R-EU_R1206"))
    )
    (comp (ref "R6")
      (value "43m")
      (footprint "eagle-import:R1206")
      (libsource (lib "eagle-import") (part "R-EU_R1206"))
    )
    (comp (ref "R7")
      (value "10k")
      (footprint "eagle-import:R0603")
      (libsource (lib "eagle-import") (part "R-EU_R0603"))
    )
    (comp (ref "R8")
      (value "10k")
      (footprint "eagle-import:R0603")
      (libsource (lib "eagle-import") (part "R-EU_R0603"))
    )
    (comp (ref "R9")
      (value "43m")
      (footprint "eagle-import:R1206")
      (libsource (lib "eagle-import") (part "R-EU_R1206"))
    )
    (comp (ref "R10")
      (value "43m")
      (footprint "eagle-import:R1206")
      (libsource (lib "eagle-import") (part "R-EU_R1206"))
    )
    (comp (ref "R11")
      (value "10k")
      (footprint "eagle-import:R0603")
      (libsource (lib "eagle-import") (part "R-EU_R0603"))
    )
    (comp (ref "R12")
      (value "10k")
      (footprint "eagle-import:R0603")
      (libsource (lib "eagle-import") (part "R-EU_R0603"))
    )
    (comp (ref "U3")
      (value "INA214DCK")
      (footprint "eagle-import:SC70-6")
      (libsource (lib "eagle-import") (part "INA214DCK"))
    )
    (comp (ref "U4")
      (value "INA214DCK")
      (footprint "eagle-import:SC70-6")
      (libsource (lib "eagle-import") (part "INA214DCK"))
    )
    (comp (ref "U5")
      (value "INA214DCK")
      (footprint "eagle-import:SC70-6")
      (libsource (lib "eagle-import") (part "INA214DCK"))
    )
    (comp (ref "U6")
      (value "INA214DCK")
      (footprint "eagle-import:SC70-6")
      (libsource (lib "eagle-import") (part "INA214DCK"))
    )
    (comp (ref "C97")
      (value "10n")
      (footprint "eagle-import:C0603")
      (libsource (lib "eagle-import") (part "C-EUC0603"))
    )
    (comp (ref "C98")
      (value "100n")
      (footprint "eagle-import:C0603")
      (libsource (lib "eagle-import") (part "C-EUC0603"))
    )
    (comp (ref "C99")
      (value "10u")
      (footprint "eagle-import:C1206")
      (libsource (lib "eagle-import") (part "C-EUC1206"))
    )
    (comp (ref "C100")
      (value "0.1u")
      (footprint "eagle-import:C0603")
      (libsource (lib "eagle-import") (part "C-EUC0603"))
    )
    (comp (ref "C101")
      (value "3.3n")
      (footprint "eagle-import:C0603")
      (libsource (lib "eagle-import") (part "C-EUC0603"))
    )
    (comp (ref "C102")
      (value "22u")
      (footprint "eagle-import:C1210")
      (libsource (lib "eagle-import") (part "C-EUC1210"))
    )
    (comp (ref "C103")
      (value "10n")
      (footprint "eagle-import:C0603")
      (libsource (lib "eagle-import") (part "C-EUC0603"))
    )
    (comp (ref "L1")
      (value "2.2u")
      (footprint "eagle-import:VISHAY-INDUCTOR")
      (libsource (lib "eagle-import") (part "VISHAY-INDUCTOR"))
    )
    (comp (ref "R95")
      (value "20k")
      (footprint "eagle-import:R0603")
      (libsource (lib "eagle-import") (part "R-EU_R0603"))
    )
    (comp (ref "R96")
      (value "10.2k")
      (footprint "eagle-import:R0603")
      (libsource (lib "eagle-import") (part "R-EU_R0603"))
    )
    (comp (ref "R97")
      (value "12.4k")
      (footprint "eagle-import:R0603")
      (libsource (lib "eagle-import") (part "R-EU_R0603"))
    )
    (comp (ref "R98")
      (value "124k")
      (footprint "eagle-import:R0603")
      (libsource (lib "eagle-import") (part "R-EU_R0603"))
    )
    (comp (ref "R99")
      (value "100k")
      (footprint "eagle-import:R0603")
      (libsource (lib "eagle-import") (part "R-EU_R0603"))
    )
    (comp (ref "R100")
      (value "100k")
      (footprint "eagle-import:R0603")
      (libsource (lib "eagle-import") (part "R-EU_R0603"))
    )
    (comp (ref "R101")
      (value "0")
      (footprint "eagle-import:R0603")
      (libsource (lib "eagle-import") (part "R-EU_R0603"))
    )
    (comp (ref "R140")
      (value "4.02k")
      (footprint "eagle-import:R0603")
      (libsource (lib "eagle-import") (part "R-EU_R0603"))
    )
    (comp (ref "TP13")
      (value "PTR1TP09R")
      (footprint "eagle-import:TP09R")
      (libsource (lib "eagle-import") (part "PTR1TP09R"))
    )
    (comp (ref "TP21")
      (value "PTR1TP09R")
      (footprint "eagle-import:TP09R")
      (libsource (lib "eagle-import") (part "PTR1TP09R"))
    )
    (comp (ref "U43")
      (value "TLV3491AIDBV")
      (footprint "eagle-import:SOT23-5")
      (libsource (lib "eagle-import") (part "TLV3491AIDBV"))
    )
    (comp (ref "U44")
      (value "TPS62132RGT")
      (footprint "eagle-import:RGT.16")
      (libsource (lib "eagle-import") (part "TPS62132RGT"))
    )
    (comp (ref "U45")
      (value "FDS8858CZ")
      (footprint "eagle-import:SO8")
      (libsource (lib "eagle-import") (part "FDS8858CZ"))
    )
    (comp (ref "C25")
      (value "1u")
      (footprint "eagle-import:C0603")
      (libsource (lib "eagle-import") (part "C-EUC0603"))
    )
    (comp (ref "C26")
      (value "1u")
      (footprint "eagle-import:C0603")
      (libsource (lib "eagle-import") (part "C-EUC0603"))
    )
    (comp (ref "C28")
      (value "1u")
      (footprint "eagle-import:C0603")
      (libsource (lib "eagle-import") (part "C-EUC0603"))
    )
    (comp (ref "C29")
      (value "1u")
      (footprint "eagle-import:C0603")
      (libsource (lib "eagle-import") (part "C-EUC0603"))
    )
    (comp (ref "C30")
      (value "1u")
      (footprint "eagle-import:C0603")
      (libsource (lib "eagle-import") (part "C-EUC0603"))
    )
    (comp (ref "C31")
      (value "1u")
      (footprint "eagle-import:C0603")
      (libsource (lib "eagle-import") (part "C-EUC0603"))
    )
    (comp (ref "R25")
      (value "309k")
      (footprint "eagle-import:R0603")
      (libsource (lib "eagle-import") (part "R-EU_R0603"))
    )
    (comp (ref "R26")
      (value "100k")
      (footprint "eagle-import:R0603")
      (libsource (lib "eagle-import") (part "R-EU_R0603"))
    )
    (comp (ref "R27")
      (value "309k")
      (footprint "eagle-import:R0603")
      (libsource (lib "eagle-import") (part "R-EU_R0603"))
    )
    (comp (ref "R28")
      (value "100k")
      (footprint "eagle-import:R0603")
      (libsource (lib "eagle-import") (part "R-EU_R0603"))
    )
    (comp (ref "R31")
      (value "309k")
      (footprint "eagle-import:R0603")
      (libsource (lib "eagle-import") (part "R-EU_R0603"))
    )
    (comp (ref "R32")
      (value "100k")
      (footprint "eagle-import:R0603")
      (libsource (lib "eagle-import") (part "R-EU_R0603"))
    )
    (comp (ref "R33")
      (value "309k")
      (footprint "eagle-import:R0603")
      (libsource (lib "eagle-import") (part "R-EU_R0603"))
    )
    (comp (ref "R34")
      (value "100k")
      (footprint "eagle-import:R0603")
      (libsource (lib "eagle-import") (part "R-EU_R0603"))
    )
    (comp (ref "R35")
      (value "309k")
      (footprint "eagle-import:R0603")
      (libsource (lib "eagle-import") (part "R-EU_R0603"))
    )
    (comp (ref "R36")
      (value "100k")
      (footprint "eagle-import:R0603")
      (libsource (lib "eagle-import") (part "R-EU_R0603"))
    )
    (comp (ref "R37")
      (value "309k")
      (footprint "eagle-import:R0603")
      (libsource (lib "eagle-import") (part "R-EU_R0603"))
    )
    (comp (ref "R38")
      (value "100k")
      (footprint "eagle-import:R0603")
      (libsource (lib "eagle-import") (part "R-EU_R0603"))
    )
    (comp (ref "TP17")
      (value "PTR1TP09R")
      (footprint "eagle-import:TP09R")
      (libsource (lib "eagle-import") (part "PTR1TP09R"))
    )
    (comp (ref "TP18")
      (value "PTR1TP09R")
      (footprint "eagle-import:TP09R")
      (libsource (lib "eagle-import") (part "PTR1TP09R"))
    )
    (comp (ref "TP19")
      (value "PTR1TP09R")
      (footprint "eagle-import:TP09R")
      (libsource (lib "eagle-import") (part "PTR1TP09R"))
    )
  )
  (nets
    (net (code "1") (name "3V3_FLIGHT_MCU") (class "Default")
      (node (ref "C75") (pin "1") (pinfunction "1_1") (pintype "passive"))
      (node (ref "J1") (pin "49") (pinfunction "49_49") (pintype "passive"))
      (node (ref "J7") (pin "P$5") (pinfunction "5_P$5") (pintype "passive"))
      (node (ref "R73") (pin "2") (pinfunction "2_2") (pintype "passive"))
      (node (ref "TP24") (pin "TP") (pinfunction "TP_TP") (pintype "input"))
      (node (ref "U32") (pin "1") (pinfunction "S_1") (pintype "passive"))
    )
    (net (code "2") (name "3V3_SYS") (class "Default")
      (node (ref "J2") (pin "27") (pinfunction "27_27") (pintype "passive"))
      (node (ref "J2") (pin "28") (pinfunction "28_28") (pintype "passive"))
      (node (ref "R1") (pin "2") (pinfunction "2_2") (pintype "passive"))
      (node (ref "TP16") (pin "TP") (pinfunction "TP_TP") (pintype "input"))
      (node (ref "U1") (pin "5") (pinfunction "IN-_5") (pintype "bidirectional"))
    )
    (net (code "3") (name "5V_CAMERA") (class "Default")
      (node (ref "C64") (pin "1") (pinfunction "1_1") (pintype "passive"))
      (node (ref "J1") (pin "50") (pinfunction "50_50") (pintype "passive"))
      (node (ref "R64") (pin "2") (pinfunction "2_2") (pintype "passive"))
      (node (ref "TP25") (pin "TP") (pinfunction "TP_TP") (pintype "input"))
      (node (ref "U27") (pin "1") (pinfunction "S_1") (pintype "passive"))
    )
    (net (code "4") (name "5V_RX_RADIO") (class "Default")
      (node (ref "C53") (pin "1") (pinfunction "1_1") (pintype "passive"))
      (node (ref "J1") (pin "51") (pinfunction "51_51") (pintype "passive"))
      (node (ref "R55") (pin "2") (pinfunction "2_2") (pintype "passive"))
      (node (ref "TP26") (pin "TP") (pinfunction "TP_TP") (pintype "input"))
      (node (ref "U22") (pin "1") (pinfunction "S_1") (pintype "passive"))
    )
    (net (code "5") (name "5V_SYS") (class "Default")
      (node (ref "J2") (pin "25") (pinfunction "25_25") (pintype "passive"))
      (node (ref "J2") (pin "26") (pinfunction "26_26") (pintype "passive"))
      (node (ref "R2") (pin "2") (pinfunction "2_2") (pintype "passive"))
      (node (ref "TP15") (pin "TP") (pinfunction "TP_TP") (pintype "input"))
      (node (ref "U2") (pin "5") (pinfunction "IN-_5") (pintype "bidirectional"))
    )
    (net (code "6") (name "5V_TX_RADIO") (class "Default")
      (node (ref "C42") (pin "1") (pinfunction "1_1") (pintype "passive"))
      (node (ref "J1") (pin "52") (pinfunction "52_52") (pintype "passive"))
      (node (ref "R46") (pin "2") (pinfunction "2_2") (pintype "passive"))
      (node (ref "TP27") (pin "TP") (pinfunction "TP_TP") (pintype "input"))
      (node (ref "U17") (pin "1") (pinfunction "S_1") (pintype "passive"))
    )
    (net (code "7") (name "BATT_I2C_SCL") (class "Default")
      (node (ref "J1") (pin "43") (pinfunction "43_43") (pintype "passive"))
      (node (ref "R30") (pin "1") (pinfunction "1_1") (pintype "passive"))
      (node (ref "U49") (pin "11") (pinfunction "11_11") (pintype "bidirectional"))
    )
    (net (code "8") (name "BATT_I2C_SDA") (class "Default")
      (node (ref "J1") (pin "41") (pinfunction "41_41") (pintype "passive"))
      (node (ref "R29") (pin "1") (pinfunction "1_1") (pintype "passive"))
      (node (ref "U49") (pin "10") (pinfunction "10_10") (pintype "bidirectional"))
    )
    (net (code "9") (name "CHARGE_BATT") (class "Default")
      (node (ref "C142") (pin "1") (pinfunction "1_1") (pintype "passive"))
      (node (ref "J2") (pin "41") (pinfunction "41_41") (pintype "passive"))
      (node (ref "J2") (pin "42") (pinfunction "42_42") (pintype "passive"))
      (node (ref "J2") (pin "43") (pinfunction "43_43") (pintype "passive"))
      (node (ref "J2") (pin "44") (pinfunction "44_44") (pintype "passive"))
      (node (ref "R132") (pin "2") (pinfunction "2_2") (pintype "passive"))
      (node (ref "R137") (pin "2") (pinfunction "2_2") (pintype "passive"))
      (node (ref "U54") (pin "5") (pinfunction "IN-_5") (pintype "bidirectional"))
    )
    (net (code "10") (name "CHARGE_CSENSE_MUX") (class "Default")
      (node (ref "C138") (pin "1") (pinfunction "1_1") (pintype "passive"))
      (node (ref "R136") (pin "1") (pinfunction "1_1") (pintype "passive"))
      (node (ref "U50") (pin "27") (pinfunction "S19_27") (pintype "bidirectional"))
    )
    (net (code "11") (name "CHARGE_IN") (class "Default")
      (node (ref "C122") (pin "1") (pinfunction "1_1") (pintype "passive"))
      (node (ref "C128") (pin "1") (pinfunction "1_1") (pintype "passive"))
      (node (ref "C145") (pin "1") (pinfunction "1_1") (pintype "passive"))
      (node (ref "C155") (pin "1") (pinfunction "1_1") (pintype "passive"))
      (node (ref "D9") (pin "LEFT") (pinfunction "A1_LEFT") (pintype "passive"))
      (node (ref "D9") (pin "RIGHT") (pinfunction "A2_RIGHT") (pintype "passive"))
      (node (ref "J7") (pin "P$3") (pinfunction "3_P$3") (pintype "passive"))
      (node (ref "R113") (pin "1") (pinfunction "1_1") (pintype "passive"))
      (node (ref "R116") (pin "1") (pinfunction "1_1") (pintype "passive"))
      (node (ref "R119") (pin "1") (pinfunction "1_1") (pintype "passive"))
      (node (ref "R120") (pin "2") (pinfunction "2_2") (pintype "passive"))
      (node (ref "R121") (pin "2") (pinfunction "2_2") (pintype "passive"))
      (node (ref "R129") (pin "2") (pinfunction "2_2") (pintype "passive"))
      (node (ref "R142") (pin "1") (pinfunction "1_1") (pintype "passive"))
      (node (ref "R149") (pin "1") (pinfunction "1_1") (pintype "passive"))
      (node (ref "R150") (pin "1") (pinfunction "1_1") (pintype "passive"))
      (node (ref "R31") (pin "2") (pinfunction "2_2") (pintype "passive"))
      (node (ref "TP31") (pin "TP") (pinfunction "TP_TP") (pintype "input"))
    )
    (net (code "12") (name "CHARGE_OUT") (class "Default")
      (node (ref "C137") (pin "1") (pinfunction "1_1") (pintype "passive"))
      (node (ref "C139") (pin "1") (pinfunction "1_1") (pintype "passive"))
      (node (ref "D11") (pin "LEFT") (pinfunction "A1_LEFT") (pintype "passive"))
      (node (ref "D11") (pin "RIGHT") (pinfunction "A2_RIGHT") (pintype "passive"))
      (node (ref "R132") (pin "1") (pinfunction "1_1") (pintype "passive"))
      (node (ref "R134") (pin "2") (pinfunction "2_2") (pintype "passive"))
      (node (ref "R135") (pin "2") (pinfunction "2_2") (pintype "passive"))
      (node (ref "U54") (pin "4") (pinfunction "IN+_4") (pintype "bidirectional"))
    )
    (net (code "13") (name "FLIGHT_MCU_N_RST") (class "Default")
      (node (ref "J2") (pin "4") (pinfunction "4_4") (pintype "passive"))
      (node (ref "J7") (pin "P$7") (pinfunction "7_P$7") (pintype "passive"))
    )
    (net (code "14") (name "FLIGHT_MCU_SWCLK") (class "Default")
      (node (ref "J1") (pin "3") (pinfunction "3_3") (pintype "passive"))
      (node (ref "J7") (pin "P$10") (pinfunction "10_P$10") (pintype "passive"))
    )
    (net (code "15") (name "FLIGHT_MCU_SWDIO") (class "Default")
      (node (ref "J1") (pin "4") (pinfunction "4_4") (pintype "passive"))
      (node (ref "J7") (pin "P$9") (pinfunction "9_P$9") (pintype "passive"))
    )
    (net (code "16") (name "FLIGHT_MCU_SWO") (class "Default")
      (node (ref "J2") (pin "3") (pinfunction "3_3") (pintype "passive"))
      (node (ref "J7") (pin "P$8") (pinfunction "8_P$8") (pintype "passive"))
    )
    (net (code "17") (name "GND") (class "Default")
      (node (ref "C1") (pin "2") (pinfunction "2_2") (pintype "passive"))
      (node (ref "C10") (pin "2") (pinfunction "2_2") (pintype "passive"))
      (node (ref "C100") (pin "2") (pinfunction "2_2") (pintype "passive"))
      (node (ref "C101") (pin "1") (pinfunction "1_1") (pintype "passive"))
      (node (ref "C102") (pin "2") (pinfunction "2_2") (pintype "passive"))
      (node (ref "C103") (pin "2") (pinfunction "2_2") (pintype "passive"))
      (node (ref "C104") (pin "2") (pinfunction "2_2") (pintype "passive"))
      (node (ref "C105") (pin "2") (pinfunction "2_2") (pintype "passive"))
      (node (ref "C106") (pin "2") (pinfunction "2_2") (pintype "passive"))
      (node (ref "C107") (pin "2") (pinfunction "2_2") (pintype "passive"))
      (node (ref "C108") (pin "1") (pinfunction "1_1") (pintype "passive"))
      (node (ref "C109") (pin "2") (pinfunction "2_2") (pintype "passive"))
      (node (ref "C11") (pin "2") (pinfunction "2_2") (pintype "passive"))
      (node (ref "C110") (pin "2") (pinfunction "2_2") (pintype "passive"))
      (node (ref "C111") (pin "2") (pinfunction "2_2") (pintype "passive"))
      (node (ref "C112") (pin "2") (pinfunction "2_2") (pintype "passive"))
      (node (ref "C113") (pin "2") (pinfunction "2_2") (pintype "passive"))
      (node (ref "C115") (pin "2") (pinfunction "2_2") (pintype "passive"))
      (node (ref "C117") (pin "2") (pinfunction "2_2") (pintype "passive"))
      (node (ref "C12") (pin "2") (pinfunction "2_2") (pintype "passive"))
      (node (ref "C121") (pin "2") (pinfunction "2_2") (pintype "passive"))
      (node (ref "C123") (pin "2") (pinfunction "2_2") (pintype "passive"))
      (node (ref "C124") (pin "2") (pinfunction "2_2") (pintype "passive"))
      (node (ref "C125") (pin "2") (pinfunction "2_2") (pintype "passive"))
      (node (ref "C126") (pin "2") (pinfunction "2_2") (pintype "passive"))
      (node (ref "C127") (pin "1") (pinfunction "1_1") (pintype "passive"))
      (node (ref "C13") (pin "2") (pinfunction "2_2") (pintype "passive"))
      (node (ref "C130") (pin "2") (pinfunction "2_2") (pintype "passive"))
      (node (ref "C131") (pin "2") (pinfunction "2_2") (pintype "passive"))
      (node (ref "C133") (pin "2") (pinfunction "2_2") (pintype "passive"))
      (node (ref "C134") (pin "2") (pinfunction "2_2") (pintype "passive"))
      (node (ref "C136") (pin "2") (pinfunction "2_2") (pintype "passive"))
      (node (ref "C137") (pin "2") (pinfunction "2_2") (pintype "passive"))
      (node (ref "C138") (pin "2") (pinfunction "2_2") (pintype "passive"))
      (node (ref "C139") (pin "2") (pinfunction "2_2") (pintype "passive"))
      (node (ref "C14") (pin "2") (pinfunction "2_2") (pintype "passive"))
      (node (ref "C140") (pin "2") (pinfunction "2_2") (pintype "passive"))
      (node (ref "C142") (pin "2") (pinfunction "2_2") (pintype "passive"))
      (node (ref "C149") (pin "2") (pinfunction "2_2") (pintype "passive"))
      (node (ref "C15") (pin "2") (pinfunction "2_2") (pintype "passive"))
      (node (ref "C150") (pin "2") (pinfunction "2_2") (pintype "passive"))
      (node (ref "C151") (pin "2") (pinfunction "2_2") (pintype "passive"))
      (node (ref "C152") (pin "2") (pinfunction "2_2") (pintype "passive"))
      (node (ref "C159") (pin "2") (pinfunction "2_2") (pintype "passive"))
      (node (ref "C16") (pin "2") (pinfunction "2_2") (pintype "passive"))
      (node (ref "C160") (pin "2") (pinfunction "2_2") (pintype "passive"))
      (node (ref "C161") (pin "2") (pinfunction "2_2") (pintype "passive"))
      (node (ref "C162") (pin "2") (pinfunction "2_2") (pintype "passive"))
      (node (ref "C17") (pin "2") (pinfunction "2_2") (pintype "passive"))
      (node (ref "C18") (pin "2") (pinfunction "2_2") (pintype "passive"))
      (node (ref "C19") (pin "2") (pinfunction "2_2") (pintype "passive"))
      (node (ref "C2") (pin "2") (pinfunction "2_2") (pintype "passive"))
      (node (ref "C20") (pin "2") (pinfunction "2_2") (pintype "passive"))
      (node (ref "C21") (pin "2") (pinfunction "2_2") (pintype "passive"))
      (node (ref "C22") (pin "2") (pinfunction "2_2") (pintype "passive"))
      (node (ref "C23") (pin "2") (pinfunction "2_2") (pintype "passive"))
      (node (ref "C24") (pin "2") (pinfunction "2_2") (pintype "passive"))
      (node (ref "C25") (pin "2") (pinfunction "2_2") (pintype "passive"))
      (node (ref "C26") (pin "2") (pinfunction "2_2") (pintype "passive"))
      (node (ref "C28") (pin "2") (pinfunction "2_2") (pintype "passive"))
      (node (ref "C29") (pin "2") (pinfunction "2_2") (pintype "passive"))
      (node (ref "C3") (pin "2") (pinfunction "2_2") (pintype "passive"))
      (node (ref "C30") (pin "2") (pinfunction "2_2") (pintype "passive"))
      (node (ref "C31") (pin "2") (pinfunction "2_2") (pintype "passive"))
      (node (ref "C32") (pin "2") (pinfunction "2_2") (pintype "passive"))
      (node (ref "C33") (pin "2") (pinfunction "2_2") (pintype "passive"))
      (node (ref "C34") (pin "2") (pinfunction "2_2") (pintype "passive"))
      (node (ref "C36") (pin "2") (pinfunction "2_2") (pintype "passive"))
      (node (ref "C37") (pin "2") (pinfunction "2_2") (pintype "passive"))
      (node (ref "C39") (pin "2") (pinfunction "2_2") (pintype "passive"))
      (node (ref "C4") (pin "2") (pinfunction "2_2") (pintype "passive"))
      (node (ref "C40") (pin "2") (pinfunction "2_2") (pintype "passive"))
      (node (ref "C41") (pin "2") (pinfunction "2_2") (pintype "passive"))
      (node (ref "C42") (pin "2") (pinfunction "2_2") (pintype "passive"))
      (node (ref "C43") (pin "2") (pinfunction "2_2") (pintype "passive"))
      (node (ref "C44") (pin "2") (pinfunction "2_2") (pintype "passive"))
      (node (ref "C45") (pin "2") (pinfunction "2_2") (pintype "passive"))
      (node (ref "C47") (pin "2") (pinfunction "2_2") (pintype "passive"))
      (node (ref "C48") (pin "2") (pinfunction "2_2") (pintype "passive"))
      (node (ref "C5") (pin "2") (pinfunction "2_2") (pintype "passive"))
      (node (ref "C50") (pin "2") (pinfunction "2_2") (pintype "passive"))
      (node (ref "C51") (pin "2") (pinfunction "2_2") (pintype "passive"))
      (node (ref "C52") (pin "2") (pinfunction "2_2") (pintype "passive"))
      (node (ref "C53") (pin "2") (pinfunction "2_2") (pintype "passive"))
      (node (ref "C54") (pin "2") (pinfunction "2_2") (pintype "passive"))
      (node (ref "C55") (pin "2") (pinfunction "2_2") (pintype "passive"))
      (node (ref "C56") (pin "2") (pinfunction "2_2") (pintype "passive"))
      (node (ref "C58") (pin "2") (pinfunction "2_2") (pintype "passive"))
      (node (ref "C59") (pin "2") (pinfunction "2_2") (pintype "passive"))
      (node (ref "C6") (pin "2") (pinfunction "2_2") (pintype "passive"))
      (node (ref "C61") (pin "2") (pinfunction "2_2") (pintype "passive"))
      (node (ref "C62") (pin "2") (pinfunction "2_2") (pintype "passive"))
      (node (ref "C63") (pin "2") (pinfunction "2_2") (pintype "passive"))
      (node (ref "C64") (pin "2") (pinfunction "2_2") (pintype "passive"))
      (node (ref "C65") (pin "2") (pinfunction "2_2") (pintype "passive"))
      (node (ref "C66") (pin "2") (pinfunction "2_2") (pintype "passive"))
      (node (ref "C67") (pin "2") (pinfunction "2_2") (pintype "passive"))
      (node (ref "C69") (pin "2") (pinfunction "2_2") (pintype "passive"))
      (node (ref "C7") (pin "2") (pinfunction "2_2") (pintype "passive"))
      (node (ref "C70") (pin "2") (pinfunction "2_2") (pintype "passive"))
      (node (ref "C72") (pin "2") (pinfunction "2_2") (pintype "passive"))
      (node (ref "C73") (pin "2") (pinfunction "2_2") (pintype "passive"))
      (node (ref "C74") (pin "2") (pinfunction "2_2") (pintype "passive"))
      (node (ref "C75") (pin "2") (pinfunction "2_2") (pintype "passive"))
      (node (ref "C76") (pin "2") (pinfunction "2_2") (pintype "passive"))
      (node (ref "C77") (pin "2") (pinfunction "2_2") (pintype "passive"))
      (node (ref "C78") (pin "2") (pinfunction "2_2") (pintype "passive"))
      (node (ref "C8") (pin "2") (pinfunction "2_2") (pintype "passive"))
      (node (ref "C80") (pin "2") (pinfunction "2_2") (pintype "passive"))
      (node (ref "C81") (pin "2") (pinfunction "2_2") (pintype "passive"))
      (node (ref "C83") (pin "2") (pinfunction "2_2") (pintype "passive"))
      (node (ref "C84") (pin "2") (pinfunction "2_2") (pintype "passive"))
      (node (ref "C85") (pin "2") (pinfunction "2_2") (pintype "passive"))
      (node (ref "C86") (pin "2") (pinfunction "2_2") (pintype "passive"))
      (node (ref "C87") (pin "2") (pinfunction "2_2") (pintype "passive"))
      (node (ref "C88") (pin "2") (pinfunction "2_2") (pintype "passive"))
      (node (ref "C89") (pin "2") (pinfunction "2_2") (pintype "passive"))
      (node (ref "C9") (pin "2") (pinfunction "2_2") (pintype "passive"))
      (node (ref "C91") (pin "2") (pinfunction "2_2") (pintype "passive"))
      (node (ref "C92") (pin "2") (pinfunction "2_2") (pintype "passive"))
      (node (ref "C94") (pin "2") (pinfunction "2_2") (pintype "passive"))
      (node (ref "C95") (pin "2") (pinfunction "2_2") (pintype "passive"))
      (node (ref "C96") (pin "2") (pinfunction "2_2") (pintype "passive"))
      (node (ref "C97") (pin "2") (pinfunction "2_2") (pintype "passive"))
      (node (ref "C98") (pin "2") (pinfunction "2_2") (pintype "passive"))
      (node (ref "C99") (pin "2") (pinfunction "2_2") (pintype "passive"))
      (node (ref "D13") (pin "A") (pinfunction "A_A") (pintype "passive"))
      (node (ref "D15") (pin "A") (pinfunction "A_A") (pintype "passive"))
      (node (ref "D8") (pin "A") (pinfunction "A_A") (pintype "passive"))
      (node (ref "J1") (pin "13") (pinfunction "13_13") (pintype "passive"))
      (node (ref "J1") (pin "18") (pinfunction "18_18") (pintype "passive"))
      (node (ref "J1") (pin "19") (pinfunction "19_19") (pintype "passive"))
      (node (ref "J1") (pin "21") (pinfunction "21_21") (pintype "passive"))
      (node (ref "J2") (pin "17") (pinfunction "17_17") (pintype "passive"))
      (node (ref "J2") (pin "22") (pinfunction "22_22") (pintype "passive"))
      (node (ref "J2") (pin "29") (pinfunction "29_29") (pintype "passive"))
      (node (ref "J2") (pin "30") (pinfunction "30_30") (pintype "passive"))
      (node (ref "J2") (pin "31") (pinfunction "31_31") (pintype "passive"))
      (node (ref "J2") (pin "32") (pinfunction "32_32") (pintype "passive"))
      (node (ref "J2") (pin "9") (pinfunction "9_9") (pintype "passive"))
      (node (ref "J6") (pin "P$1") (pinfunction "1_P$1") (pintype "passive"))
      (node (ref "J6") (pin "P$7") (pinfunction "7_P$7") (pintype "passive"))
      (node (ref "J7") (pin "P$2") (pinfunction "2_P$2") (pintype "passive"))
      (node (ref "J7") (pin "P$4") (pinfunction "4_P$4") (pintype "passive"))
      (node (ref "J7") (pin "P$6") (pinfunction "6_P$6") (pintype "passive"))
      (node (ref "J8") (pin "P$3") (pinfunction "3_P$3") (pintype "passive"))
      (node (ref "J9") (pin "P$3") (pinfunction "3_P$3") (pintype "passive"))
      (node (ref "Q3") (pin "3") (pinfunction "S_3") (pintype "passive"))
      (node (ref "R103") (pin "1") (pinfunction "1_1") (pintype "passive"))
      (node (ref "R105") (pin "1") (pinfunction "1_1") (pintype "passive"))
      (node (ref "R122") (pin "1") (pinfunction "1_1") (pintype "passive"))
      (node (ref "R123") (pin "1") (pinfunction "1_1") (pintype "passive"))
      (node (ref "R126") (pin "1") (pinfunction "1_1") (pintype "passive"))
      (node (ref "R130") (pin "1") (pinfunction "1_1") (pintype "passive"))
      (node (ref "R133") (pin "1") (pinfunction "1_1") (pintype "passive"))
      (node (ref "R139") (pin "1") (pinfunction "1_1") (pintype "passive"))
      (node (ref "R26") (pin "1") (pinfunction "1_1") (pintype "passive"))
      (node (ref "R28") (pin "1") (pinfunction "1_1") (pintype "passive"))
      (node (ref "R32") (pin "1") (pinfunction "1_1") (pintype "passive"))
      (node (ref "R34") (pin "1") (pinfunction "1_1") (pintype "passive"))
      (node (ref "R36") (pin "1") (pinfunction "1_1") (pintype "passive"))
      (node (ref "R38") (pin "1") (pinfunction "1_1") (pintype "passive"))
      (node (ref "R47") (pin "1") (pinfunction "1_1") (pintype "passive"))
      (node (ref "R56") (pin "1") (pinfunction "1_1") (pintype "passive"))
      (node (ref "R65") (pin "1") (pinfunction "1_1") (pintype "passive"))
      (node (ref "R74") (pin "1") (pinfunction "1_1") (pintype "passive"))
      (node (ref "R83") (pin "1") (pinfunction "1_1") (pintype "passive"))
      (node (ref "R92") (pin "1") (pinfunction "1_1") (pintype "passive"))
      (node (ref "R94") (pin "1") (pinfunction "1_1") (pintype "passive"))
      (node (ref "R96") (pin "1") (pinfunction "1_1") (pintype "passive"))
      (node (ref "R98") (pin "1") (pinfunction "1_1") (pintype "passive"))
      (node (ref "SH1") (pin "1") (pinfunction "P$1_1") (pintype "bidirectional"))
      (node (ref "SH1") (pin "2") (pinfunction "P$2_2") (pintype "bidirectional"))
      (node (ref "SH2") (pin "1") (pinfunction "P$1_1") (pintype "bidirectional"))
      (node (ref "SH2") (pin "2") (pinfunction "P$2_2") (pintype "bidirectional"))
      (node (ref "TP33") (pin "TP") (pinfunction "TP_TP") (pintype "input"))
      (node (ref "U1") (pin "1") (pinfunction "REF_1") (pintype "bidirectional"))
      (node (ref "U1") (pin "2") (pinfunction "GND_2") (pintype "power_in"))
      (node (ref "U10") (pin "1") (pinfunction "REF_1") (pintype "bidirectional"))
      (node (ref "U10") (pin "2") (pinfunction "GND_2") (pintype "power_in"))
      (node (ref "U11") (pin "1") (pinfunction "REF_1") (pintype "bidirectional"))
      (node (ref "U11") (pin "2") (pinfunction "GND_2") (pintype "power_in"))
      (node (ref "U12") (pin "1") (pinfunction "REF_1") (pintype "bidirectional"))
      (node (ref "U12") (pin "2") (pinfunction "GND_2") (pintype "power_in"))
      (node (ref "U13") (pin "5") (pinfunction "V-_5") (pintype "power_in"))
      (node (ref "U14") (pin "1") (pinfunction "REF_1") (pintype "bidirectional"))
      (node (ref "U14") (pin "2") (pinfunction "GND_2") (pintype "power_in"))
      (node (ref "U15") (pin "3") (pinfunction "V-_3") (pintype "power_in"))
      (node (ref "U16") (pin "2") (pinfunction "GND_2") (pintype "bidirectional"))
      (node (ref "U16") (pin "6") (pinfunction "~{OE}_6") (pintype "bidirectional"))
      (node (ref "U17") (pin "3") (pinfunction "S_3") (pintype "passive"))
      (node (ref "U18") (pin "5") (pinfunction "V-_5") (pintype "power_in"))
      (node (ref "U19") (pin "1") (pinfunction "REF_1") (pintype "bidirectional"))
      (node (ref "U19") (pin "2") (pinfunction "GND_2") (pintype "power_in"))
      (node (ref "U2") (pin "1") (pinfunction "REF_1") (pintype "bidirectional"))
      (node (ref "U2") (pin "2") (pinfunction "GND_2") (pintype "power_in"))
      (node (ref "U20") (pin "3") (pinfunction "V-_3") (pintype "power_in"))
      (node (ref "U21") (pin "2") (pinfunction "GND_2") (pintype "bidirectional"))
      (node (ref "U21") (pin "6") (pinfunction "~{OE}_6") (pintype "bidirectional"))
      (node (ref "U22") (pin "3") (pinfunction "S_3") (pintype "passive"))
      (node (ref "U23") (pin "5") (pinfunction "V-_5") (pintype "power_in"))
      (node (ref "U24") (pin "1") (pinfunction "REF_1") (pintype "bidirectional"))
      (node (ref "U24") (pin "2") (pinfunction "GND_2") (pintype "power_in"))
      (node (ref "U25") (pin "3") (pinfunction "V-_3") (pintype "power_in"))
      (node (ref "U26") (pin "2") (pinfunction "GND_2") (pintype "bidirectional"))
      (node (ref "U26") (pin "6") (pinfunction "~{OE}_6") (pintype "bidirectional"))
      (node (ref "U27") (pin "3") (pinfunction "S_3") (pintype "passive"))
      (node (ref "U28") (pin "5") (pinfunction "V-_5") (pintype "power_in"))
      (node (ref "U29") (pin "1") (pinfunction "REF_1") (pintype "bidirectional"))
      (node (ref "U29") (pin "2") (pinfunction "GND_2") (pintype "power_in"))
      (node (ref "U3") (pin "1") (pinfunction "REF_1") (pintype "bidirectional"))
      (node (ref "U3") (pin "2") (pinfunction "GND_2") (pintype "power_in"))
      (node (ref "U30") (pin "3") (pinfunction "V-_3") (pintype "power_in"))
      (node (ref "U31") (pin "2") (pinfunction "GND_2") (pintype "bidirectional"))
      (node (ref "U31") (pin "6") (pinfunction "~{OE}_6") (pintype "bidirectional"))
      (node (ref "U32") (pin "3") (pinfunction "S_3") (pintype "passive"))
      (node (ref "U33") (pin "5") (pinfunction "V-_5") (pintype "power_in"))
      (node (ref "U34") (pin "1") (pinfunction "REF_1") (pintype "bidirectional"))
      (node (ref "U34") (pin "2") (pinfunction "GND_2") (pintype "power_in"))
      (node (ref "U35") (pin "3") (pinfunction "V-_3") (pintype "power_in"))
      (node (ref "U36") (pin "2") (pinfunction "GND_2") (pintype "bidirectional"))
      (node (ref "U36") (pin "6") (pinfunction "~{OE}_6") (pintype "bidirectional"))
      (node (ref "U37") (pin "3") (pinfunction "S_3") (pintype "passive"))
      (node (ref "U38") (pin "5") (pinfunction "V-_5") (pintype "power_in"))
      (node (ref "U39") (pin "1") (pinfunction "REF_1") (pintype "bidirectional"))
      (node (ref "U39") (pin "2") (pinfunction "GND_2") (pintype "power_in"))
      (node (ref "U4") (pin "1") (pinfunction "REF_1") (pintype "bidirectional"))
      (node (ref "U4") (pin "2") (pinfunction "GND_2") (pintype "power_in"))
      (node (ref "U40") (pin "3") (pinfunction "V-_3") (pintype "power_in"))
      (node (ref "U41") (pin "2") (pinfunction "GND_2") (pintype "bidirectional"))
      (node (ref "U41") (pin "6") (pinfunction "~{OE}_6") (pintype "bidirectional"))
      (node (ref "U42") (pin "1") (pinfunction "S_1") (pintype "passive"))
      (node (ref "U43") (pin "2") (pinfunction "V-_2") (pintype "power_in"))
      (node (ref "U44") (pin "15") (pinfunction "PGND_15") (pintype "power_in"))
      (node (ref "U44") (pin "16") (pinfunction "PGND_16") (pintype "power_in"))
      (node (ref "U44") (pin "5") (pinfunction "FB_5") (pintype "bidirectional"))
      (node (ref "U44") (pin "6") (pinfunction "AGND_6") (pintype "power_in"))
      (node (ref "U44") (pin "8") (pinfunction "DEF_8") (pintype "bidirectional"))
      (node (ref "U44") (pin "PAD") (pinfunction "AGND_PAD") (pintype "power_in"))
      (node (ref "U45") (pin "1") (pinfunction "S_1") (pintype "passive"))
      (node (ref "U46") (pin "2") (pinfunction "V-_2") (pintype "power_in"))
      (node (ref "U47") (pin "15") (pinfunction "PGND_15") (pintype "power_in"))
      (node (ref "U47") (pin "16") (pinfunction "PGND_16") (pintype "power_in"))
      (node (ref "U47") (pin "5") (pinfunction "FB_5") (pintype "bidirectional"))
      (node (ref "U47") (pin "6") (pinfunction "AGND_6") (pintype "power_in"))
      (node (ref "U47") (pin "8") (pinfunction "DEF_8") (pintype "bidirectional"))
      (node (ref "U47") (pin "PAD") (pinfunction "AGND_PAD") (pintype "power_in"))
      (node (ref "U48") (pin "1") (pinfunction "S_1") (pintype "passive"))
      (node (ref "U49") (pin "1") (pinfunction "1_1") (pintype "power_in"))
      (node (ref "U49") (pin "TP") (pinfunction "33_TP") (pintype "power_in"))
      (node (ref "U5") (pin "1") (pinfunction "REF_1") (pintype "bidirectional"))
      (node (ref "U5") (pin "2") (pinfunction "GND_2") (pintype "power_in"))
      (node (ref "U50") (pin "20") (pinfunction "~{CS}_20") (pintype "input"))
      (node (ref "U50") (pin "21") (pinfunction "~{WR}_21") (pintype "input"))
      (node (ref "U50") (pin "22") (pinfunction "~{EN}_22") (pintype "input"))
      (node (ref "U50") (pin "23") (pinfunction "GND_23") (pintype "power_in"))
      (node (ref "U50") (pin "24") (pinfunction "VSS_24") (pintype "power_in"))
      (node (ref "U50") (pin "EXP") (pinfunction "GND_EXP") (pintype "power_in"))
      (node (ref "U52") (pin "2") (pinfunction "GND_2") (pintype "power_in"))
      (node (ref "U52") (pin "5") (pinfunction "VCTRL_5") (pintype "bidirectional"))
      (node (ref "U53") (pin "11") (pinfunction "GND_11") (pintype "power_in"))
      (node (ref "U53") (pin "17") (pinfunction "EPAD_17") (pintype "power_in"))
      (node (ref "U54") (pin "1") (pinfunction "REF_1") (pintype "bidirectional"))
      (node (ref "U54") (pin "2") (pinfunction "GND_2") (pintype "power_in"))
      (node (ref "U56") (pin "2") (pinfunction "GND_2") (pintype "power_in"))
      (node (ref "U56") (pin "5") (pinfunction "VCTRL_5") (pintype "bidirectional"))
      (node (ref "U58") (pin "2") (pinfunction "GND_2") (pintype "power_in"))
      (node (ref "U58") (pin "5") (pinfunction "VCTRL_5") (pintype "bidirectional"))
      (node (ref "U6") (pin "1") (pinfunction "REF_1") (pintype "bidirectional"))
      (node (ref "U6") (pin "2") (pinfunction "GND_2") (pintype "power_in"))
      (node (ref "U7") (pin "1") (pinfunction "REF_1") (pintype "bidirectional"))
      (node (ref "U7") (pin "2") (pinfunction "GND_2") (pintype "power_in"))
      (node (ref "U8") (pin "1") (pinfunction "REF_1") (pintype "bidirectional"))
      (node (ref "U8") (pin "2") (pinfunction "GND_2") (pintype "power_in"))
      (node (ref "U9") (pin "1") (pinfunction "REF_1") (pintype "bidirectional"))
      (node (ref "U9") (pin "2") (pinfunction "GND_2") (pintype "power_in"))
    )
    (net (code "18") (name "MCU_INT") (class "Default")
      (node (ref "J2") (pin "47") (pinfunction "47_47") (pintype "passive"))
      (node (ref "U49") (pin "15") (pinfunction "15_15") (pintype "bidirectional"))
    )
    (net (code "19") (name "MCU_RX") (class "Default")
      (node (ref "J1") (pin "47") (pinfunction "47_47") (pintype "passive"))
      (node (ref "U49") (pin "14") (pinfunction "14_14") (pintype "bidirectional"))
    )
    (net (code "20") (name "MCU_TX") (class "Default")
      (node (ref "J1") (pin "48") (pinfunction "48_48") (pintype "passive"))
      (node (ref "U49") (pin "13") (pinfunction "13_13") (pintype "bidirectional"))
    )
    (net (code "21") (name "MPPSET") (class "Default")
      (node (ref "C128") (pin "2") (pinfunction "2_2") (pintype "passive"))
      (node (ref "R129") (pin "1") (pinfunction "1_1") (pintype "passive"))
      (node (ref "R130") (pin "2") (pinfunction "2_2") (pintype "passive"))
      (node (ref "U53") (pin "2") (pinfunction "MPPSET_2") (pintype "input"))
    )
    (net (code "22") (name "MPPT1H_PV_P") (class "Default")
      (node (ref "C114") (pin "1") (pinfunction "1_1") (pintype "passive"))
      (node (ref "L3") (pin "1") (pinfunction "1_1") (pintype "passive"))
      (node (ref "R110") (pin "1") (pinfunction "1_1") (pintype "passive"))
      (node (ref "R6") (pin "2") (pinfunction "2_2") (pintype "passive"))
      (node (ref "R9") (pin "2") (pinfunction "2_2") (pintype "passive"))
      (node (ref "U4") (pin "5") (pinfunction "IN-_5") (pintype "bidirectional"))
      (node (ref "U5") (pin "5") (pinfunction "IN-_5") (pintype "bidirectional"))
    )
    (net (code "23") (name "MPPT1L_PV_P") (class "Default")
      (node (ref "C115") (pin "1") (pinfunction "1_1") (pintype "passive"))
      (node (ref "L4") (pin "1") (pinfunction "1_1") (pintype "passive"))
      (node (ref "R111") (pin "1") (pinfunction "1_1") (pintype "passive"))
      (node (ref "R16") (pin "2") (pinfunction "2_2") (pintype "passive"))
      (node (ref "R19") (pin "2") (pinfunction "2_2") (pintype "passive"))
      (node (ref "U10") (pin "5") (pinfunction "IN-_5") (pintype "bidirectional"))
      (node (ref "U9") (pin "5") (pinfunction "IN-_5") (pintype "bidirectional"))
    )
    (net (code "24") (name "MPPT1_MID") (class "Default")
      (node (ref "C114") (pin "2") (pinfunction "2_2") (pintype "passive"))
      (node (ref "C116") (pin "2") (pinfunction "2_2") (pintype "passive"))
      (node (ref "C120") (pin "2") (pinfunction "2_2") (pintype "passive"))
      (node (ref "C122") (pin "2") (pinfunction "2_2") (pintype "passive"))
      (node (ref "C123") (pin "1") (pinfunction "1_1") (pintype "passive"))
      (node (ref "D7") (pin "A") (pinfunction "A_A") (pintype "passive"))
      (node (ref "J6") (pin "P$6") (pinfunction "6_P$6") (pintype "passive"))
      (node (ref "J8") (pin "P$2") (pinfunction "2_P$2") (pintype "passive"))
      (node (ref "R115") (pin "1") (pinfunction "1_1") (pintype "passive"))
      (node (ref "R117") (pin "1") (pinfunction "1_1") (pintype "passive"))
      (node (ref "TP29") (pin "TP") (pinfunction "TP_TP") (pintype "input"))
      (node (ref "U51") (pin "2") (pinfunction "GND_2") (pintype "power_in"))
      (node (ref "U51") (pin "5") (pinfunction "VCTRL_5") (pintype "bidirectional"))
    )
    (net (code "25") (name "MPPT2H_PV_P") (class "Default")
      (node (ref "C146") (pin "1") (pinfunction "1_1") (pintype "passive"))
      (node (ref "L6") (pin "1") (pinfunction "1_1") (pintype "passive"))
      (node (ref "R10") (pin "2") (pinfunction "2_2") (pintype "passive"))
      (node (ref "R13") (pin "2") (pinfunction "2_2") (pintype "passive"))
      (node (ref "R143") (pin "1") (pinfunction "1_1") (pintype "passive"))
      (node (ref "U6") (pin "5") (pinfunction "IN-_5") (pintype "bidirectional"))
      (node (ref "U7") (pin "5") (pinfunction "IN-_5") (pintype "bidirectional"))
    )
    (net (code "26") (name "MPPT2L_PV_P") (class "Default")
      (node (ref "C151") (pin "1") (pinfunction "1_1") (pintype "passive"))
      (node (ref "L7") (pin "1") (pinfunction "1_1") (pintype "passive"))
      (node (ref "R147") (pin "1") (pinfunction "1_1") (pintype "passive"))
      (node (ref "R20") (pin "2") (pinfunction "2_2") (pintype "passive"))
      (node (ref "R23") (pin "2") (pinfunction "2_2") (pintype "passive"))
      (node (ref "R25") (pin "2") (pinfunction "2_2") (pintype "passive"))
      (node (ref "U11") (pin "5") (pinfunction "IN-_5") (pintype "bidirectional"))
      (node (ref "U12") (pin "5") (pinfunction "IN-_5") (pintype "bidirectional"))
    )
    (net (code "27") (name "MPPT2_LOWER_PV_VSENSE") (class "Default")
      (node (ref "C25") (pin "1") (pinfunction "1_1") (pintype "passive"))
      (node (ref "R25") (pin "1") (pinfunction "1_1") (pintype "passive"))
      (node (ref "R26") (pin "2") (pinfunction "2_2") (pintype "passive"))
      (node (ref "U50") (pin "30") (pinfunction "S22_30") (pintype "bidirectional"))
    )
    (net (code "28") (name "MPPT2_MID") (class "Default")
      (node (ref "C144") (pin "2") (pinfunction "2_2") (pintype "passive"))
      (node (ref "C145") (pin "2") (pinfunction "2_2") (pintype "passive"))
      (node (ref "C146") (pin "2") (pinfunction "2_2") (pintype "passive"))
      (node (ref "C147") (pin "2") (pinfunction "2_2") (pintype "passive"))
      (node (ref "C150") (pin "1") (pinfunction "1_1") (pintype "passive"))
      (node (ref "D12") (pin "A") (pinfunction "A_A") (pintype "passive"))
      (node (ref "J2") (pin "16") (pinfunction "16_16") (pintype "passive"))
      (node (ref "J9") (pin "P$2") (pinfunction "2_P$2") (pintype "passive"))
      (node (ref "R145") (pin "1") (pinfunction "1_1") (pintype "passive"))
      (node (ref "R146") (pin "1") (pinfunction "1_1") (pintype "passive"))
      (node (ref "R27") (pin "2") (pinfunction "2_2") (pintype "passive"))
      (node (ref "TP32") (pin "TP") (pinfunction "TP_TP") (pintype "input"))
      (node (ref "U55") (pin "2") (pinfunction "GND_2") (pintype "power_in"))
      (node (ref "U55") (pin "5") (pinfunction "VCTRL_5") (pintype "bidirectional"))
    )
    (net (code "29") (name "MPPT2_MID_PV_VSENSE") (class "Default")
      (node (ref "C26") (pin "1") (pinfunction "1_1") (pintype "passive"))
      (node (ref "R27") (pin "1") (pinfunction "1_1") (pintype "passive"))
      (node (ref "R28") (pin "2") (pinfunction "2_2") (pintype "passive"))
      (node (ref "U50") (pin "31") (pinfunction "S23_31") (pintype "bidirectional"))
    )
    (net (code "30") (name "MPPT3H_PV_P") (class "Default")
      (node (ref "C156") (pin "1") (pinfunction "1_1") (pintype "passive"))
      (node (ref "L8") (pin "1") (pinfunction "1_1") (pintype "passive"))
      (node (ref "R151") (pin "1") (pinfunction "1_1") (pintype "passive"))
      (node (ref "R5") (pin "2") (pinfunction "2_2") (pintype "passive"))
      (node (ref "U3") (pin "5") (pinfunction "IN-_5") (pintype "bidirectional"))
    )
    (net (code "31") (name "MPPT3L_PV_P") (class "Default")
      (node (ref "C161") (pin "1") (pinfunction "1_1") (pintype "passive"))
      (node (ref "L9") (pin "1") (pinfunction "1_1") (pintype "passive"))
      (node (ref "R15") (pin "2") (pinfunction "2_2") (pintype "passive"))
      (node (ref "R155") (pin "1") (pinfunction "1_1") (pintype "passive"))
      (node (ref "U8") (pin "5") (pinfunction "IN-_5") (pintype "bidirectional"))
    )
    (net (code "32") (name "MPPT3_MID") (class "Default")
      (node (ref "C154") (pin "2") (pinfunction "2_2") (pintype "passive"))
      (node (ref "C155") (pin "2") (pinfunction "2_2") (pintype "passive"))
      (node (ref "C156") (pin "2") (pinfunction "2_2") (pintype "passive"))
      (node (ref "C157") (pin "2") (pinfunction "2_2") (pintype "passive"))
      (node (ref "C160") (pin "1") (pinfunction "1_1") (pintype "passive"))
      (node (ref "D14") (pin "A") (pinfunction "A_A") (pintype "passive"))
      (node (ref "J2") (pin "8") (pinfunction "8_8") (pintype "passive"))
      (node (ref "R153") (pin "1") (pinfunction "1_1") (pintype "passive"))
      (node (ref "R154") (pin "1") (pinfunction "1_1") (pintype "passive"))
      (node (ref "TP35") (pin "TP") (pinfunction "TP_TP") (pintype "input"))
      (node (ref "U57") (pin "2") (pinfunction "GND_2") (pintype "power_in"))
      (node (ref "U57") (pin "5") (pinfunction "VCTRL_5") (pintype "bidirectional"))
    )
    (net (code "33") (name "MPPT_BUS_VSENSE") (class "Default")
      (node (ref "C28") (pin "1") (pinfunction "1_1") (pintype "passive"))
      (node (ref "R31") (pin "1") (pinfunction "1_1") (pintype "passive"))
      (node (ref "R32") (pin "2") (pinfunction "2_2") (pintype "passive"))
      (node (ref "U50") (pin "29") (pinfunction "S21_29") (pintype "bidirectional"))
    )
    (net (code "34") (name "MSP-RST") (class "Default")
      (node (ref "C112") (pin "1") (pinfunction "1_1") (pintype "passive"))
      (node (ref "J6") (pin "P$4") (pinfunction "4_P$4") (pintype "passive"))
      (node (ref "R109") (pin "1") (pinfunction "1_1") (pintype "passive"))
      (node (ref "U49") (pin "5") (pinfunction "5_5") (pintype "input"))
    )
    (net (code "35") (name "MSP-TEST") (class "Default")
      (node (ref "J6") (pin "P$3") (pinfunction "3_P$3") (pintype "passive"))
      (node (ref "U49") (pin "29") (pinfunction "29_29") (pintype "input"))
    )
    (net (code "36") (name "MUX_A0") (class "Default")
      (node (ref "U49") (pin "32") (pinfunction "32_32") (pintype "bidirectional"))
      (node (ref "U50") (pin "15") (pinfunction "A0_15") (pintype "input"))
    )
    (net (code "37") (name "MUX_A1") (class "Default")
      (node (ref "U49") (pin "18") (pinfunction "18_18") (pintype "bidirectional"))
      (node (ref "U50") (pin "16") (pinfunction "A1_16") (pintype "input"))
    )
    (net (code "38") (name "MUX_A2") (class "Default")
      (node (ref "U49") (pin "8") (pinfunction "8_8") (pintype "bidirectional"))
      (node (ref "U50") (pin "17") (pinfunction "A2_17") (pintype "input"))
    )
    (net (code "39") (name "MUX_A3") (class "Default")
      (node (ref "U49") (pin "7") (pinfunction "7_7") (pintype "bidirectional"))
      (node (ref "U50") (pin "18") (pinfunction "A3_18") (pintype "input"))
    )
    (net (code "40") (name "MUX_A4") (class "Default")
      (node (ref "U49") (pin "6") (pinfunction "6_6") (pintype "bidirectional"))
      (node (ref "U50") (pin "19") (pinfunction "A4_19") (pintype "input"))
    )
    (net (code "41") (name "MUX_OUT") (class "Default")
      (node (ref "U49") (pin "16") (pinfunction "16_16") (pintype "bidirectional"))
      (node (ref "U50") (pin "43") (pinfunction "D_43") (pintype "bidirectional"))
    )
    (net (code "42") (name "Net-(C124-Pad1)") (class "Default")
      (node (ref "C124") (pin "1") (pinfunction "1_1") (pintype "passive"))
      (node (ref "R120") (pin "1") (pinfunction "1_1") (pintype "passive"))
      (node (ref "R121") (pin "1") (pinfunction "1_1") (pintype "passive"))
    )
    (net (code "43") (name "Net-(C135-Pad2)") (class "Default")
      (node (ref "C135") (pin "2") (pinfunction "2_2") (pintype "passive"))
      (node (ref "R133") (pin "2") (pinfunction "2_2") (pintype "passive"))
    )
    (net (code "44") (name "Net-(C141-Pad1)") (class "Default")
      (node (ref "C141") (pin "1") (pinfunction "1_1") (pintype "passive"))
      (node (ref "R137") (pin "1") (pinfunction "1_1") (pintype "passive"))
      (node (ref "R138") (pin "2") (pinfunction "2_2") (pintype "passive"))
    )
    (net (code "45") (name "Net-(D1-A)") (class "Default")
      (node (ref "C38") (pin "1") (pinfunction "1_1") (pintype "passive"))
      (node (ref "D1") (pin "2") (pinfunction "A_2") (pintype "passive"))
      (node (ref "R43") (pin "1") (pinfunction "1_1") (pintype "passive"))
      (node (ref "U16") (pin "1") (pinfunction "LE_1") (pintype "bidirectional"))
    )
    (net (code "46") (name "Net-(D2-A)") (class "Default")
      (node (ref "C49") (pin "1") (pinfunction "1_1") (pintype "passive"))
      (node (ref "D2") (pin "2") (pinfunction "A_2") (pintype "passive"))
      (node (ref "R52") (pin "1") (pinfunction "1_1") (pintype "passive"))
      (node (ref "U21") (pin "1") (pinfunction "LE_1") (pintype "bidirectional"))
    )
    (net (code "47") (name "Net-(D3-A)") (class "Default")
      (node (ref "C60") (pin "1") (pinfunction "1_1") (pintype "passive"))
      (node (ref "D3") (pin "2") (pinfunction "A_2") (pintype "passive"))
      (node (ref "R61") (pin "1") (pinfunction "1_1") (pintype "passive"))
      (node (ref "U26") (pin "1") (pinfunction "LE_1") (pintype "bidirectional"))
    )
    (net (code "48") (name "Net-(D4-A)") (class "Default")
      (node (ref "C71") (pin "1") (pinfunction "1_1") (pintype "passive"))
      (node (ref "D4") (pin "2") (pinfunction "A_2") (pintype "passive"))
      (node (ref "R70") (pin "1") (pinfunction "1_1") (pintype "passive"))
      (node (ref "U31") (pin "1") (pinfunction "LE_1") (pintype "bidirectional"))
    )
    (net (code "49") (name "Net-(D5-A)") (class "Default")
      (node (ref "C82") (pin "1") (pinfunction "1_1") (pintype "passive"))
      (node (ref "D5") (pin "2") (pinfunction "A_2") (pintype "passive"))
      (node (ref "R79") (pin "1") (pinfunction "1_1") (pintype "passive"))
      (node (ref "U36") (pin "1") (pinfunction "LE_1") (pintype "bidirectional"))
    )
    (net (code "50") (name "Net-(D6-A)") (class "Default")
      (node (ref "C93") (pin "1") (pinfunction "1_1") (pintype "passive"))
      (node (ref "D6") (pin "2") (pinfunction "A_2") (pintype "passive"))
      (node (ref "R88") (pin "1") (pinfunction "1_1") (pintype "passive"))
      (node (ref "U41") (pin "1") (pinfunction "LE_1") (pintype "bidirectional"))
    )
    (net (code "51") (name "Net-(D10-A)") (class "Default")
      (node (ref "C130") (pin "1") (pinfunction "1_1") (pintype "passive"))
      (node (ref "D10") (pin "2") (pinfunction "A_2") (pintype "passive"))
      (node (ref "U53") (pin "12") (pinfunction "REGN_12") (pintype "power_in"))
    )
    (net (code "52") (name "Net-(D10-C)") (class "Default")
      (node (ref "C132") (pin "1") (pinfunction "1_1") (pintype "passive"))
      (node (ref "D10") (pin "1") (pinfunction "C_1") (pintype "passive"))
      (node (ref "R131") (pin "2") (pinfunction "2_2") (pintype "passive"))
    )
    (net (code "53") (name "Net-(D11-C)") (class "Default")
      (node (ref "C133") (pin "1") (pinfunction "1_1") (pintype "passive"))
      (node (ref "C134") (pin "1") (pinfunction "1_1") (pintype "passive"))
      (node (ref "C140") (pin "1") (pinfunction "1_1") (pintype "passive"))
      (node (ref "D11") (pin "HEAT_SINK") (pinfunction "C_HEAT_SINK") (pintype "passive"))
      (node (ref "D9") (pin "HEAT_SINK") (pinfunction "C_HEAT_SINK") (pintype "passive"))
      (node (ref "Q3") (pin "8") (pinfunction "D2_8") (pintype "passive"))
      (node (ref "Q3") (pin "PAD78") (pinfunction "D_PAD78") (pintype "passive"))
      (node (ref "R127") (pin "2") (pinfunction "2_2") (pintype "passive"))
      (node (ref "R128") (pin "2") (pinfunction "2_2") (pintype "passive"))
    )
    (net (code "54") (name "Net-(L1-Pad1)") (class "Default")
      (node (ref "L1") (pin "1") (pinfunction "1_1") (pintype "passive"))
      (node (ref "U44") (pin "1") (pinfunction "SW_1") (pintype "bidirectional"))
      (node (ref "U44") (pin "2") (pinfunction "SW_2") (pintype "bidirectional"))
      (node (ref "U44") (pin "3") (pinfunction "SW_3") (pintype "bidirectional"))
    )
    (net (code "55") (name "Net-(L2-Pad1)") (class "Default")
      (node (ref "L2") (pin "1") (pinfunction "1_1") (pintype "passive"))
      (node (ref "U47") (pin "1") (pinfunction "SW_1") (pintype "bidirectional"))
      (node (ref "U47") (pin "2") (pinfunction "SW_2") (pintype "bidirectional"))
      (node (ref "U47") (pin "3") (pinfunction "SW_3") (pintype "bidirectional"))
    )
    (net (code "56") (name "Net-(Q3A-G)") (class "Default")
      (node (ref "Q3") (pin "2") (pinfunction "G_2") (pintype "passive"))
      (node (ref "U53") (pin "15") (pinfunction "HIDRV_15") (pintype "output"))
    )
    (net (code "57") (name "Net-(Q3A-S)") (class "Default")
      (node (ref "C132") (pin "2") (pinfunction "2_2") (pintype "passive"))
      (node (ref "C135") (pin "1") (pinfunction "1_1") (pintype "passive"))
      (node (ref "L5") (pin "1") (pinfunction "1_1") (pintype "passive"))
      (node (ref "Q3") (pin "1") (pinfunction "S_1") (pintype "passive"))
      (node (ref "Q3") (pin "5") (pinfunction "D2_5") (pintype "passive"))
      (node (ref "Q3") (pin "PAD56") (pinfunction "D_PAD56") (pintype "passive"))
      (node (ref "U53") (pin "14") (pinfunction "PH_14") (pintype "power_in"))
    )
    (net (code "58") (name "Net-(Q3B-G)") (class "Default")
      (node (ref "Q3") (pin "4") (pinfunction "G_4") (pintype "passive"))
      (node (ref "U53") (pin "13") (pinfunction "LODRV_13") (pintype "output"))
    )
    (net (code "59") (name "Net-(R45-Pad1)") (class "Default")
      (node (ref "R45") (pin "1") (pinfunction "1_1") (pintype "passive"))
      (node (ref "U17") (pin "5") (pinfunction "D_5") (pintype "passive"))
      (node (ref "U17") (pin "6") (pinfunction "D_6") (pintype "passive"))
    )
    (net (code "60") (name "Net-(R54-Pad1)") (class "Default")
      (node (ref "R54") (pin "1") (pinfunction "1_1") (pintype "passive"))
      (node (ref "U22") (pin "5") (pinfunction "D_5") (pintype "passive"))
      (node (ref "U22") (pin "6") (pinfunction "D_6") (pintype "passive"))
    )
    (net (code "61") (name "Net-(R63-Pad1)") (class "Default")
      (node (ref "R63") (pin "1") (pinfunction "1_1") (pintype "passive"))
      (node (ref "U27") (pin "5") (pinfunction "D_5") (pintype "passive"))
      (node (ref "U27") (pin "6") (pinfunction "D_6") (pintype "passive"))
    )
    (net (code "62") (name "Net-(R72-Pad1)") (class "Default")
      (node (ref "R72") (pin "1") (pinfunction "1_1") (pintype "passive"))
      (node (ref "U32") (pin "5") (pinfunction "D_5") (pintype "passive"))
      (node (ref "U32") (pin "6") (pinfunction "D_6") (pintype "passive"))
    )
    (net (code "63") (name "Net-(R81-Pad1)") (class "Default")
      (node (ref "R81") (pin "1") (pinfunction "1_1") (pintype "passive"))
      (node (ref "U37") (pin "5") (pinfunction "D_5") (pintype "passive"))
      (node (ref "U37") (pin "6") (pinfunction "D_6") (pintype "passive"))
    )
    (net (code "64") (name "Net-(R90-Pad1)") (class "Default")
      (node (ref "R90") (pin "1") (pinfunction "1_1") (pintype "passive"))
      (node (ref "U42") (pin "7") (pinfunction "D_7") (pintype "passive"))
      (node (ref "U42") (pin "8") (pinfunction "D_8") (pintype "passive"))
    )
    (net (code "65") (name "Net-(R101-Pad1)") (class "Default")
      (node (ref "R101") (pin "1") (pinfunction "1_1") (pintype "passive"))
      (node (ref "U45") (pin "7") (pinfunction "D_7") (pintype "passive"))
      (node (ref "U45") (pin "8") (pinfunction "D_8") (pintype "passive"))
    )
    (net (code "66") (name "Net-(R102-Pad2)") (class "Default")
      (node (ref "R102") (pin "2") (pinfunction "2_2") (pintype "passive"))
      (node (ref "R103") (pin "2") (pinfunction "2_2") (pintype "passive"))
      (node (ref "R141") (pin "1") (pinfunction "1_1") (pintype "passive"))
    )
    (net (code "67") (name "Net-(R108-Pad1)") (class "Default")
      (node (ref "R108") (pin "1") (pinfunction "1_1") (pintype "passive"))
      (node (ref "U48") (pin "7") (pinfunction "D_7") (pintype "passive"))
      (node (ref "U48") (pin "8") (pinfunction "D_8") (pintype "passive"))
    )
    (net (code "68") (name "Net-(R122-Pad2)") (class "Default")
      (node (ref "R122") (pin "2") (pinfunction "2_2") (pintype "passive"))
      (node (ref "R123") (pin "2") (pinfunction "2_2") (pintype "passive"))
      (node (ref "R124") (pin "1") (pinfunction "1_1") (pintype "passive"))
      (node (ref "R125") (pin "1") (pinfunction "1_1") (pintype "passive"))
    )
    (net (code "69") (name "Net-(R140-Pad1)") (class "Default")
      (node (ref "R140") (pin "1") (pinfunction "1_1") (pintype "passive"))
      (node (ref "R95") (pin "2") (pinfunction "2_2") (pintype "passive"))
      (node (ref "R96") (pin "2") (pinfunction "2_2") (pintype "passive"))
    )
    (net (code "70") (name "Net-(U1-OUT)") (class "Default")
      (node (ref "R3") (pin "2") (pinfunction "2_2") (pintype "passive"))
      (node (ref "U1") (pin "6") (pinfunction "OUT_6") (pintype "bidirectional"))
    )
    (net (code "71") (name "Net-(U2-OUT)") (class "Default")
      (node (ref "R4") (pin "2") (pinfunction "2_2") (pintype "passive"))
      (node (ref "U2") (pin "6") (pinfunction "OUT_6") (pintype "bidirectional"))
    )
    (net (code "72") (name "Net-(U3-OUT)") (class "Default")
      (node (ref "R7") (pin "2") (pinfunction "2_2") (pintype "passive"))
      (node (ref "U3") (pin "6") (pinfunction "OUT_6") (pintype "bidirectional"))
    )
    (net (code "73") (name "Net-(U4-OUT)") (class "Default")
      (node (ref "R8") (pin "2") (pinfunction "2_2") (pintype "passive"))
      (node (ref "U4") (pin "6") (pinfunction "OUT_6") (pintype "bidirectional"))
    )
    (net (code "74") (name "Net-(U5-OUT)") (class "Default")
      (node (ref "R11") (pin "2") (pinfunction "2_2") (pintype "passive"))
      (node (ref "U5") (pin "6") (pinfunction "OUT_6") (pintype "bidirectional"))
    )
    (net (code "75") (name "Net-(U6-OUT)") (class "Default")
      (node (ref "R12") (pin "2") (pinfunction "2_2") (pintype "passive"))
      (node (ref "U6") (pin "6") (pinfunction "OUT_6") (pintype "bidirectional"))
    )
    (net (code "76") (name "Net-(U7-OUT)") (class "Default")
      (node (ref "R14") (pin "2") (pinfunction "2_2") (pintype "passive"))
      (node (ref "U7") (pin "6") (pinfunction "OUT_6") (pintype "bidirectional"))
    )
    (net (code "77") (name "Net-(U8-OUT)") (class "Default")
      (node (ref "R17") (pin "2") (pinfunction "2_2") (pintype "passive"))
      (node (ref "U8") (pin "6") (pinfunction "OUT_6") (pintype "bidirectional"))
    )
    (net (code "78") (name "Net-(U9-OUT)") (class "Default")
      (node (ref "R18") (pin "2") (pinfunction "2_2") (pintype "passive"))
      (node (ref "U9") (pin "6") (pinfunction "OUT_6") (pintype "bidirectional"))
    )
    (net (code "79") (name "Net-(U10-OUT)") (class "Default")
      (node (ref "R21") (pin "2") (pinfunction "2_2") (pintype "passive"))
      (node (ref "U10") (pin "6") (pinfunction "OUT_6") (pintype "bidirectional"))
    )
    (net (code "80") (name "Net-(U11-OUT)") (class "Default")
      (node (ref "R22") (pin "2") (pinfunction "2_2") (pintype "passive"))
      (node (ref "U11") (pin "6") (pinfunction "OUT_6") (pintype "bidirectional"))
    )
    (net (code "81") (name "Net-(U12-OUT)") (class "Default")
      (node (ref "R24") (pin "2") (pinfunction "2_2") (pintype "passive"))
      (node (ref "U12") (pin "6") (pinfunction "OUT_6") (pintype "bidirectional"))
    )
    (net (code "82") (name "Net-(U13A-OUT)") (class "Default")
      (node (ref "R41") (pin "1") (pinfunction "1_1") (pintype "passive"))
      (node (ref "U13") (pin "1") (pinfunction "OUT_1") (pintype "output"))
    )
    (net (code "83") (name "Net-(U16-D)") (class "Default")
      (node (ref "C35") (pin "1") (pinfunction "1_1") (pintype "passive"))
      (node (ref "R41") (pin "2") (pinfunction "2_2") (pintype "passive"))
      (node (ref "U16") (pin "3") (pinfunction "D_3") (pintype "bidirectional"))
    )
    (net (code "84") (name "Net-(U17A-G)") (class "Default")
      (node (ref "C39") (pin "1") (pinfunction "1_1") (pintype "passive"))
      (node (ref "R44") (pin "1") (pinfunction "1_1") (pintype "passive"))
      (node (ref "R45") (pin "2") (pinfunction "2_2") (pintype "passive"))
      (node (ref "U17") (pin "2") (pinfunction "G_2") (pintype "passive"))
    )
    (net (code "85") (name "Net-(U18A-OUT)") (class "Default")
      (node (ref "R50") (pin "1") (pinfunction "1_1") (pintype "passive"))
      (node (ref "U18") (pin "1") (pinfunction "OUT_1") (pintype "output"))
    )
    (net (code "86") (name "Net-(U21-D)") (class "Default")
      (node (ref "C46") (pin "1") (pinfunction "1_1") (pintype "passive"))
      (node (ref "R50") (pin "2") (pinfunction "2_2") (pintype "passive"))
      (node (ref "U21") (pin "3") (pinfunction "D_3") (pintype "bidirectional"))
    )
    (net (code "87") (name "Net-(U22A-G)") (class "Default")
      (node (ref "C50") (pin "1") (pinfunction "1_1") (pintype "passive"))
      (node (ref "R53") (pin "1") (pinfunction "1_1") (pintype "passive"))
      (node (ref "R54") (pin "2") (pinfunction "2_2") (pintype "passive"))
      (node (ref "U22") (pin "2") (pinfunction "G_2") (pintype "passive"))
    )
    (net (code "88") (name "Net-(U23A-OUT)") (class "Default")
      (node (ref "R59") (pin "1") (pinfunction "1_1") (pintype "passive"))
      (node (ref "U23") (pin "1") (pinfunction "OUT_1") (pintype "output"))
    )
    (net (code "89") (name "Net-(U26-D)") (class "Default")
      (node (ref "C57") (pin "1") (pinfunction "1_1") (pintype "passive"))
      (node (ref "R59") (pin "2") (pinfunction "2_2") (pintype "passive"))
      (node (ref "U26") (pin "3") (pinfunction "D_3") (pintype "bidirectional"))
    )
    (net (code "90") (name "Net-(U27A-G)") (class "Default")
      (node (ref "C61") (pin "1") (pinfunction "1_1") (pintype "passive"))
      (node (ref "R62") (pin "1") (pinfunction "1_1") (pintype "passive"))
      (node (ref "R63") (pin "2") (pinfunction "2_2") (pintype "passive"))
      (node (ref "U27") (pin "2") (pinfunction "G_2") (pintype "passive"))
    )
    (net (code "91") (name "Net-(U28A-OUT)") (class "Default")
      (node (ref "R68") (pin "1") (pinfunction "1_1") (pintype "passive"))
      (node (ref "U28") (pin "1") (pinfunction "OUT_1") (pintype "output"))
    )
    (net (code "92") (name "Net-(U31-D)") (class "Default")
      (node (ref "C68") (pin "1") (pinfunction "1_1") (pintype "passive"))
      (node (ref "R68") (pin "2") (pinfunction "2_2") (pintype "passive"))
      (node (ref "U31") (pin "3") (pinfunction "D_3") (pintype "bidirectional"))
    )
    (net (code "93") (name "Net-(U32A-G)") (class "Default")
      (node (ref "C72") (pin "1") (pinfunction "1_1") (pintype "passive"))
      (node (ref "R71") (pin "1") (pinfunction "1_1") (pintype "passive"))
      (node (ref "R72") (pin "2") (pinfunction "2_2") (pintype "passive"))
      (node (ref "U32") (pin "2") (pinfunction "G_2") (pintype "passive"))
    )
    (net (code "94") (name "Net-(U33A-OUT)") (class "Default")
      (node (ref "R77") (pin "1") (pinfunction "1_1") (pintype "passive"))
      (node (ref "U33") (pin "1") (pinfunction "OUT_1") (pintype "output"))
    )
    (net (code "95") (name "Net-(U36-D)") (class "Default")
      (node (ref "C79") (pin "1") (pinfunction "1_1") (pintype "passive"))
      (node (ref "R77") (pin "2") (pinfunction "2_2") (pintype "passive"))
      (node (ref "U36") (pin "3") (pinfunction "D_3") (pintype "bidirectional"))
    )
    (net (code "96") (name "Net-(U37A-G)") (class "Default")
      (node (ref "C83") (pin "1") (pinfunction "1_1") (pintype "passive"))
      (node (ref "R80") (pin "1") (pinfunction "1_1") (pintype "passive"))
      (node (ref "R81") (pin "2") (pinfunction "2_2") (pintype "passive"))
      (node (ref "U37") (pin "2") (pinfunction "G_2") (pintype "passive"))
    )
    (net (code "97") (name "Net-(U38A-OUT)") (class "Default")
      (node (ref "R86") (pin "1") (pinfunction "1_1") (pintype "passive"))
      (node (ref "U38") (pin "1") (pinfunction "OUT_1") (pintype "output"))
    )
    (net (code "98") (name "Net-(U41-D)") (class "Default")
      (node (ref "C90") (pin "1") (pinfunction "1_1") (pintype "passive"))
      (node (ref "R86") (pin "2") (pinfunction "2_2") (pintype "passive"))
      (node (ref "U41") (pin "3") (pinfunction "D_3") (pintype "bidirectional"))
    )
    (net (code "99") (name "Net-(U42A-G)") (class "Default")
      (node (ref "R89") (pin "2") (pinfunction "2_2") (pintype "passive"))
      (node (ref "R90") (pin "2") (pinfunction "2_2") (pintype "passive"))
      (node (ref "U42") (pin "4") (pinfunction "G_4") (pintype "passive"))
    )
    (net (code "100") (name "Net-(U43A-+IN)") (class "Default")
      (node (ref "R140") (pin "2") (pinfunction "2_2") (pintype "passive"))
      (node (ref "R99") (pin "1") (pinfunction "1_1") (pintype "passive"))
      (node (ref "U43") (pin "3") (pinfunction "+IN_3") (pintype "input"))
    )
    (net (code "101") (name "Net-(U43A--IN)") (class "Default")
      (node (ref "R97") (pin "1") (pinfunction "1_1") (pintype "passive"))
      (node (ref "R98") (pin "2") (pinfunction "2_2") (pintype "passive"))
      (node (ref "U43") (pin "4") (pinfunction "-IN_4") (pintype "input"))
    )
    (net (code "102") (name "Net-(U44-SS{slash}TR)") (class "Default")
      (node (ref "C101") (pin "2") (pinfunction "2_2") (pintype "passive"))
      (node (ref "U44") (pin "9") (pinfunction "SS/TR_9") (pintype "bidirectional"))
    )
    (net (code "103") (name "Net-(U45A-G)") (class "Default")
      (node (ref "R100") (pin "2") (pinfunction "2_2") (pintype "passive"))
      (node (ref "R101") (pin "2") (pinfunction "2_2") (pintype "passive"))
      (node (ref "U45") (pin "4") (pinfunction "G_4") (pintype "passive"))
    )
    (net (code "104") (name "Net-(U46A-+IN)") (class "Default")
      (node (ref "R106") (pin "1") (pinfunction "1_1") (pintype "passive"))
      (node (ref "R141") (pin "2") (pinfunction "2_2") (pintype "passive"))
      (node (ref "U46") (pin "3") (pinfunction "+IN_3") (pintype "input"))
    )
    (net (code "105") (name "Net-(U46A--IN)") (class "Default")
      (node (ref "R104") (pin "1") (pinfunction "1_1") (pintype "passive"))
      (node (ref "R105") (pin "2") (pinfunction "2_2") (pintype "passive"))
      (node (ref "U46") (pin "4") (pinfunction "-IN_4") (pintype "input"))
    )
    (net (code "106") (name "Net-(U47-SS{slash}TR)") (class "Default")
      (node (ref "C108") (pin "2") (pinfunction "2_2") (pintype "passive"))
      (node (ref "U47") (pin "9") (pinfunction "SS/TR_9") (pintype "bidirectional"))
    )
    (net (code "107") (name "Net-(U48A-G)") (class "Default")
      (node (ref "R107") (pin "2") (pinfunction "2_2") (pintype "passive"))
      (node (ref "R108") (pin "2") (pinfunction "2_2") (pintype "passive"))
      (node (ref "U48") (pin "4") (pinfunction "G_4") (pintype "passive"))
    )
    (net (code "108") (name "Net-(U51-ICTRL+)") (class "Default")
      (node (ref "C118") (pin "1") (pinfunction "1_1") (pintype "passive"))
      (node (ref "R112") (pin "2") (pinfunction "2_2") (pintype "passive"))
      (node (ref "U51") (pin "7") (pinfunction "ICTRL+_7") (pintype "bidirectional"))
    )
    (net (code "109") (name "Net-(U51-ICTRL-)") (class "Default")
      (node (ref "C118") (pin "2") (pinfunction "2_2") (pintype "passive"))
      (node (ref "R113") (pin "2") (pinfunction "2_2") (pintype "passive"))
      (node (ref "U51") (pin "6") (pinfunction "ICTRL-_6") (pintype "bidirectional"))
    )
    (net (code "110") (name "Net-(U51-LX)") (class "Default")
      (node (ref "L3") (pin "2") (pinfunction "2_2") (pintype "passive"))
      (node (ref "U51") (pin "3") (pinfunction "LX_3") (pintype "bidirectional"))
    )
    (net (code "111") (name "Net-(U51-MPP-SET)") (class "Default")
      (node (ref "C116") (pin "1") (pinfunction "1_1") (pintype "passive"))
      (node (ref "R110") (pin "2") (pinfunction "2_2") (pintype "passive"))
      (node (ref "U51") (pin "1") (pinfunction "MPP-SET_1") (pintype "bidirectional"))
      (node (ref "U51") (pin "8") (pinfunction "XSHUT_8") (pintype "bidirectional"))
    )
    (net (code "112") (name "Net-(U51-VOUT)") (class "Default")
      (node (ref "C120") (pin "1") (pinfunction "1_1") (pintype "passive"))
      (node (ref "D7") (pin "C") (pinfunction "C_C") (pintype "passive"))
      (node (ref "R112") (pin "1") (pinfunction "1_1") (pintype "passive"))
      (node (ref "R116") (pin "2") (pinfunction "2_2") (pintype "passive"))
      (node (ref "U51") (pin "4") (pinfunction "VOUT_4") (pintype "bidirectional"))
    )
    (net (code "113") (name "Net-(U52-ICTRL+)") (class "Default")
      (node (ref "C119") (pin "1") (pinfunction "1_1") (pintype "passive"))
      (node (ref "R114") (pin "2") (pinfunction "2_2") (pintype "passive"))
      (node (ref "U52") (pin "7") (pinfunction "ICTRL+_7") (pintype "bidirectional"))
    )
    (net (code "114") (name "Net-(U52-ICTRL-)") (class "Default")
      (node (ref "C119") (pin "2") (pinfunction "2_2") (pintype "passive"))
      (node (ref "R115") (pin "2") (pinfunction "2_2") (pintype "passive"))
      (node (ref "U52") (pin "6") (pinfunction "ICTRL-_6") (pintype "bidirectional"))
    )
    (net (code "115") (name "Net-(U52-LX)") (class "Default")
      (node (ref "L4") (pin "2") (pinfunction "2_2") (pintype "passive"))
      (node (ref "U52") (pin "3") (pinfunction "LX_3") (pintype "bidirectional"))
    )
    (net (code "116") (name "Net-(U52-MPP-SET)") (class "Default")
      (node (ref "C117") (pin "1") (pinfunction "1_1") (pintype "passive"))
      (node (ref "R111") (pin "2") (pinfunction "2_2") (pintype "passive"))
      (node (ref "U52") (pin "1") (pinfunction "MPP-SET_1") (pintype "bidirectional"))
      (node (ref "U52") (pin "8") (pinfunction "XSHUT_8") (pintype "bidirectional"))
    )
    (net (code "117") (name "Net-(U52-VOUT)") (class "Default")
      (node (ref "C121") (pin "1") (pinfunction "1_1") (pintype "passive"))
      (node (ref "D8") (pin "C") (pinfunction "C_C") (pintype "passive"))
      (node (ref "R114") (pin "1") (pinfunction "1_1") (pintype "passive"))
      (node (ref "R117") (pin "2") (pinfunction "2_2") (pintype "passive"))
      (node (ref "U52") (pin "4") (pinfunction "VOUT_4") (pintype "bidirectional"))
    )
    (net (code "118") (name "Net-(U53-BTST)") (class "Default")
      (node (ref "R131") (pin "1") (pinfunction "1_1") (pintype "passive"))
      (node (ref "U53") (pin "16") (pinfunction "BTST_16") (pintype "power_in"))
    )
    (net (code "119") (name "Net-(U53-SRN)") (class "Default")
      (node (ref "C129") (pin "2") (pinfunction "2_2") (pintype "passive"))
      (node (ref "R135") (pin "1") (pinfunction "1_1") (pintype "passive"))
      (node (ref "U53") (pin "9") (pinfunction "SRN_9") (pintype "input"))
    )
    (net (code "120") (name "Net-(U53-SRP)") (class "Default")
      (node (ref "C129") (pin "1") (pinfunction "1_1") (pintype "passive"))
      (node (ref "C131") (pin "1") (pinfunction "1_1") (pintype "passive"))
      (node (ref "L5") (pin "2") (pinfunction "2_2") (pintype "passive"))
      (node (ref "R134") (pin "1") (pinfunction "1_1") (pintype "passive"))
      (node (ref "U53") (pin "10") (pinfunction "SRP_10") (pintype "bidirectional"))
    )
    (net (code "121") (name "Net-(U53-VCC)") (class "Default")
      (node (ref "C127") (pin "2") (pinfunction "2_2") (pintype "passive"))
      (node (ref "R127") (pin "1") (pinfunction "1_1") (pintype "passive"))
      (node (ref "R128") (pin "1") (pinfunction "1_1") (pintype "passive"))
      (node (ref "U53") (pin "1") (pinfunction "VCC_1") (pintype "power_in"))
    )
    (net (code "122") (name "Net-(U53-VFB)") (class "Default")
      (node (ref "C141") (pin "2") (pinfunction "2_2") (pintype "passive"))
      (node (ref "R138") (pin "1") (pinfunction "1_1") (pintype "passive"))
      (node (ref "R139") (pin "2") (pinfunction "2_2") (pintype "passive"))
      (node (ref "U53") (pin "8") (pinfunction "VFB_8") (pintype "input"))
    )
    (net (code "123") (name "Net-(U54-OUT)") (class "Default")
      (node (ref "R136") (pin "2") (pinfunction "2_2") (pintype "passive"))
      (node (ref "U54") (pin "6") (pinfunction "OUT_6") (pintype "bidirectional"))
    )
    (net (code "124") (name "Net-(U55-ICTRL+)") (class "Default")
      (node (ref "C143") (pin "1") (pinfunction "1_1") (pintype "passive"))
      (node (ref "R118") (pin "2") (pinfunction "2_2") (pintype "passive"))
      (node (ref "U55") (pin "7") (pinfunction "ICTRL+_7") (pintype "bidirectional"))
    )
    (net (code "125") (name "Net-(U55-ICTRL-)") (class "Default")
      (node (ref "C143") (pin "2") (pinfunction "2_2") (pintype "passive"))
      (node (ref "R119") (pin "2") (pinfunction "2_2") (pintype "passive"))
      (node (ref "U55") (pin "6") (pinfunction "ICTRL-_6") (pintype "bidirectional"))
    )
    (net (code "126") (name "Net-(U55-LX)") (class "Default")
      (node (ref "L6") (pin "2") (pinfunction "2_2") (pintype "passive"))
      (node (ref "U55") (pin "3") (pinfunction "LX_3") (pintype "bidirectional"))
    )
    (net (code "127") (name "Net-(U55-MPP-SET)") (class "Default")
      (node (ref "C144") (pin "1") (pinfunction "1_1") (pintype "passive"))
      (node (ref "R143") (pin "2") (pinfunction "2_2") (pintype "passive"))
      (node (ref "U55") (pin "1") (pinfunction "MPP-SET_1") (pintype "bidirectional"))
      (node (ref "U55") (pin "8") (pinfunction "XSHUT_8") (pintype "bidirectional"))
    )
    (net (code "128") (name "Net-(U55-VOUT)") (class "Default")
      (node (ref "C147") (pin "1") (pinfunction "1_1") (pintype "passive"))
      (node (ref "D12") (pin "C") (pinfunction "C_C") (pintype "passive"))
      (node (ref "R118") (pin "1") (pinfunction "1_1") (pintype "passive"))
      (node (ref "R142") (pin "2") (pinfunction "2_2") (pintype "passive"))
      (node (ref "U55") (pin "4") (pinfunction "VOUT_4") (pintype "bidirectional"))
    )
    (net (code "129") (name "Net-(U56-ICTRL+)") (class "Default")
      (node (ref "C148") (pin "1") (pinfunction "1_1") (pintype "passive"))
      (node (ref "R144") (pin "2") (pinfunction "2_2") (pintype "passive"))
      (node (ref "U56") (pin "7") (pinfunction "ICTRL+_7") (pintype "bidirectional"))
    )
    (net (code "130") (name "Net-(U56-ICTRL-)") (class "Default")
      (node (ref "C148") (pin "2") (pinfunction "2_2") (pintype "passive"))
      (node (ref "R145") (pin "2") (pinfunction "2_2") (pintype "passive"))
      (node (ref "U56") (pin "6") (pinfunction "ICTRL-_6") (pintype "bidirectional"))
    )
    (net (code "131") (name "Net-(U56-LX)") (class "Default")
      (node (ref "L7") (pin "2") (pinfunction "2_2") (pintype "passive"))
      (node (ref "U56") (pin "3") (pinfunction "LX_3") (pintype "bidirectional"))
    )
    (net (code "132") (name "Net-(U56-MPP-SET)") (class "Default")
      (node (ref "C149") (pin "1") (pinfunction "1_1") (pintype "passive"))
      (node (ref "R147") (pin "2") (pinfunction "2_2") (pintype "passive"))
      (node (ref "U56") (pin "1") (pinfunction "MPP-SET_1") (pintype "bidirectional"))
      (node (ref "U56") (pin "8") (pinfunction "XSHUT_8") (pintype "bidirectional"))
    )
    (net (code "133") (name "Net-(U56-VOUT)") (class "Default")
      (node (ref "C152") (pin "1") (pinfunction "1_1") (pintype "passive"))
      (node (ref "D13") (pin "C") (pinfunction "C_C") (pintype "passive"))
      (node (ref "R144") (pin "1") (pinfunction "1_1") (pintype "passive"))
      (node (ref "R146") (pin "2") (pinfunction "2_2") (pintype "passive"))
      (node (ref "U56") (pin "4") (pinfunction "VOUT_4") (pintype "bidirectional"))
    )
    (net (code "134") (name "Net-(U57-ICTRL+)") (class "Default")
      (node (ref "C153") (pin "1") (pinfunction "1_1") (pintype "passive"))
      (node (ref "R148") (pin "2") (pinfunction "2_2") (pintype "passive"))
      (node (ref "U57") (pin "7") (pinfunction "ICTRL+_7") (pintype "bidirectional"))
    )
    (net (code "135") (name "Net-(U57-ICTRL-)") (class "Default")
      (node (ref "C153") (pin "2") (pinfunction "2_2") (pintype "passive"))
      (node (ref "R149") (pin "2") (pinfunction "2_2") (pintype "passive"))
      (node (ref "U57") (pin "6") (pinfunction "ICTRL-_6") (pintype "bidirectional"))
    )
    (net (code "136") (name "Net-(U57-LX)") (class "Default")
      (node (ref "L8") (pin "2") (pinfunction "2_2") (pintype "passive"))
      (node (ref "U57") (pin "3") (pinfunction "LX_3") (pintype "bidirectional"))
    )
    (net (code "137") (name "Net-(U57-MPP-SET)") (class "Default")
      (node (ref "C154") (pin "1") (pinfunction "1_1") (pintype "passive"))
      (node (ref "R151") (pin "2") (pinfunction "2_2") (pintype "passive"))
      (node (ref "U57") (pin "1") (pinfunction "MPP-SET_1") (pintype "bidirectional"))
      (node (ref "U57") (pin "8") (pinfunction "XSHUT_8") (pintype "bidirectional"))
    )
    (net (code "138") (name "Net-(U57-VOUT)") (class "Default")
      (node (ref "C157") (pin "1") (pinfunction "1_1") (pintype "passive"))
      (node (ref "D14") (pin "C") (pinfunction "C_C") (pintype "passive"))
      (node (ref "R148") (pin "1") (pinfunction "1_1") (pintype "passive"))
      (node (ref "R150") (pin "2") (pinfunction "2_2") (pintype "passive"))
      (node (ref "U57") (pin "4") (pinfunction "VOUT_4") (pintype "bidirectional"))
    )
    (net (code "139") (name "Net-(U58-ICTRL+)") (class "Default")
      (node (ref "C158") (pin "1") (pinfunction "1_1") (pintype "passive"))
      (node (ref "R152") (pin "2") (pinfunction "2_2") (pintype "passive"))
      (node (ref "U58") (pin "7") (pinfunction "ICTRL+_7") (pintype "bidirectional"))
    )
    (net (code "140") (name "Net-(U58-ICTRL-)") (class "Default")
      (node (ref "C158") (pin "2") (pinfunction "2_2") (pintype "passive"))
      (node (ref "R153") (pin "2") (pinfunction "2_2") (pintype "passive"))
      (node (ref "U58") (pin "6") (pinfunction "ICTRL-_6") (pintype "bidirectional"))
    )
    (net (code "141") (name "Net-(U58-LX)") (class "Default")
      (node (ref "L9") (pin "2") (pinfunction "2_2") (pintype "passive"))
      (node (ref "U58") (pin "3") (pinfunction "LX_3") (pintype "bidirectional"))
    )
    (net (code "142") (name "Net-(U58-MPP-SET)") (class "Default")
      (node (ref "C159") (pin "1") (pinfunction "1_1") (pintype "passive"))
      (node (ref "R155") (pin "2") (pinfunction "2_2") (pintype "passive"))
      (node (ref "U58") (pin "1") (pinfunction "MPP-SET_1") (pintype "bidirectional"))
      (node (ref "U58") (pin "8") (pinfunction "XSHUT_8") (pintype "bidirectional"))
    )
    (net (code "143") (name "Net-(U58-VOUT)") (class "Default")
      (node (ref "C162") (pin "1") (pinfunction "1_1") (pintype "passive"))
      (node (ref "D15") (pin "C") (pinfunction "C_C") (pintype "passive"))
      (node (ref "R152") (pin "1") (pinfunction "1_1") (pintype "passive"))
      (node (ref "R154") (pin "2") (pinfunction "2_2") (pintype "passive"))
      (node (ref "U58") (pin "4") (pinfunction "VOUT_4") (pintype "bidirectional"))
    )
    (net (code "144") (name "Net-(X1-1)") (class "Default")
      (node (ref "U49") (pin "3") (pinfunction "3_3") (pintype "bidirectional"))
      (node (ref "X1") (pin "P$1") (pinfunction "1_P$1") (pintype "passive"))
    )
    (net (code "145") (name "Net-(X1-2)") (class "Default")
      (node (ref "U49") (pin "2") (pinfunction "2_2") (pintype "bidirectional"))
      (node (ref "X1") (pin "P$2") (pinfunction "2_P$2") (pintype "passive"))
    )
    (net (code "146") (name "OCP1_COMP_OUT") (class "Default")
      (node (ref "C38") (pin "2") (pinfunction "2_2") (pintype "passive"))
      (node (ref "R40") (pin "2") (pinfunction "2_2") (pintype "passive"))
      (node (ref "TP12") (pin "TP") (pinfunction "TP_TP") (pintype "input"))
      (node (ref "U15") (pin "1") (pinfunction "A_1") (pintype "bidirectional"))
      (node (ref "U16") (pin "4") (pinfunction "Q_4") (pintype "bidirectional"))
    )
    (net (code "147") (name "OCP1_CSENSE") (class "Default")
      (node (ref "R42") (pin "2") (pinfunction "2_2") (pintype "passive"))
      (node (ref "U13") (pin "4") (pinfunction "-IN_4") (pintype "input"))
      (node (ref "U14") (pin "6") (pinfunction "OUT_6") (pintype "bidirectional"))
    )
    (net (code "148") (name "OCP1_CSENSE_MUX") (class "Default")
      (node (ref "C36") (pin "1") (pinfunction "1_1") (pintype "passive"))
      (node (ref "R42") (pin "1") (pinfunction "1_1") (pintype "passive"))
      (node (ref "U50") (pin "38") (pinfunction "S30_38") (pintype "bidirectional"))
    )
    (net (code "149") (name "OCP1_GATE") (class "Default")
      (node (ref "U15") (pin "4") (pinfunction "Y_4") (pintype "bidirectional"))
      (node (ref "U17") (pin "4") (pinfunction "G_4") (pintype "passive"))
    )
    (net (code "150") (name "OCP1_MCU_EN") (class "Default")
      (node (ref "R40") (pin "1") (pinfunction "1_1") (pintype "passive"))
      (node (ref "TP11") (pin "TP") (pinfunction "TP_TP") (pintype "input"))
      (node (ref "U15") (pin "2") (pinfunction "B_2") (pintype "bidirectional"))
      (node (ref "U49") (pin "23") (pinfunction "23_23") (pintype "bidirectional"))
    )
    (net (code "151") (name "OCP1_SENSEM") (class "Default")
      (node (ref "R39") (pin "2") (pinfunction "2_2") (pintype "passive"))
      (node (ref "U14") (pin "5") (pinfunction "IN-_5") (pintype "bidirectional"))
      (node (ref "U17") (pin "7") (pinfunction "D_7") (pintype "passive"))
      (node (ref "U17") (pin "8") (pinfunction "D_8") (pintype "passive"))
    )
    (net (code "152") (name "OCP1_VSENSE") (class "Default")
      (node (ref "C41") (pin "1") (pinfunction "1_1") (pintype "passive"))
      (node (ref "R46") (pin "1") (pinfunction "1_1") (pintype "passive"))
      (node (ref "R47") (pin "2") (pinfunction "2_2") (pintype "passive"))
      (node (ref "U50") (pin "46") (pinfunction "S15_46") (pintype "bidirectional"))
    )
    (net (code "153") (name "OCP2_COMP_OUT") (class "Default")
      (node (ref "C49") (pin "2") (pinfunction "2_2") (pintype "passive"))
      (node (ref "R49") (pin "2") (pinfunction "2_2") (pintype "passive"))
      (node (ref "TP10") (pin "TP") (pinfunction "TP_TP") (pintype "input"))
      (node (ref "U20") (pin "1") (pinfunction "A_1") (pintype "bidirectional"))
      (node (ref "U21") (pin "4") (pinfunction "Q_4") (pintype "bidirectional"))
    )
    (net (code "154") (name "OCP2_CSENSE") (class "Default")
      (node (ref "R51") (pin "2") (pinfunction "2_2") (pintype "passive"))
      (node (ref "U18") (pin "4") (pinfunction "-IN_4") (pintype "input"))
      (node (ref "U19") (pin "6") (pinfunction "OUT_6") (pintype "bidirectional"))
    )
    (net (code "155") (name "OCP2_CSENSE_MUX") (class "Default")
      (node (ref "C47") (pin "1") (pinfunction "1_1") (pintype "passive"))
      (node (ref "R51") (pin "1") (pinfunction "1_1") (pintype "passive"))
      (node (ref "U50") (pin "48") (pinfunction "S13_48") (pintype "bidirectional"))
    )
    (net (code "156") (name "OCP2_GATE") (class "Default")
      (node (ref "U20") (pin "4") (pinfunction "Y_4") (pintype "bidirectional"))
      (node (ref "U22") (pin "4") (pinfunction "G_4") (pintype "passive"))
    )
    (net (code "157") (name "OCP2_MCU_EN") (class "Default")
      (node (ref "R49") (pin "1") (pinfunction "1_1") (pintype "passive"))
      (node (ref "TP9") (pin "TP") (pinfunction "TP_TP") (pintype "input"))
      (node (ref "U20") (pin "2") (pinfunction "B_2") (pintype "bidirectional"))
      (node (ref "U49") (pin "22") (pinfunction "22_22") (pintype "bidirectional"))
    )
    (net (code "158") (name "OCP2_SENSEM") (class "Default")
      (node (ref "R48") (pin "2") (pinfunction "2_2") (pintype "passive"))
      (node (ref "U19") (pin "5") (pinfunction "IN-_5") (pintype "bidirectional"))
      (node (ref "U22") (pin "7") (pinfunction "D_7") (pintype "passive"))
      (node (ref "U22") (pin "8") (pinfunction "D_8") (pintype "passive"))
    )
    (net (code "159") (name "OCP2_VSENSE") (class "Default")
      (node (ref "C52") (pin "1") (pinfunction "1_1") (pintype "passive"))
      (node (ref "R55") (pin "1") (pinfunction "1_1") (pintype "passive"))
      (node (ref "R56") (pin "2") (pinfunction "2_2") (pintype "passive"))
      (node (ref "U50") (pin "47") (pinfunction "S14_47") (pintype "bidirectional"))
    )
    (net (code "160") (name "OCP3_COMP_OUT") (class "Default")
      (node (ref "C60") (pin "2") (pinfunction "2_2") (pintype "passive"))
      (node (ref "R58") (pin "2") (pinfunction "2_2") (pintype "passive"))
      (node (ref "TP8") (pin "TP") (pinfunction "TP_TP") (pintype "input"))
      (node (ref "U25") (pin "1") (pinfunction "A_1") (pintype "bidirectional"))
      (node (ref "U26") (pin "4") (pinfunction "Q_4") (pintype "bidirectional"))
    )
    (net (code "161") (name "OCP3_CSENSE") (class "Default")
      (node (ref "R60") (pin "2") (pinfunction "2_2") (pintype "passive"))
      (node (ref "U23") (pin "4") (pinfunction "-IN_4") (pintype "input"))
      (node (ref "U24") (pin "6") (pinfunction "OUT_6") (pintype "bidirectional"))
    )
    (net (code "162") (name "OCP3_CSENSE_MUX") (class "Default")
      (node (ref "C58") (pin "1") (pinfunction "1_1") (pintype "passive"))
      (node (ref "R60") (pin "1") (pinfunction "1_1") (pintype "passive"))
      (node (ref "U50") (pin "4") (pinfunction "S9_4") (pintype "bidirectional"))
    )
    (net (code "163") (name "OCP3_GATE") (class "Default")
      (node (ref "U25") (pin "4") (pinfunction "Y_4") (pintype "bidirectional"))
      (node (ref "U27") (pin "4") (pinfunction "G_4") (pintype "passive"))
    )
    (net (code "164") (name "OCP3_MCU_EN") (class "Default")
      (node (ref "R58") (pin "1") (pinfunction "1_1") (pintype "passive"))
      (node (ref "TP7") (pin "TP") (pinfunction "TP_TP") (pintype "input"))
      (node (ref "U25") (pin "2") (pinfunction "B_2") (pintype "bidirectional"))
      (node (ref "U49") (pin "21") (pinfunction "21_21") (pintype "bidirectional"))
    )
    (net (code "165") (name "OCP3_SENSEM") (class "Default")
      (node (ref "R57") (pin "2") (pinfunction "2_2") (pintype "passive"))
      (node (ref "U24") (pin "5") (pinfunction "IN-_5") (pintype "bidirectional"))
      (node (ref "U27") (pin "7") (pinfunction "D_7") (pintype "passive"))
      (node (ref "U27") (pin "8") (pinfunction "D_8") (pintype "passive"))
    )
    (net (code "166") (name "OCP3_VSENSE") (class "Default")
      (node (ref "C63") (pin "1") (pinfunction "1_1") (pintype "passive"))
      (node (ref "R64") (pin "1") (pinfunction "1_1") (pintype "passive"))
      (node (ref "R65") (pin "2") (pinfunction "2_2") (pintype "passive"))
      (node (ref "U50") (pin "3") (pinfunction "S10_3") (pintype "bidirectional"))
    )
    (net (code "167") (name "OCP4_COMP_OUT") (class "Default")
      (node (ref "C71") (pin "2") (pinfunction "2_2") (pintype "passive"))
      (node (ref "R67") (pin "2") (pinfunction "2_2") (pintype "passive"))
      (node (ref "TP6") (pin "TP") (pinfunction "TP_TP") (pintype "input"))
      (node (ref "U30") (pin "1") (pinfunction "A_1") (pintype "bidirectional"))
      (node (ref "U31") (pin "4") (pinfunction "Q_4") (pintype "bidirectional"))
    )
    (net (code "168") (name "OCP4_CSENSE") (class "Default")
      (node (ref "R69") (pin "2") (pinfunction "2_2") (pintype "passive"))
      (node (ref "U28") (pin "4") (pinfunction "-IN_4") (pintype "input"))
      (node (ref "U29") (pin "6") (pinfunction "OUT_6") (pintype "bidirectional"))
    )
    (net (code "169") (name "OCP4_CSENSE_MUX") (class "Default")
      (node (ref "C69") (pin "1") (pinfunction "1_1") (pintype "passive"))
      (node (ref "R69") (pin "1") (pinfunction "1_1") (pintype "passive"))
      (node (ref "U50") (pin "7") (pinfunction "S6_7") (pintype "bidirectional"))
    )
    (net (code "170") (name "OCP4_GATE") (class "Default")
      (node (ref "U30") (pin "4") (pinfunction "Y_4") (pintype "bidirectional"))
      (node (ref "U32") (pin "4") (pinfunction "G_4") (pintype "passive"))
    )
    (net (code "171") (name "OCP4_MCU_EN") (class "Default")
      (node (ref "R67") (pin "1") (pinfunction "1_1") (pintype "passive"))
      (node (ref "TP5") (pin "TP") (pinfunction "TP_TP") (pintype "input"))
      (node (ref "U30") (pin "2") (pinfunction "B_2") (pintype "bidirectional"))
      (node (ref "U49") (pin "26") (pinfunction "26_26") (pintype "bidirectional"))
    )
    (net (code "172") (name "OCP4_SENSEM") (class "Default")
      (node (ref "R66") (pin "2") (pinfunction "2_2") (pintype "passive"))
      (node (ref "U29") (pin "5") (pinfunction "IN-_5") (pintype "bidirectional"))
      (node (ref "U32") (pin "7") (pinfunction "D_7") (pintype "passive"))
      (node (ref "U32") (pin "8") (pinfunction "D_8") (pintype "passive"))
    )
    (net (code "173") (name "OCP4_VSENSE") (class "Default")
      (node (ref "C74") (pin "1") (pinfunction "1_1") (pintype "passive"))
      (node (ref "R73") (pin "1") (pinfunction "1_1") (pintype "passive"))
      (node (ref "R74") (pin "2") (pinfunction "2_2") (pintype "passive"))
      (node (ref "U50") (pin "6") (pinfunction "S7_6") (pintype "bidirectional"))
    )
    (net (code "174") (name "OCP5_COMP_OUT") (class "Default")
      (node (ref "C82") (pin "2") (pinfunction "2_2") (pintype "passive"))
      (node (ref "R76") (pin "2") (pinfunction "2_2") (pintype "passive"))
      (node (ref "TP4") (pin "TP") (pinfunction "TP_TP") (pintype "input"))
      (node (ref "U35") (pin "1") (pinfunction "A_1") (pintype "bidirectional"))
      (node (ref "U36") (pin "4") (pinfunction "Q_4") (pintype "bidirectional"))
    )
    (net (code "175") (name "OCP5_CSENSE") (class "Default")
      (node (ref "R78") (pin "2") (pinfunction "2_2") (pintype "passive"))
      (node (ref "U33") (pin "4") (pinfunction "-IN_4") (pintype "input"))
      (node (ref "U34") (pin "6") (pinfunction "OUT_6") (pintype "bidirectional"))
    )
    (net (code "176") (name "OCP5_CSENSE_MUX") (class "Default")
      (node (ref "C80") (pin "1") (pinfunction "1_1") (pintype "passive"))
      (node (ref "R78") (pin "1") (pinfunction "1_1") (pintype "passive"))
      (node (ref "U50") (pin "10") (pinfunction "S3_10") (pintype "bidirectional"))
    )
    (net (code "177") (name "OCP5_GATE") (class "Default")
      (node (ref "U35") (pin "4") (pinfunction "Y_4") (pintype "bidirectional"))
      (node (ref "U37") (pin "4") (pinfunction "G_4") (pintype "passive"))
    )
    (net (code "178") (name "OCP5_MCU_EN") (class "Default")
      (node (ref "R76") (pin "1") (pinfunction "1_1") (pintype "passive"))
      (node (ref "TP3") (pin "TP") (pinfunction "TP_TP") (pintype "input"))
      (node (ref "U35") (pin "2") (pinfunction "B_2") (pintype "bidirectional"))
      (node (ref "U49") (pin "25") (pinfunction "25_25") (pintype "bidirectional"))
    )
    (net (code "179") (name "OCP5_SENSEM") (class "Default")
      (node (ref "R75") (pin "2") (pinfunction "2_2") (pintype "passive"))
      (node (ref "U34") (pin "5") (pinfunction "IN-_5") (pintype "bidirectional"))
      (node (ref "U37") (pin "7") (pinfunction "D_7") (pintype "passive"))
      (node (ref "U37") (pin "8") (pinfunction "D_8") (pintype "passive"))
    )
    (net (code "180") (name "OCP5_VSENSE") (class "Default")
      (node (ref "C85") (pin "1") (pinfunction "1_1") (pintype "passive"))
      (node (ref "R82") (pin "1") (pinfunction "1_1") (pintype "passive"))
      (node (ref "R83") (pin "2") (pinfunction "2_2") (pintype "passive"))
      (node (ref "U50") (pin "5") (pinfunction "S8_5") (pintype "bidirectional"))
    )
    (net (code "181") (name "OCP6_COMP_OUT") (class "Default")
      (node (ref "C93") (pin "2") (pinfunction "2_2") (pintype "passive"))
      (node (ref "R85") (pin "2") (pinfunction "2_2") (pintype "passive"))
      (node (ref "TP2") (pin "TP") (pinfunction "TP_TP") (pintype "input"))
      (node (ref "U40") (pin "1") (pinfunction "A_1") (pintype "bidirectional"))
      (node (ref "U41") (pin "4") (pinfunction "Q_4") (pintype "bidirectional"))
    )
    (net (code "182") (name "OCP6_CSENSE") (class "Default")
      (node (ref "R87") (pin "2") (pinfunction "2_2") (pintype "passive"))
      (node (ref "U38") (pin "4") (pinfunction "-IN_4") (pintype "input"))
      (node (ref "U39") (pin "6") (pinfunction "OUT_6") (pintype "bidirectional"))
    )
    (net (code "183") (name "OCP6_CSENSE_MUX") (class "Default")
      (node (ref "C91") (pin "1") (pinfunction "1_1") (pintype "passive"))
      (node (ref "R87") (pin "1") (pinfunction "1_1") (pintype "passive"))
      (node (ref "U50") (pin "9") (pinfunction "S4_9") (pintype "bidirectional"))
    )
    (net (code "184") (name "OCP6_GATE") (class "Default")
      (node (ref "U40") (pin "4") (pinfunction "Y_4") (pintype "bidirectional"))
      (node (ref "U42") (pin "2") (pinfunction "G_2") (pintype "passive"))
    )
    (net (code "185") (name "OCP6_MCU_EN") (class "Default")
      (node (ref "R85") (pin "1") (pinfunction "1_1") (pintype "passive"))
      (node (ref "TP1") (pin "TP") (pinfunction "TP_TP") (pintype "input"))
      (node (ref "U40") (pin "2") (pinfunction "B_2") (pintype "bidirectional"))
      (node (ref "U49") (pin "24") (pinfunction "24_24") (pintype "bidirectional"))
    )
    (net (code "186") (name "OCP6_SENSEM") (class "Default")
      (node (ref "R84") (pin "2") (pinfunction "2_2") (pintype "passive"))
      (node (ref "R89") (pin "1") (pinfunction "1_1") (pintype "passive"))
      (node (ref "U39") (pin "5") (pinfunction "IN-_5") (pintype "bidirectional"))
      (node (ref "U42") (pin "3") (pinfunction "S_3") (pintype "passive"))
    )
    (net (code "187") (name "OCP6_VSENSE") (class "Default")
      (node (ref "C94") (pin "1") (pinfunction "1_1") (pintype "passive"))
      (node (ref "R91") (pin "1") (pinfunction "1_1") (pintype "passive"))
      (node (ref "R92") (pin "2") (pinfunction "2_2") (pintype "passive"))
      (node (ref "U50") (pin "8") (pinfunction "S5_8") (pintype "bidirectional"))
    )
    (net (code "188") (name "OCP_COMP_VREF") (class "Default")
      (node (ref "C96") (pin "1") (pinfunction "1_1") (pintype "passive"))
      (node (ref "R93") (pin "1") (pinfunction "1_1") (pintype "passive"))
      (node (ref "R94") (pin "2") (pinfunction "2_2") (pintype "passive"))
      (node (ref "U13") (pin "3") (pinfunction "+IN_3") (pintype "input"))
      (node (ref "U18") (pin "3") (pinfunction "+IN_3") (pintype "input"))
      (node (ref "U23") (pin "3") (pinfunction "+IN_3") (pintype "input"))
      (node (ref "U28") (pin "3") (pinfunction "+IN_3") (pintype "input"))
      (node (ref "U33") (pin "3") (pinfunction "+IN_3") (pintype "input"))
      (node (ref "U38") (pin "3") (pinfunction "+IN_3") (pintype "input"))
    )
    (net (code "189") (name "OEM615_3V3") (class "Default")
      (node (ref "C86") (pin "1") (pinfunction "1_1") (pintype "passive"))
      (node (ref "J1") (pin "5") (pinfunction "5_5") (pintype "passive"))
      (node (ref "R82") (pin "2") (pinfunction "2_2") (pintype "passive"))
      (node (ref "TP23") (pin "TP") (pinfunction "TP_TP") (pintype "input"))
      (node (ref "U37") (pin "1") (pinfunction "S_1") (pintype "passive"))
    )
    (net (code "190") (name "OEM615_LNA_PWR") (class "Default")
      (node (ref "J1") (pin "6") (pinfunction "6_6") (pintype "passive"))
      (node (ref "R91") (pin "2") (pinfunction "2_2") (pintype "passive"))
      (node (ref "TP22") (pin "TP") (pinfunction "TP_TP") (pintype "input"))
      (node (ref "U42") (pin "5") (pinfunction "D_5") (pintype "passive"))
      (node (ref "U42") (pin "6") (pinfunction "D_6") (pintype "passive"))
    )
    (net (code "191") (name "PV_EAST1_CSENSE_MUX") (class "Default")
      (node (ref "C14") (pin "1") (pinfunction "1_1") (pintype "passive"))
      (node (ref "R14") (pin "1") (pinfunction "1_1") (pintype "passive"))
      (node (ref "U50") (pin "40") (pinfunction "S32_40") (pintype "bidirectional"))
    )
    (net (code "192") (name "PV_EAST1_P") (class "Default")
      (node (ref "J2") (pin "15") (pinfunction "15_15") (pintype "passive"))
      (node (ref "R13") (pin "1") (pinfunction "1_1") (pintype "passive"))
      (node (ref "U7") (pin "4") (pinfunction "IN+_4") (pintype "bidirectional"))
    )
    (net (code "193") (name "PV_EAST2_CSENSE_MUX") (class "Default")
      (node (ref "C24") (pin "1") (pinfunction "1_1") (pintype "passive"))
      (node (ref "R24") (pin "1") (pinfunction "1_1") (pintype "passive"))
      (node (ref "U50") (pin "39") (pinfunction "S31_39") (pintype "bidirectional"))
    )
    (net (code "194") (name "PV_EAST2_P") (class "Default")
      (node (ref "J2") (pin "18") (pinfunction "18_18") (pintype "passive"))
      (node (ref "R23") (pin "1") (pinfunction "1_1") (pintype "passive"))
      (node (ref "U12") (pin "4") (pinfunction "IN+_4") (pintype "bidirectional"))
    )
    (net (code "195") (name "PV_NORTH1_CSENSE_MUX") (class "Default")
      (node (ref "C8") (pin "1") (pinfunction "1_1") (pintype "passive"))
      (node (ref "R8") (pin "1") (pinfunction "1_1") (pintype "passive"))
      (node (ref "U50") (pin "26") (pinfunction "S18_26") (pintype "bidirectional"))
    )
    (net (code "196") (name "PV_NORTH1_P") (class "Default")
      (node (ref "J6") (pin "P$5") (pinfunction "5_P$5") (pintype "passive"))
      (node (ref "R6") (pin "1") (pinfunction "1_1") (pintype "passive"))
      (node (ref "U4") (pin "4") (pinfunction "IN+_4") (pintype "bidirectional"))
    )
    (net (code "197") (name "PV_NORTH2_CSENSE_MUX") (class "Default")
      (node (ref "C18") (pin "1") (pinfunction "1_1") (pintype "passive"))
      (node (ref "R18") (pin "1") (pinfunction "1_1") (pintype "passive"))
      (node (ref "U50") (pin "25") (pinfunction "S17_25") (pintype "bidirectional"))
    )
    (net (code "198") (name "PV_NORTH2_P") (class "Default")
      (node (ref "J6") (pin "P$8") (pinfunction "8_P$8") (pintype "passive"))
      (node (ref "R16") (pin "1") (pinfunction "1_1") (pintype "passive"))
      (node (ref "U9") (pin "4") (pinfunction "IN+_4") (pintype "bidirectional"))
    )
    (net (code "199") (name "PV_SOUTH1_CSENSE_MUX") (class "Default")
      (node (ref "C11") (pin "1") (pinfunction "1_1") (pintype "passive"))
      (node (ref "R11") (pin "1") (pinfunction "1_1") (pintype "passive"))
      (node (ref "U50") (pin "34") (pinfunction "S26_34") (pintype "bidirectional"))
    )
    (net (code "200") (name "PV_SOUTH1_P") (class "Default")
      (node (ref "J8") (pin "P$1") (pinfunction "1_P$1") (pintype "passive"))
      (node (ref "R9") (pin "1") (pinfunction "1_1") (pintype "passive"))
      (node (ref "U5") (pin "4") (pinfunction "IN+_4") (pintype "bidirectional"))
    )
    (net (code "201") (name "PV_SOUTH2_CSENSE_MUX") (class "Default")
      (node (ref "C21") (pin "1") (pinfunction "1_1") (pintype "passive"))
      (node (ref "R21") (pin "1") (pinfunction "1_1") (pintype "passive"))
      (node (ref "U50") (pin "33") (pinfunction "S25_33") (pintype "bidirectional"))
    )
    (net (code "202") (name "PV_SOUTH2_P") (class "Default")
      (node (ref "J8") (pin "P$4") (pinfunction "4_P$4") (pintype "passive"))
      (node (ref "R19") (pin "1") (pinfunction "1_1") (pintype "passive"))
      (node (ref "U10") (pin "4") (pinfunction "IN+_4") (pintype "bidirectional"))
    )
    (net (code "203") (name "PV_TOP1_CSENSE_MUX") (class "Default")
      (node (ref "C7") (pin "1") (pinfunction "1_1") (pintype "passive"))
      (node (ref "R7") (pin "1") (pinfunction "1_1") (pintype "passive"))
      (node (ref "U50") (pin "12") (pinfunction "S1_12") (pintype "bidirectional"))
    )
    (net (code "204") (name "PV_TOP1_P") (class "Default")
      (node (ref "J2") (pin "7") (pinfunction "7_7") (pintype "passive"))
      (node (ref "R5") (pin "1") (pinfunction "1_1") (pintype "passive"))
      (node (ref "U3") (pin "4") (pinfunction "IN+_4") (pintype "bidirectional"))
    )
    (net (code "205") (name "PV_TOP2_CSENSE_MUX") (class "Default")
      (node (ref "C17") (pin "1") (pinfunction "1_1") (pintype "passive"))
      (node (ref "R17") (pin "1") (pinfunction "1_1") (pintype "passive"))
      (node (ref "U50") (pin "11") (pinfunction "S2_11") (pintype "bidirectional"))
    )
    (net (code "206") (name "PV_TOP2_P") (class "Default")
      (node (ref "J2") (pin "10") (pinfunction "10_10") (pintype "passive"))
      (node (ref "R15") (pin "1") (pinfunction "1_1") (pintype "passive"))
      (node (ref "U8") (pin "4") (pinfunction "IN+_4") (pintype "bidirectional"))
    )
    (net (code "207") (name "PV_WEST1_CSENSE_MUX") (class "Default")
      (node (ref "C12") (pin "1") (pinfunction "1_1") (pintype "passive"))
      (node (ref "R12") (pin "1") (pinfunction "1_1") (pintype "passive"))
      (node (ref "U50") (pin "28") (pinfunction "S20_28") (pintype "bidirectional"))
    )
    (net (code "208") (name "PV_WEST1_P") (class "Default")
      (node (ref "J9") (pin "P$1") (pinfunction "1_P$1") (pintype "passive"))
      (node (ref "R10") (pin "1") (pinfunction "1_1") (pintype "passive"))
      (node (ref "U6") (pin "4") (pinfunction "IN+_4") (pintype "bidirectional"))
    )
    (net (code "209") (name "PV_WEST2_CSENSE_MUX") (class "Default")
      (node (ref "C22") (pin "1") (pinfunction "1_1") (pintype "passive"))
      (node (ref "R22") (pin "1") (pinfunction "1_1") (pintype "passive"))
      (node (ref "U50") (pin "32") (pinfunction "S24_32") (pintype "bidirectional"))
    )
    (net (code "210") (name "PV_WEST2_P") (class "Default")
      (node (ref "J9") (pin "P$4") (pinfunction "4_P$4") (pintype "passive"))
      (node (ref "R20") (pin "1") (pinfunction "1_1") (pintype "passive"))
      (node (ref "U11") (pin "4") (pinfunction "IN+_4") (pintype "bidirectional"))
    )
    (net (code "211") (name "RBF_A") (class "Default")
      (node (ref "J7") (pin "P$1") (pinfunction "1_P$1") (pintype "passive"))
    )
    (net (code "212") (name "REG3V3") (class "Default")
      (node (ref "C102") (pin "1") (pinfunction "1_1") (pintype "passive"))
      (node (ref "C103") (pin "1") (pinfunction "1_1") (pintype "passive"))
      (node (ref "C105") (pin "1") (pinfunction "1_1") (pintype "passive"))
      (node (ref "C98") (pin "1") (pinfunction "1_1") (pintype "passive"))
      (node (ref "L1") (pin "2") (pinfunction "2_2") (pintype "passive"))
      (node (ref "R1") (pin "1") (pinfunction "1_1") (pintype "passive"))
      (node (ref "R100") (pin "1") (pinfunction "1_1") (pintype "passive"))
      (node (ref "R104") (pin "2") (pinfunction "2_2") (pintype "passive"))
      (node (ref "R97") (pin "2") (pinfunction "2_2") (pintype "passive"))
      (node (ref "TP21") (pin "TP") (pinfunction "TP_TP") (pintype "input"))
      (node (ref "U1") (pin "4") (pinfunction "IN+_4") (pintype "bidirectional"))
      (node (ref "U43") (pin "5") (pinfunction "V+_5") (pintype "power_in"))
      (node (ref "U44") (pin "14") (pinfunction "VOS_14") (pintype "bidirectional"))
      (node (ref "U44") (pin "7") (pinfunction "FSW_7") (pintype "bidirectional"))
      (node (ref "U45") (pin "3") (pinfunction "S_3") (pintype "passive"))
      (node (ref "U46") (pin "5") (pinfunction "V+_5") (pintype "power_in"))
    )
    (net (code "213") (name "REG5V") (class "Default")
      (node (ref "C109") (pin "1") (pinfunction "1_1") (pintype "passive"))
      (node (ref "C110") (pin "1") (pinfunction "1_1") (pintype "passive"))
      (node (ref "L2") (pin "2") (pinfunction "2_2") (pintype "passive"))
      (node (ref "R107") (pin "1") (pinfunction "1_1") (pintype "passive"))
      (node (ref "R2") (pin "1") (pinfunction "1_1") (pintype "passive"))
      (node (ref "TP20") (pin "TP") (pinfunction "TP_TP") (pintype "input"))
      (node (ref "U2") (pin "4") (pinfunction "IN+_4") (pintype "bidirectional"))
      (node (ref "U47") (pin "14") (pinfunction "VOS_14") (pintype "bidirectional"))
      (node (ref "U47") (pin "7") (pinfunction "FSW_7") (pintype "bidirectional"))
      (node (ref "U48") (pin "3") (pinfunction "S_3") (pintype "passive"))
    )
    (net (code "214") (name "SYS_3V3_CSENSE_MUX") (class "Default")
      (node (ref "C3") (pin "1") (pinfunction "1_1") (pintype "passive"))
      (node (ref "R3") (pin "1") (pinfunction "1_1") (pintype "passive"))
      (node (ref "U50") (pin "1") (pinfunction "S12_1") (pintype "bidirectional"))
    )
    (net (code "215") (name "SYS_5V_CSENSE_MUX") (class "Default")
      (node (ref "C4") (pin "1") (pinfunction "1_1") (pintype "passive"))
      (node (ref "R4") (pin "1") (pinfunction "1_1") (pintype "passive"))
      (node (ref "U50") (pin "2") (pinfunction "S11_2") (pintype "bidirectional"))
    )
    (net (code "216") (name "TS") (class "Default")
      (node (ref "C125") (pin "1") (pinfunction "1_1") (pintype "passive"))
      (node (ref "R125") (pin "2") (pinfunction "2_2") (pintype "passive"))
      (node (ref "U53") (pin "4") (pinfunction "TS_4") (pintype "input"))
    )
    (net (code "217") (name "UVP3V3_GATE") (class "Default")
      (node (ref "R99") (pin "2") (pinfunction "2_2") (pintype "passive"))
      (node (ref "TP13") (pin "TP") (pinfunction "TP_TP") (pintype "input"))
      (node (ref "U43") (pin "1") (pinfunction "OUT_1") (pintype "output"))
      (node (ref "U45") (pin "2") (pinfunction "G_2") (pintype "passive"))
    )
    (net (code "218") (name "UVP3V3_OUT") (class "Default")
      (node (ref "C1") (pin "1") (pinfunction "1_1") (pintype "passive"))
      (node (ref "C10") (pin "1") (pinfunction "1_1") (pintype "passive"))
      (node (ref "C111") (pin "1") (pinfunction "1_1") (pintype "passive"))
      (node (ref "C113") (pin "1") (pinfunction "1_1") (pintype "passive"))
      (node (ref "C13") (pin "1") (pinfunction "1_1") (pintype "passive"))
      (node (ref "C136") (pin "1") (pinfunction "1_1") (pintype "passive"))
      (node (ref "C15") (pin "1") (pinfunction "1_1") (pintype "passive"))
      (node (ref "C16") (pin "1") (pinfunction "1_1") (pintype "passive"))
      (node (ref "C19") (pin "1") (pinfunction "1_1") (pintype "passive"))
      (node (ref "C2") (pin "1") (pinfunction "1_1") (pintype "passive"))
      (node (ref "C20") (pin "1") (pinfunction "1_1") (pintype "passive"))
      (node (ref "C23") (pin "1") (pinfunction "1_1") (pintype "passive"))
      (node (ref "C32") (pin "1") (pinfunction "1_1") (pintype "passive"))
      (node (ref "C33") (pin "1") (pinfunction "1_1") (pintype "passive"))
      (node (ref "C34") (pin "1") (pinfunction "1_1") (pintype "passive"))
      (node (ref "C35") (pin "2") (pinfunction "2_2") (pintype "passive"))
      (node (ref "C37") (pin "1") (pinfunction "1_1") (pintype "passive"))
      (node (ref "C43") (pin "1") (pinfunction "1_1") (pintype "passive"))
      (node (ref "C44") (pin "1") (pinfunction "1_1") (pintype "passive"))
      (node (ref "C45") (pin "1") (pinfunction "1_1") (pintype "passive"))
      (node (ref "C46") (pin "2") (pinfunction "2_2") (pintype "passive"))
      (node (ref "C48") (pin "1") (pinfunction "1_1") (pintype "passive"))
      (node (ref "C5") (pin "1") (pinfunction "1_1") (pintype "passive"))
      (node (ref "C54") (pin "1") (pinfunction "1_1") (pintype "passive"))
      (node (ref "C55") (pin "1") (pinfunction "1_1") (pintype "passive"))
      (node (ref "C56") (pin "1") (pinfunction "1_1") (pintype "passive"))
      (node (ref "C57") (pin "2") (pinfunction "2_2") (pintype "passive"))
      (node (ref "C59") (pin "1") (pinfunction "1_1") (pintype "passive"))
      (node (ref "C6") (pin "1") (pinfunction "1_1") (pintype "passive"))
      (node (ref "C65") (pin "1") (pinfunction "1_1") (pintype "passive"))
      (node (ref "C66") (pin "1") (pinfunction "1_1") (pintype "passive"))
      (node (ref "C67") (pin "1") (pinfunction "1_1") (pintype "passive"))
      (node (ref "C68") (pin "2") (pinfunction "2_2") (pintype "passive"))
      (node (ref "C70") (pin "1") (pinfunction "1_1") (pintype "passive"))
      (node (ref "C73") (pin "1") (pinfunction "1_1") (pintype "passive"))
      (node (ref "C76") (pin "1") (pinfunction "1_1") (pintype "passive"))
      (node (ref "C77") (pin "1") (pinfunction "1_1") (pintype "passive"))
      (node (ref "C78") (pin "1") (pinfunction "1_1") (pintype "passive"))
      (node (ref "C79") (pin "2") (pinfunction "2_2") (pintype "passive"))
      (node (ref "C81") (pin "1") (pinfunction "1_1") (pintype "passive"))
      (node (ref "C84") (pin "1") (pinfunction "1_1") (pintype "passive"))
      (node (ref "C87") (pin "1") (pinfunction "1_1") (pintype "passive"))
      (node (ref "C88") (pin "1") (pinfunction "1_1") (pintype "passive"))
      (node (ref "C89") (pin "1") (pinfunction "1_1") (pintype "passive"))
      (node (ref "C9") (pin "1") (pinfunction "1_1") (pintype "passive"))
      (node (ref "C90") (pin "2") (pinfunction "2_2") (pintype "passive"))
      (node (ref "C92") (pin "1") (pinfunction "1_1") (pintype "passive"))
      (node (ref "D1") (pin "1") (pinfunction "C_1") (pintype "passive"))
      (node (ref "D2") (pin "1") (pinfunction "C_1") (pintype "passive"))
      (node (ref "D3") (pin "1") (pinfunction "C_1") (pintype "passive"))
      (node (ref "D4") (pin "1") (pinfunction "C_1") (pintype "passive"))
      (node (ref "D5") (pin "1") (pinfunction "C_1") (pintype "passive"))
      (node (ref "D6") (pin "1") (pinfunction "C_1") (pintype "passive"))
      (node (ref "J6") (pin "P$2") (pinfunction "2_P$2") (pintype "passive"))
      (node (ref "R109") (pin "2") (pinfunction "2_2") (pintype "passive"))
      (node (ref "R29") (pin "2") (pinfunction "2_2") (pintype "passive"))
      (node (ref "R30") (pin "2") (pinfunction "2_2") (pintype "passive"))
      (node (ref "R35") (pin "2") (pinfunction "2_2") (pintype "passive"))
      (node (ref "R43") (pin "2") (pinfunction "2_2") (pintype "passive"))
      (node (ref "R52") (pin "2") (pinfunction "2_2") (pintype "passive"))
      (node (ref "R61") (pin "2") (pinfunction "2_2") (pintype "passive"))
      (node (ref "R66") (pin "1") (pinfunction "1_1") (pintype "passive"))
      (node (ref "R70") (pin "2") (pinfunction "2_2") (pintype "passive"))
      (node (ref "R75") (pin "1") (pinfunction "1_1") (pintype "passive"))
      (node (ref "R79") (pin "2") (pinfunction "2_2") (pintype "passive"))
      (node (ref "R88") (pin "2") (pinfunction "2_2") (pintype "passive"))
      (node (ref "R93") (pin "2") (pinfunction "2_2") (pintype "passive"))
      (node (ref "TP17") (pin "TP") (pinfunction "TP_TP") (pintype "input"))
      (node (ref "U1") (pin "3") (pinfunction "V+_3") (pintype "power_in"))
      (node (ref "U10") (pin "3") (pinfunction "V+_3") (pintype "power_in"))
      (node (ref "U11") (pin "3") (pinfunction "V+_3") (pintype "power_in"))
      (node (ref "U12") (pin "3") (pinfunction "V+_3") (pintype "power_in"))
      (node (ref "U13") (pin "2") (pinfunction "V+_2") (pintype "power_in"))
      (node (ref "U14") (pin "3") (pinfunction "V+_3") (pintype "power_in"))
      (node (ref "U15") (pin "5") (pinfunction "V+_5") (pintype "power_in"))
      (node (ref "U16") (pin "5") (pinfunction "VCC_5") (pintype "bidirectional"))
      (node (ref "U18") (pin "2") (pinfunction "V+_2") (pintype "power_in"))
      (node (ref "U19") (pin "3") (pinfunction "V+_3") (pintype "power_in"))
      (node (ref "U2") (pin "3") (pinfunction "V+_3") (pintype "power_in"))
      (node (ref "U20") (pin "5") (pinfunction "V+_5") (pintype "power_in"))
      (node (ref "U21") (pin "5") (pinfunction "VCC_5") (pintype "bidirectional"))
      (node (ref "U23") (pin "2") (pinfunction "V+_2") (pintype "power_in"))
      (node (ref "U24") (pin "3") (pinfunction "V+_3") (pintype "power_in"))
      (node (ref "U25") (pin "5") (pinfunction "V+_5") (pintype "power_in"))
      (node (ref "U26") (pin "5") (pinfunction "VCC_5") (pintype "bidirectional"))
      (node (ref "U28") (pin "2") (pinfunction "V+_2") (pintype "power_in"))
      (node (ref "U29") (pin "3") (pinfunction "V+_3") (pintype "power_in"))
      (node (ref "U29") (pin "4") (pinfunction "IN+_4") (pintype "bidirectional"))
      (node (ref "U3") (pin "3") (pinfunction "V+_3") (pintype "power_in"))
      (node (ref "U30") (pin "5") (pinfunction "V+_5") (pintype "power_in"))
      (node (ref "U31") (pin "5") (pinfunction "VCC_5") (pintype "bidirectional"))
      (node (ref "U33") (pin "2") (pinfunction "V+_2") (pintype "power_in"))
      (node (ref "U34") (pin "3") (pinfunction "V+_3") (pintype "power_in"))
      (node (ref "U34") (pin "4") (pinfunction "IN+_4") (pintype "bidirectional"))
      (node (ref "U35") (pin "5") (pinfunction "V+_5") (pintype "power_in"))
      (node (ref "U36") (pin "5") (pinfunction "VCC_5") (pintype "bidirectional"))
      (node (ref "U38") (pin "2") (pinfunction "V+_2") (pintype "power_in"))
      (node (ref "U39") (pin "3") (pinfunction "V+_3") (pintype "power_in"))
      (node (ref "U4") (pin "3") (pinfunction "V+_3") (pintype "power_in"))
      (node (ref "U40") (pin "5") (pinfunction "V+_5") (pintype "power_in"))
      (node (ref "U41") (pin "5") (pinfunction "VCC_5") (pintype "bidirectional"))
      (node (ref "U45") (pin "5") (pinfunction "D_5") (pintype "passive"))
      (node (ref "U45") (pin "6") (pinfunction "D_6") (pintype "passive"))
      (node (ref "U49") (pin "30") (pinfunction "30_30") (pintype "power_in"))
      (node (ref "U5") (pin "3") (pinfunction "V+_3") (pintype "power_in"))
      (node (ref "U50") (pin "13") (pinfunction "VDD_13") (pintype "power_in"))
      (node (ref "U50") (pin "14") (pinfunction "VDD_14") (pintype "power_in"))
      (node (ref "U54") (pin "3") (pinfunction "V+_3") (pintype "power_in"))
      (node (ref "U6") (pin "3") (pinfunction "V+_3") (pintype "power_in"))
      (node (ref "U7") (pin "3") (pinfunction "V+_3") (pintype "power_in"))
      (node (ref "U8") (pin "3") (pinfunction "V+_3") (pintype "power_in"))
      (node (ref "U9") (pin "3") (pinfunction "V+_3") (pintype "power_in"))
    )
    (net (code "219") (name "UVP3V3_VSENSE") (class "Default")
      (node (ref "C30") (pin "1") (pinfunction "1_1") (pintype "passive"))
      (node (ref "R35") (pin "1") (pinfunction "1_1") (pintype "passive"))
      (node (ref "R36") (pin "2") (pinfunction "2_2") (pintype "passive"))
      (node (ref "U50") (pin "36") (pinfunction "S28_36") (pintype "bidirectional"))
    )
    (net (code "220") (name "UVP5V_GATE") (class "Default")
      (node (ref "R106") (pin "2") (pinfunction "2_2") (pintype "passive"))
      (node (ref "TP14") (pin "TP") (pinfunction "TP_TP") (pintype "input"))
      (node (ref "U46") (pin "1") (pinfunction "OUT_1") (pintype "output"))
      (node (ref "U48") (pin "2") (pinfunction "G_2") (pintype "passive"))
    )
    (net (code "221") (name "UVP5V_OUT") (class "Default")
      (node (ref "C40") (pin "1") (pinfunction "1_1") (pintype "passive"))
      (node (ref "C51") (pin "1") (pinfunction "1_1") (pintype "passive"))
      (node (ref "C62") (pin "1") (pinfunction "1_1") (pintype "passive"))
      (node (ref "R33") (pin "2") (pinfunction "2_2") (pintype "passive"))
      (node (ref "R39") (pin "1") (pinfunction "1_1") (pintype "passive"))
      (node (ref "R48") (pin "1") (pinfunction "1_1") (pintype "passive"))
      (node (ref "R57") (pin "1") (pinfunction "1_1") (pintype "passive"))
      (node (ref "TP18") (pin "TP") (pinfunction "TP_TP") (pintype "input"))
      (node (ref "U14") (pin "4") (pinfunction "IN+_4") (pintype "bidirectional"))
      (node (ref "U19") (pin "4") (pinfunction "IN+_4") (pintype "bidirectional"))
      (node (ref "U24") (pin "4") (pinfunction "IN+_4") (pintype "bidirectional"))
      (node (ref "U48") (pin "5") (pinfunction "D_5") (pintype "passive"))
      (node (ref "U48") (pin "6") (pinfunction "D_6") (pintype "passive"))
    )
    (net (code "222") (name "UVP5V_VSENSE") (class "Default")
      (node (ref "C29") (pin "1") (pinfunction "1_1") (pintype "passive"))
      (node (ref "R33") (pin "1") (pinfunction "1_1") (pintype "passive"))
      (node (ref "R34") (pin "2") (pinfunction "2_2") (pintype "passive"))
      (node (ref "U50") (pin "35") (pinfunction "S27_35") (pintype "bidirectional"))
    )
    (net (code "223") (name "VBATT") (class "Default")
      (node (ref "C100") (pin "1") (pinfunction "1_1") (pintype "passive"))
      (node (ref "C104") (pin "1") (pinfunction "1_1") (pintype "passive"))
      (node (ref "C106") (pin "1") (pinfunction "1_1") (pintype "passive"))
      (node (ref "C107") (pin "1") (pinfunction "1_1") (pintype "passive"))
      (node (ref "C95") (pin "1") (pinfunction "1_1") (pintype "passive"))
      (node (ref "C97") (pin "1") (pinfunction "1_1") (pintype "passive"))
      (node (ref "C99") (pin "1") (pinfunction "1_1") (pintype "passive"))
      (node (ref "J2") (pin "20") (pinfunction "20_20") (pintype "passive"))
      (node (ref "J2") (pin "35") (pinfunction "35_35") (pintype "passive"))
      (node (ref "J2") (pin "36") (pinfunction "36_36") (pintype "passive"))
      (node (ref "J2") (pin "45") (pinfunction "45_45") (pintype "passive"))
      (node (ref "J2") (pin "46") (pinfunction "46_46") (pintype "passive"))
      (node (ref "R102") (pin "1") (pinfunction "1_1") (pintype "passive"))
      (node (ref "R37") (pin "2") (pinfunction "2_2") (pintype "passive"))
      (node (ref "R44") (pin "2") (pinfunction "2_2") (pintype "passive"))
      (node (ref "R53") (pin "2") (pinfunction "2_2") (pintype "passive"))
      (node (ref "R62") (pin "2") (pinfunction "2_2") (pintype "passive"))
      (node (ref "R71") (pin "2") (pinfunction "2_2") (pintype "passive"))
      (node (ref "R80") (pin "2") (pinfunction "2_2") (pintype "passive"))
      (node (ref "R84") (pin "1") (pinfunction "1_1") (pintype "passive"))
      (node (ref "R95") (pin "1") (pinfunction "1_1") (pintype "passive"))
      (node (ref "TP19") (pin "TP") (pinfunction "TP_TP") (pintype "input"))
      (node (ref "U39") (pin "4") (pinfunction "IN+_4") (pintype "bidirectional"))
      (node (ref "U44") (pin "10") (pinfunction "AVIN_10") (pintype "power_in"))
      (node (ref "U44") (pin "11") (pinfunction "PVIN_11") (pintype "power_in"))
      (node (ref "U44") (pin "12") (pinfunction "PVIN_12") (pintype "power_in"))
      (node (ref "U44") (pin "13") (pinfunction "EN_13") (pintype "bidirectional"))
      (node (ref "U47") (pin "10") (pinfunction "AVIN_10") (pintype "power_in"))
      (node (ref "U47") (pin "11") (pinfunction "PVIN_11") (pintype "power_in"))
      (node (ref "U47") (pin "12") (pinfunction "PVIN_12") (pintype "power_in"))
      (node (ref "U47") (pin "13") (pinfunction "EN_13") (pintype "bidirectional"))
    )
    (net (code "224") (name "VBATT_VSENSE") (class "Default")
      (node (ref "C31") (pin "1") (pinfunction "1_1") (pintype "passive"))
      (node (ref "R37") (pin "1") (pinfunction "1_1") (pintype "passive"))
      (node (ref "R38") (pin "2") (pinfunction "2_2") (pintype "passive"))
      (node (ref "U50") (pin "37") (pinfunction "S29_37") (pintype "bidirectional"))
    )
    (net (code "225") (name "VREF") (class "Default")
      (node (ref "C126") (pin "1") (pinfunction "1_1") (pintype "passive"))
      (node (ref "R124") (pin "2") (pinfunction "2_2") (pintype "passive"))
      (node (ref "R126") (pin "2") (pinfunction "2_2") (pintype "passive"))
      (node (ref "U53") (pin "6") (pinfunction "VREF_6") (pintype "power_in"))
      (node (ref "U53") (pin "7") (pinfunction "TERM_EN_7") (pintype "input"))
    )
    (net (code "226") (name "unconnected-(J1-Pad1)") (class "Default")
      (node (ref "J1") (pin "1") (pinfunction "1_1") (pintype "passive"))
    )
    (net (code "227") (name "unconnected-(J1-Pad2)") (class "Default")
      (node (ref "J1") (pin "2") (pinfunction "2_2") (pintype "passive"))
    )
    (net (code "228") (name "unconnected-(J1-Pad7)") (class "Default")
      (node (ref "J1") (pin "7") (pinfunction "7_7") (pintype "passive"))
    )
    (net (code "229") (name "unconnected-(J1-Pad8)") (class "Default")
      (node (ref "J1") (pin "8") (pinfunction "8_8") (pintype "passive"))
    )
    (net (code "230") (name "unconnected-(J1-Pad9)") (class "Default")
      (node (ref "J1") (pin "9") (pinfunction "9_9") (pintype "passive"))
    )
    (net (code "231") (name "unconnected-(J1-Pad10)") (class "Default")
      (node (ref "J1") (pin "10") (pinfunction "10_10") (pintype "passive"))
    )
    (net (code "232") (name "unconnected-(J1-Pad11)") (class "Default")
      (node (ref "J1") (pin "11") (pinfunction "11_11") (pintype "passive"))
    )
    (net (code "233") (name "unconnected-(J1-Pad12)") (class "Default")
      (node (ref "J1") (pin "12") (pinfunction "12_12") (pintype "passive"))
    )
    (net (code "234") (name "unconnected-(J1-Pad14)") (class "Default")
      (node (ref "J1") (pin "14") (pinfunction "14_14") (pintype "passive"))
    )
    (net (code "235") (name "unconnected-(J1-Pad15)") (class "Default")
      (node (ref "J1") (pin "15") (pinfunction "15_15") (pintype "passive"))
    )
    (net (code "236") (name "unconnected-(J1-Pad16)") (class "Default")
      (node (ref "J1") (pin "16") (pinfunction "16_16") (pintype "passive"))
    )
    (net (code "237") (name "unconnected-(J1-Pad17)") (class "Default")
      (node (ref "J1") (pin "17") (pinfunction "17_17") (pintype "passive"))
    )
    (net (code "238") (name "unconnected-(J1-Pad20)") (class "Default")
      (node (ref "J1") (pin "20") (pinfunction "20_20") (pintype "passive"))
    )
    (net (code "239") (name "unconnected-(J1-Pad22)") (class "Default")
      (node (ref "J1") (pin "22") (pinfunction "22_22") (pintype "passive"))
    )
    (net (code "240") (name "unconnected-(J1-Pad23)") (class "Default")
      (node (ref "J1") (pin "23") (pinfunction "23_23") (pintype "passive"))
    )
    (net (code "241") (name "unconnected-(J1-Pad24)") (class "Default")
      (node (ref "J1") (pin "24") (pinfunction "24_24") (pintype "passive"))
    )
    (net (code "242") (name "unconnected-(J1-Pad25)") (class "Default")
      (node (ref "J1") (pin "25") (pinfunction "25_25") (pintype "passive"))
    )
    (net (code "243") (name "unconnected-(J1-Pad26)") (class "Default")
      (node (ref "J1") (pin "26") (pinfunction "26_26") (pintype "passive"))
    )
    (net (code "244") (name "unconnected-(J1-Pad27)") (class "Default")
      (node (ref "J1") (pin "27") (pinfunction "27_27") (pintype "passive"))
    )
    (net (code "245") (name "unconnected-(J1-Pad28)") (class "Default")
      (node (ref "J1") (pin "28") (pinfunction "28_28") (pintype "passive"))
    )
    (net (code "246") (name "unconnected-(J1-Pad29)") (class "Default")
      (node (ref "J1") (pin "29") (pinfunction "29_29") (pintype "passive"))
    )
    (net (code "247") (name "unconnected-(J1-Pad30)") (class "Default")
      (node (ref "J1") (pin "30") (pinfunction "30_30") (pintype "passive"))
    )
    (net (code "248") (name "unconnected-(J1-Pad31)") (class "Default")
      (node (ref "J1") (pin "31") (pinfunction "31_31") (pintype "passive"))
    )
    (net (code "249") (name "unconnected-(J1-Pad32)") (class "Default")
      (node (ref "J1") (pin "32") (pinfunction "32_32") (pintype "passive"))
    )
    (net (code "250") (name "unconnected-(J1-Pad33)") (class "Default")
      (node (ref "J1") (pin "33") (pinfunction "33_33") (pintype "passive"))
    )
    (net (code "251") (name "unconnected-(J1-Pad34)") (class "Default")
      (node (ref "J1") (pin "34") (pinfunction "34_34") (pintype "passive"))
    )
    (net (code "252") (name "unconnected-(J1-Pad35)") (class "Default")
      (node (ref "J1") (pin "35") (pinfunction "35_35") (pintype "passive"))
    )
    (net (code "253") (name "unconnected-(J1-Pad36)") (class "Default")
      (node (ref "J1") (pin "36") (pinfunction "36_36") (pintype "passive"))
    )
    (net (code "254") (name "unconnected-(J1-Pad37)") (class "Default")
      (node (ref "J1") (pin "37") (pinfunction "37_37") (pintype "passive"))
    )
    (net (code "255") (name "unconnected-(J1-Pad38)") (class "Default")
      (node (ref "J1") (pin "38") (pinfunction "38_38") (pintype "passive"))
    )
    (net (code "256") (name "unconnected-(J1-Pad39)") (class "Default")
      (node (ref "J1") (pin "39") (pinfunction "39_39") (pintype "passive"))
    )
    (net (code "257") (name "unconnected-(J1-Pad40)") (class "Default")
      (node (ref "J1") (pin "40") (pinfunction "40_40") (pintype "passive"))
    )
    (net (code "258") (name "unconnected-(J1-Pad42)") (class "Default")
      (node (ref "J1") (pin "42") (pinfunction "42_42") (pintype "passive"))
    )
    (net (code "259") (name "unconnected-(J1-Pad44)") (class "Default")
      (node (ref "J1") (pin "44") (pinfunction "44_44") (pintype "passive"))
    )
    (net (code "260") (name "unconnected-(J1-Pad45)") (class "Default")
      (node (ref "J1") (pin "45") (pinfunction "45_45") (pintype "passive"))
    )
    (net (code "261") (name "unconnected-(J1-Pad46)") (class "Default")
      (node (ref "J1") (pin "46") (pinfunction "46_46") (pintype "passive"))
    )
    (net (code "262") (name "unconnected-(J2-Pad1)") (class "Default")
      (node (ref "J2") (pin "1") (pinfunction "1_1") (pintype "passive"))
    )
    (net (code "263") (name "unconnected-(J2-Pad2)") (class "Default")
      (node (ref "J2") (pin "2") (pinfunction "2_2") (pintype "passive"))
    )
    (net (code "264") (name "unconnected-(J2-Pad5)") (class "Default")
      (node (ref "J2") (pin "5") (pinfunction "5_5") (pintype "passive"))
    )
    (net (code "265") (name "unconnected-(J2-Pad6)") (class "Default")
      (node (ref "J2") (pin "6") (pinfunction "6_6") (pintype "passive"))
    )
    (net (code "266") (name "unconnected-(J2-Pad11)") (class "Default")
      (node (ref "J2") (pin "11") (pinfunction "11_11") (pintype "passive"))
    )
    (net (code "267") (name "unconnected-(J2-Pad12)") (class "Default")
      (node (ref "J2") (pin "12") (pinfunction "12_12") (pintype "passive"))
    )
    (net (code "268") (name "unconnected-(J2-Pad13)") (class "Default")
      (node (ref "J2") (pin "13") (pinfunction "13_13") (pintype "passive"))
    )
    (net (code "269") (name "unconnected-(J2-Pad14)") (class "Default")
      (node (ref "J2") (pin "14") (pinfunction "14_14") (pintype "passive"))
    )
    (net (code "270") (name "unconnected-(J2-Pad19)") (class "Default")
      (node (ref "J2") (pin "19") (pinfunction "19_19") (pintype "passive"))
    )
    (net (code "271") (name "unconnected-(J2-Pad21)") (class "Default")
      (node (ref "J2") (pin "21") (pinfunction "21_21") (pintype "passive"))
    )
    (net (code "272") (name "unconnected-(J2-Pad23)") (class "Default")
      (node (ref "J2") (pin "23") (pinfunction "23_23") (pintype "passive"))
    )
    (net (code "273") (name "unconnected-(J2-Pad24)") (class "Default")
      (node (ref "J2") (pin "24") (pinfunction "24_24") (pintype "passive"))
    )
    (net (code "274") (name "unconnected-(J2-Pad33)") (class "Default")
      (node (ref "J2") (pin "33") (pinfunction "33_33") (pintype "passive"))
    )
    (net (code "275") (name "unconnected-(J2-Pad34)") (class "Default")
      (node (ref "J2") (pin "34") (pinfunction "34_34") (pintype "passive"))
    )
    (net (code "276") (name "unconnected-(J2-Pad37)") (class "Default")
      (node (ref "J2") (pin "37") (pinfunction "37_37") (pintype "passive"))
    )
    (net (code "277") (name "unconnected-(J2-Pad38)") (class "Default")
      (node (ref "J2") (pin "38") (pinfunction "38_38") (pintype "passive"))
    )
    (net (code "278") (name "unconnected-(J2-Pad39)") (class "Default")
      (node (ref "J2") (pin "39") (pinfunction "39_39") (pintype "passive"))
    )
    (net (code "279") (name "unconnected-(J2-Pad40)") (class "Default")
      (node (ref "J2") (pin "40") (pinfunction "40_40") (pintype "passive"))
    )
    (net (code "280") (name "unconnected-(J2-Pad48)") (class "Default")
      (node (ref "J2") (pin "48") (pinfunction "48_48") (pintype "passive"))
    )
    (net (code "281") (name "unconnected-(J2-Pad49)") (class "Default")
      (node (ref "J2") (pin "49") (pinfunction "49_49") (pintype "passive"))
    )
    (net (code "282") (name "unconnected-(J2-Pad50)") (class "Default")
      (node (ref "J2") (pin "50") (pinfunction "50_50") (pintype "passive"))
    )
    (net (code "283") (name "unconnected-(J2-Pad51)") (class "Default")
      (node (ref "J2") (pin "51") (pinfunction "51_51") (pintype "passive"))
    )
    (net (code "284") (name "unconnected-(J2-Pad52)") (class "Default")
      (node (ref "J2") (pin "52") (pinfunction "52_52") (pintype "passive"))
    )
    (net (code "285") (name "unconnected-(U44-PG-Pad4)") (class "Default")
      (node (ref "U44") (pin "4") (pinfunction "PG_4") (pintype "bidirectional"))
    )
    (net (code "286") (name "unconnected-(U47-PG-Pad4)") (class "Default")
      (node (ref "U47") (pin "4") (pinfunction "PG_4") (pintype "bidirectional"))
    )
    (net (code "287") (name "unconnected-(U49-Pad4)") (class "Default")
      (node (ref "U49") (pin "4") (pinfunction "4_4") (pintype "no_connect"))
    )
    (net (code "288") (name "unconnected-(U49-Pad9)") (class "Default")
      (node (ref "U49") (pin "9") (pinfunction "9_9") (pintype "bidirectional"))
    )
    (net (code "289") (name "unconnected-(U49-Pad12)") (class "Default")
      (node (ref "U49") (pin "12") (pinfunction "12_12") (pintype "bidirectional"))
    )
    (net (code "290") (name "unconnected-(U49-Pad17)") (class "Default")
      (node (ref "U49") (pin "17") (pinfunction "17_17") (pintype "no_connect"))
    )
    (net (code "291") (name "unconnected-(U49-Pad19)") (class "Default")
      (node (ref "U49") (pin "19") (pinfunction "19_19") (pintype "bidirectional"))
    )
    (net (code "292") (name "unconnected-(U49-Pad20)") (class "Default")
      (node (ref "U49") (pin "20") (pinfunction "20_20") (pintype "no_connect"))
    )
    (net (code "293") (name "unconnected-(U49-Pad27)") (class "Default")
      (node (ref "U49") (pin "27") (pinfunction "27_27") (pintype "bidirectional"))
    )
    (net (code "294") (name "unconnected-(U49-Pad28)") (class "Default")
      (node (ref "U49") (pin "28") (pinfunction "28_28") (pintype "bidirectional"))
    )
    (net (code "295") (name "unconnected-(U49-Pad31)") (class "Default")
      (node (ref "U49") (pin "31") (pinfunction "31_31") (pintype "no_connect"))
    )
    (net (code "296") (name "unconnected-(U50A-S16-Pad45)") (class "Default")
      (node (ref "U50") (pin "45") (pinfunction "S16_45") (pintype "bidirectional"))
    )
    (net (code "297") (name "unconnected-(U53-STAT1-Pad3)") (class "Default")
      (node (ref "U53") (pin "3") (pinfunction "STAT1_3") (pintype "output"))
    )
    (net (code "298") (name "unconnected-(U53-STAT2-Pad5)") (class "Default")
      (node (ref "U53") (pin "5") (pinfunction "STAT2_5") (pintype "output"))
    )
  )
)
